# SHA256.net
KiCad netlist of a schematic drawn in Altium Designer
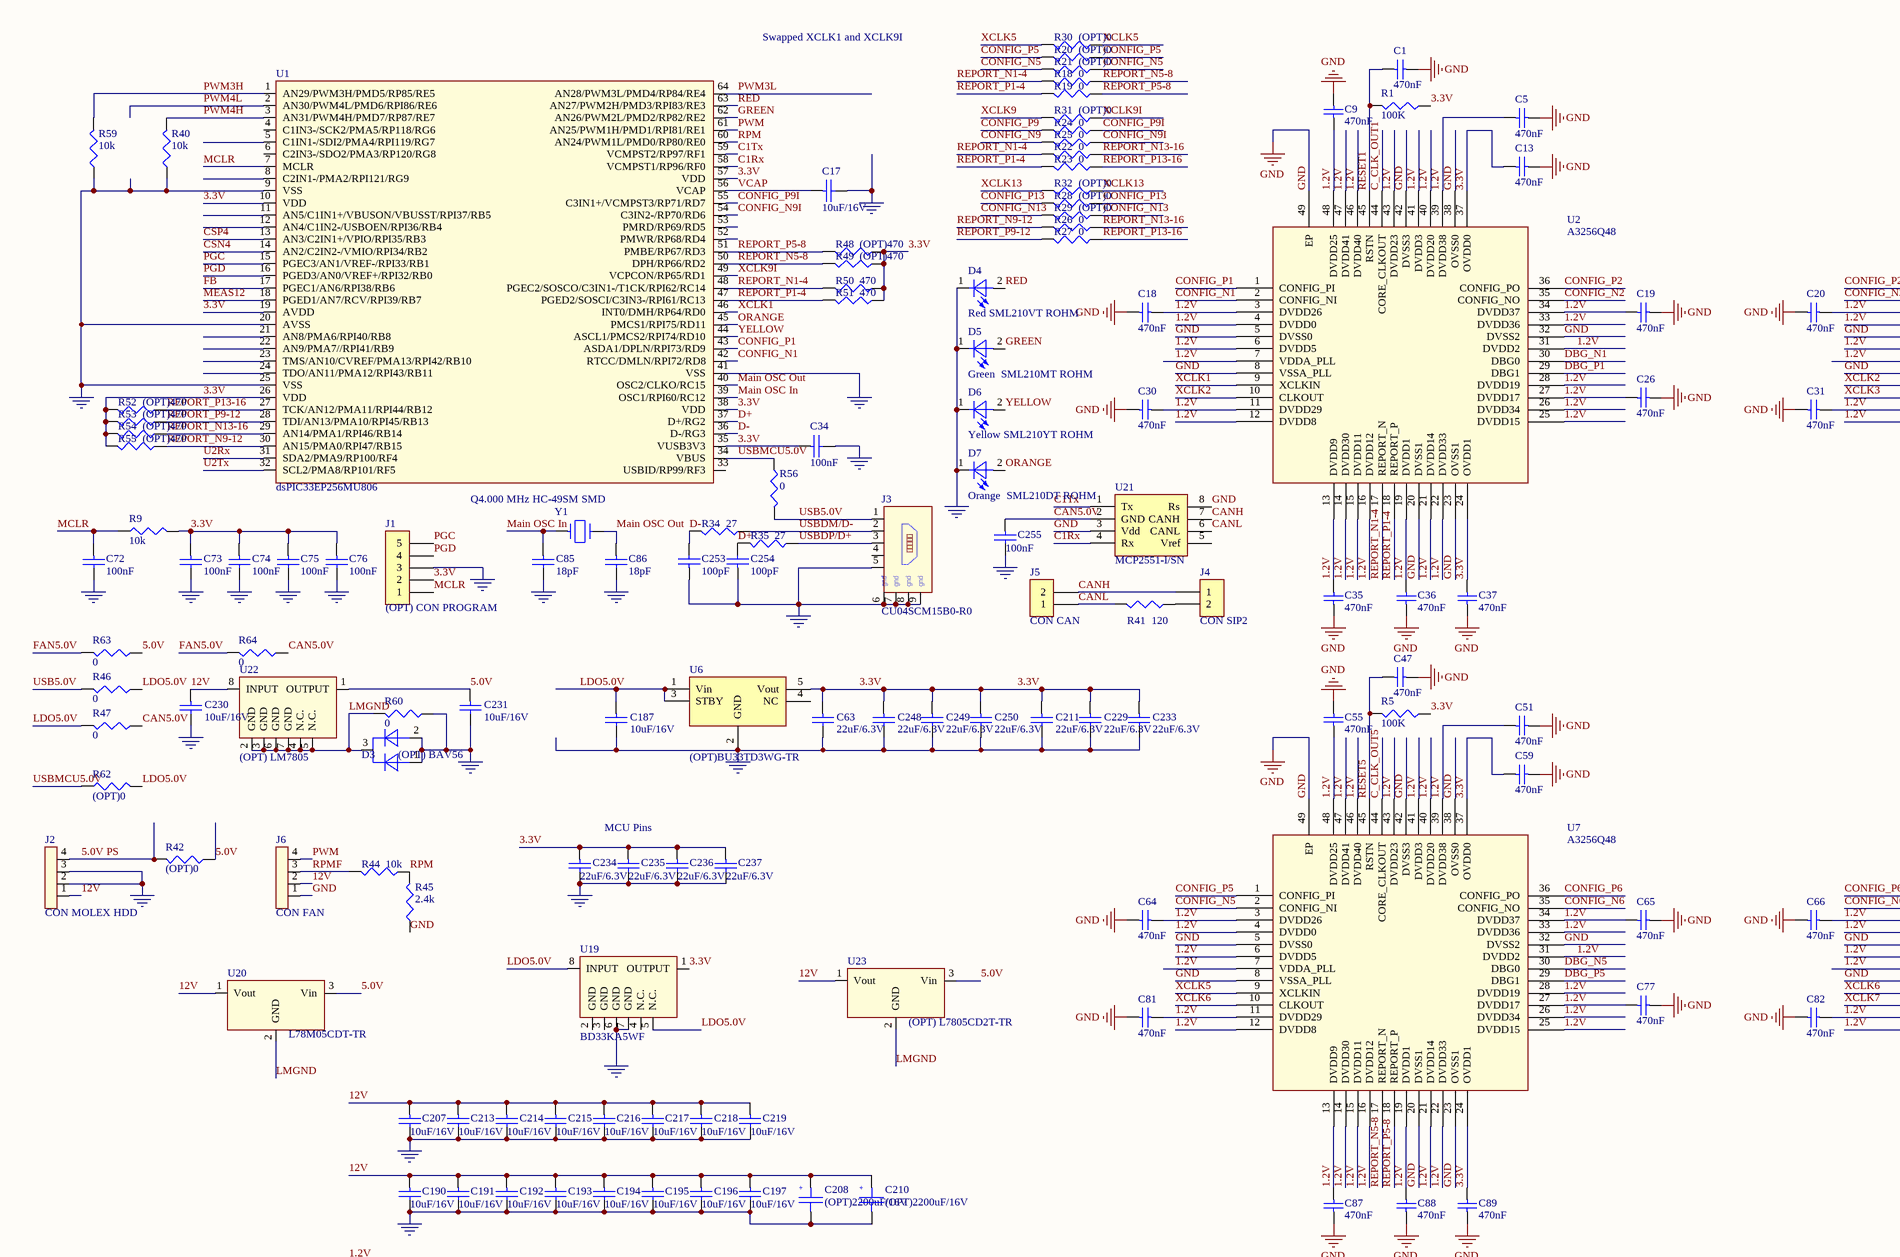
[diagram p0: SHA256.SchDoc, top left]
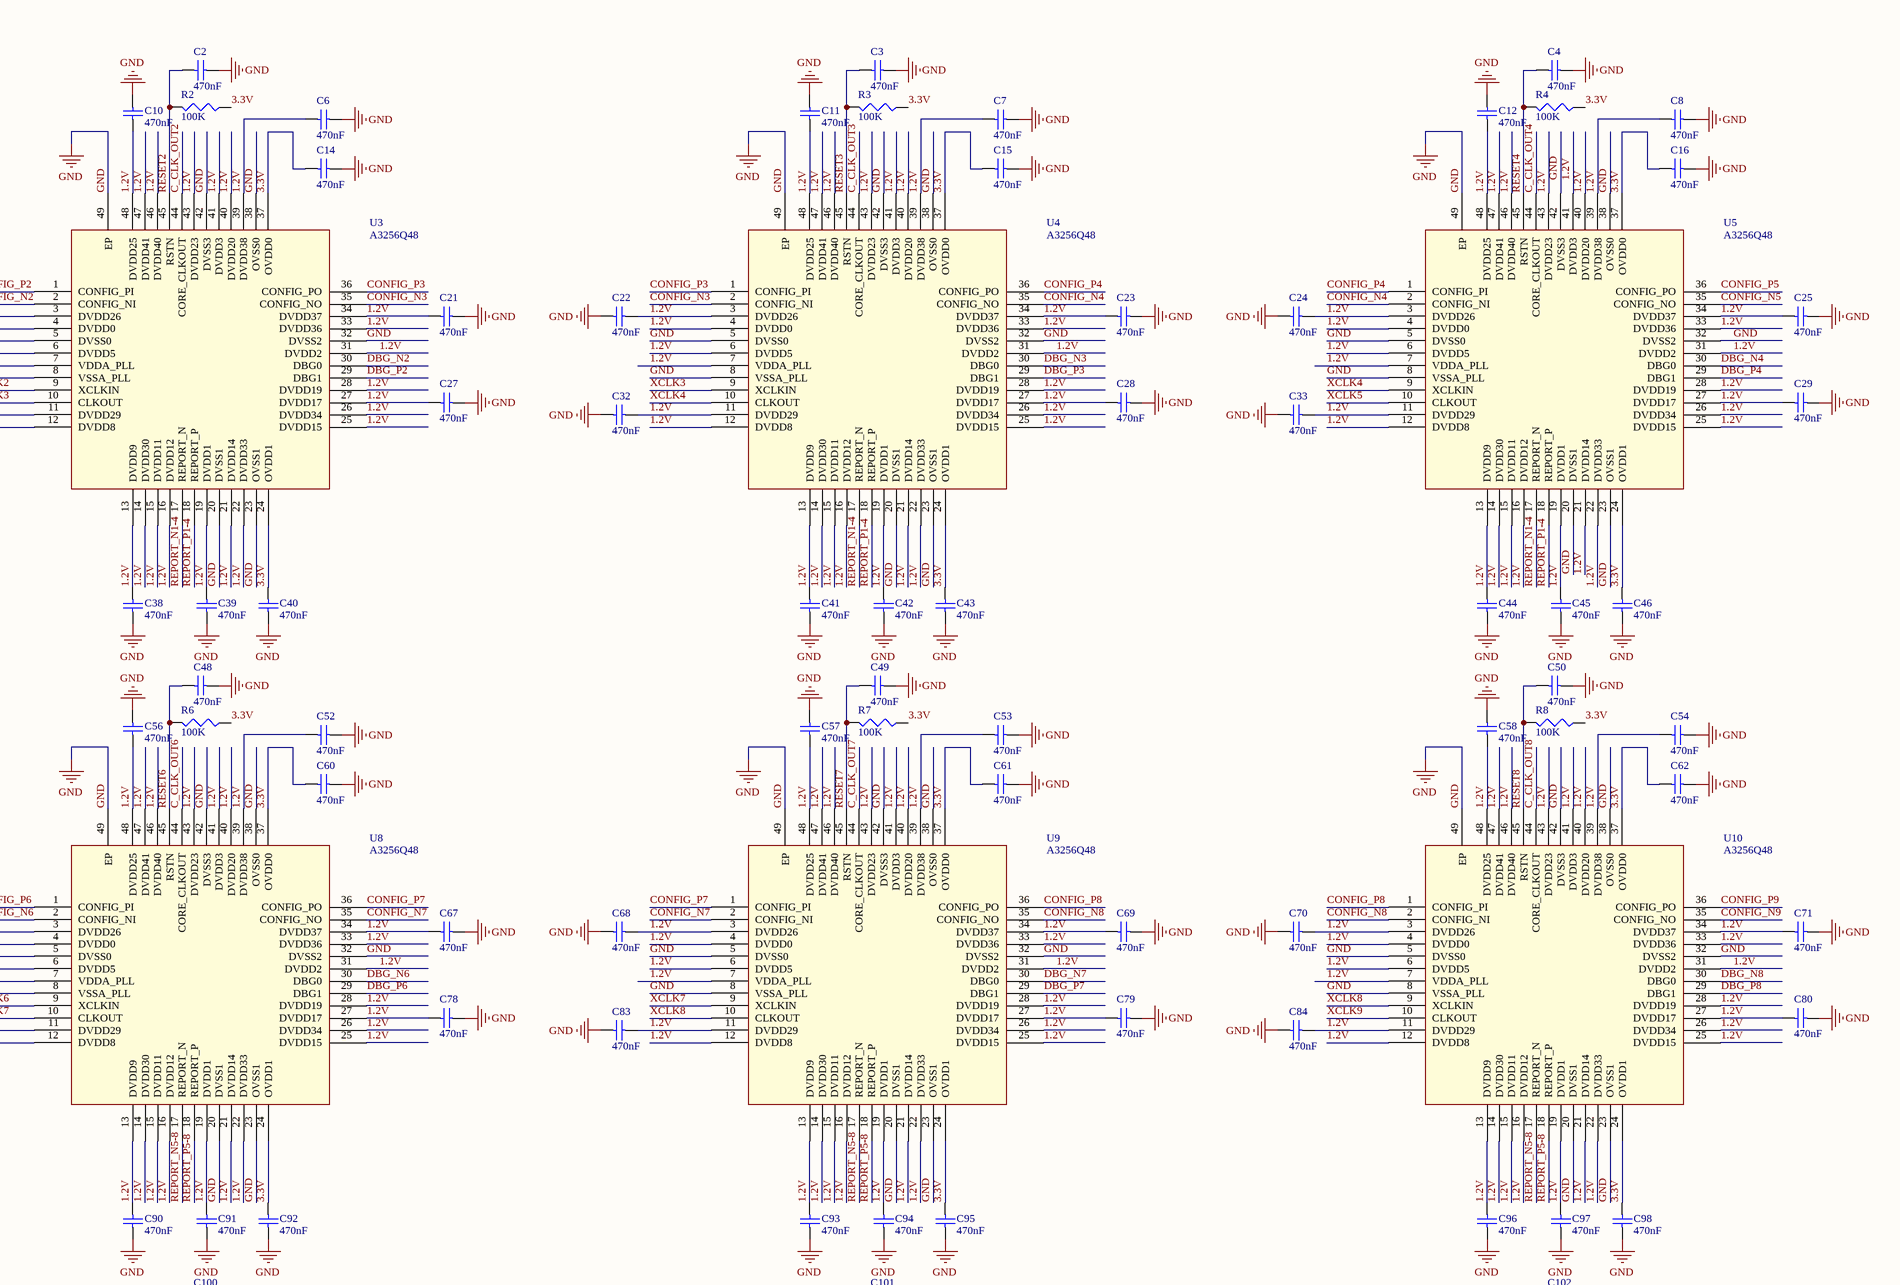
[diagram p1: SHA256.SchDoc, top right]
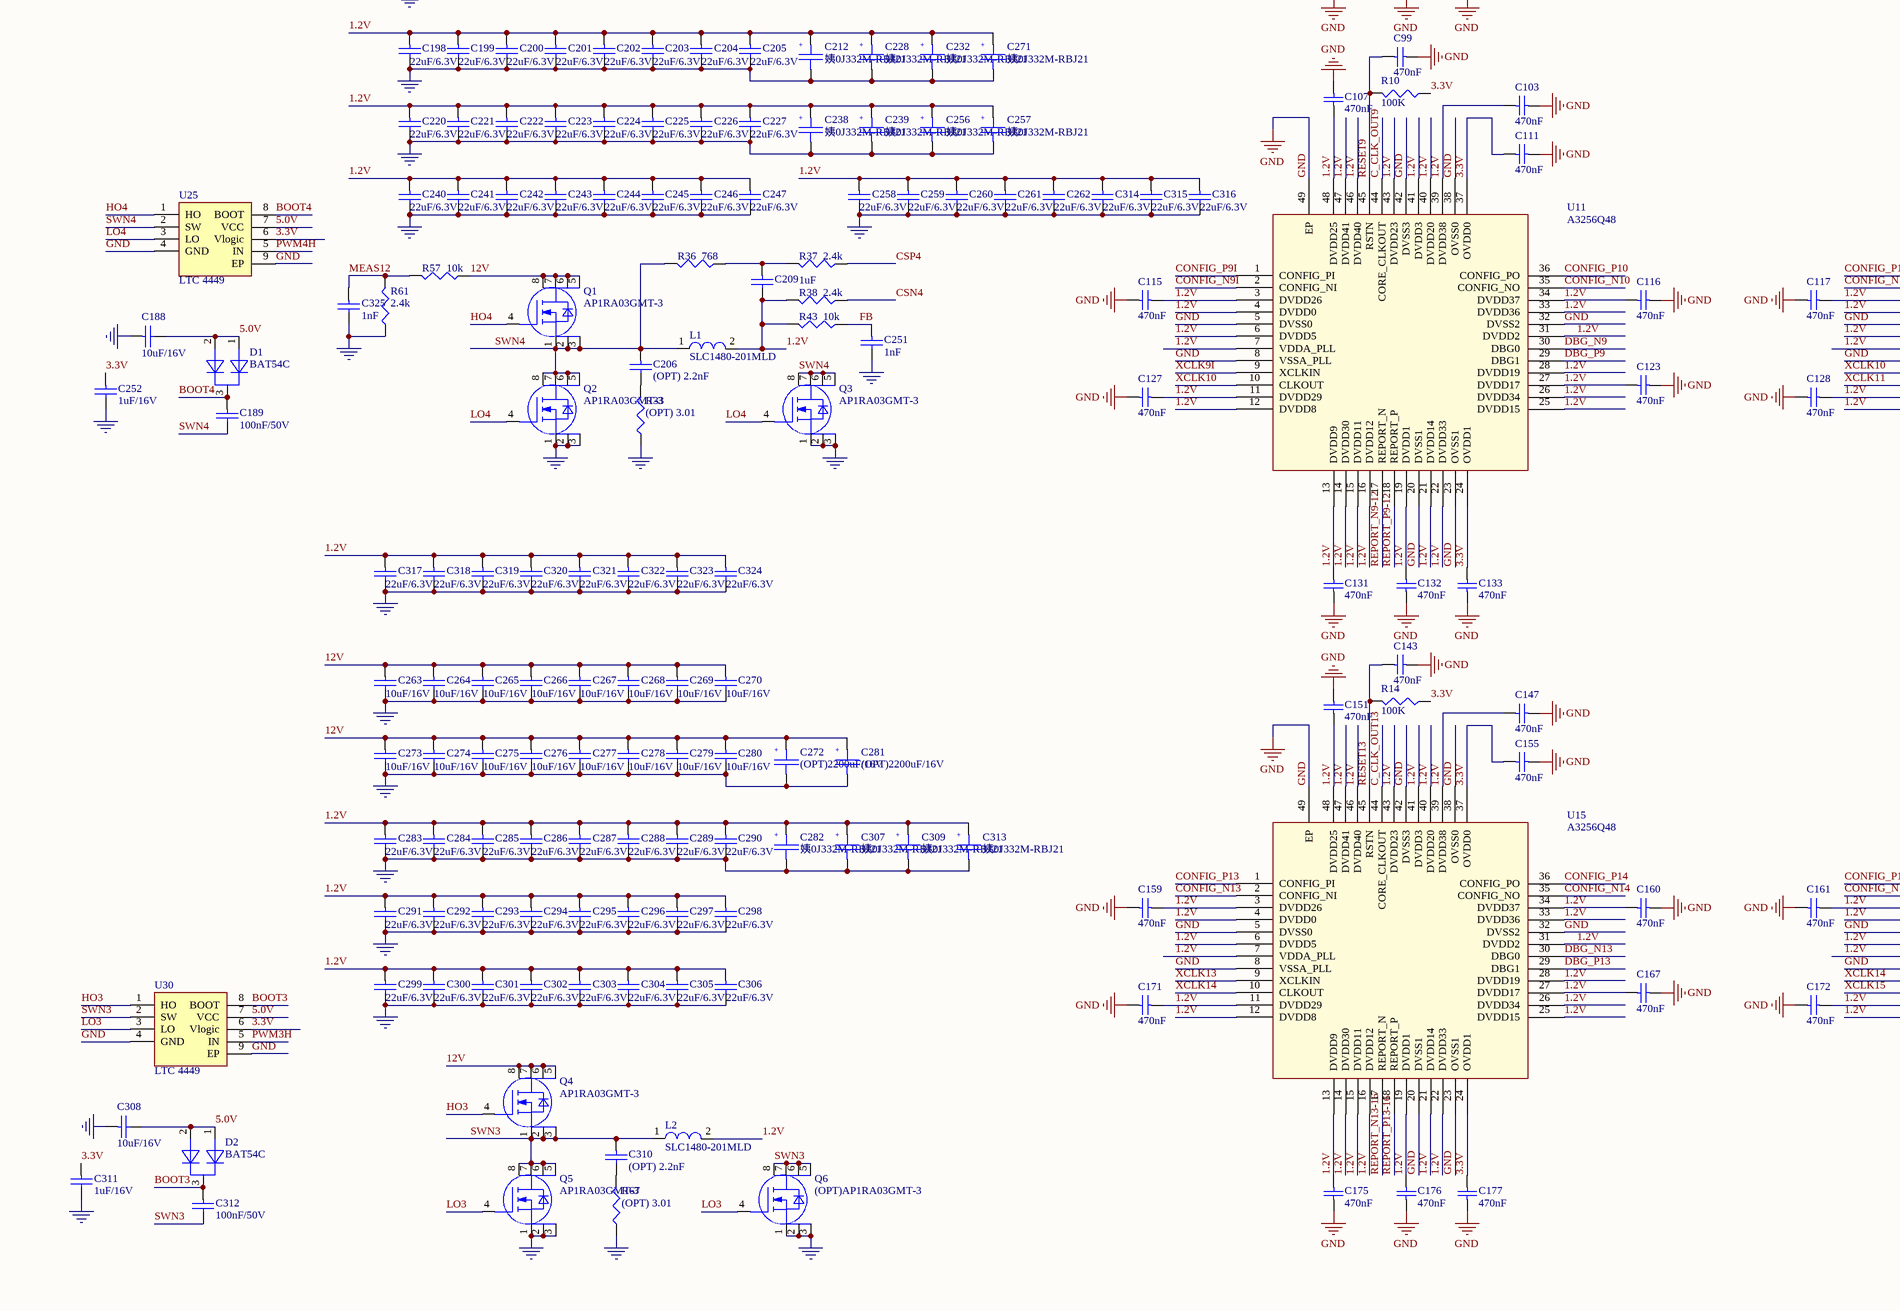
[diagram p2: SHA256.SchDoc, bottom left]
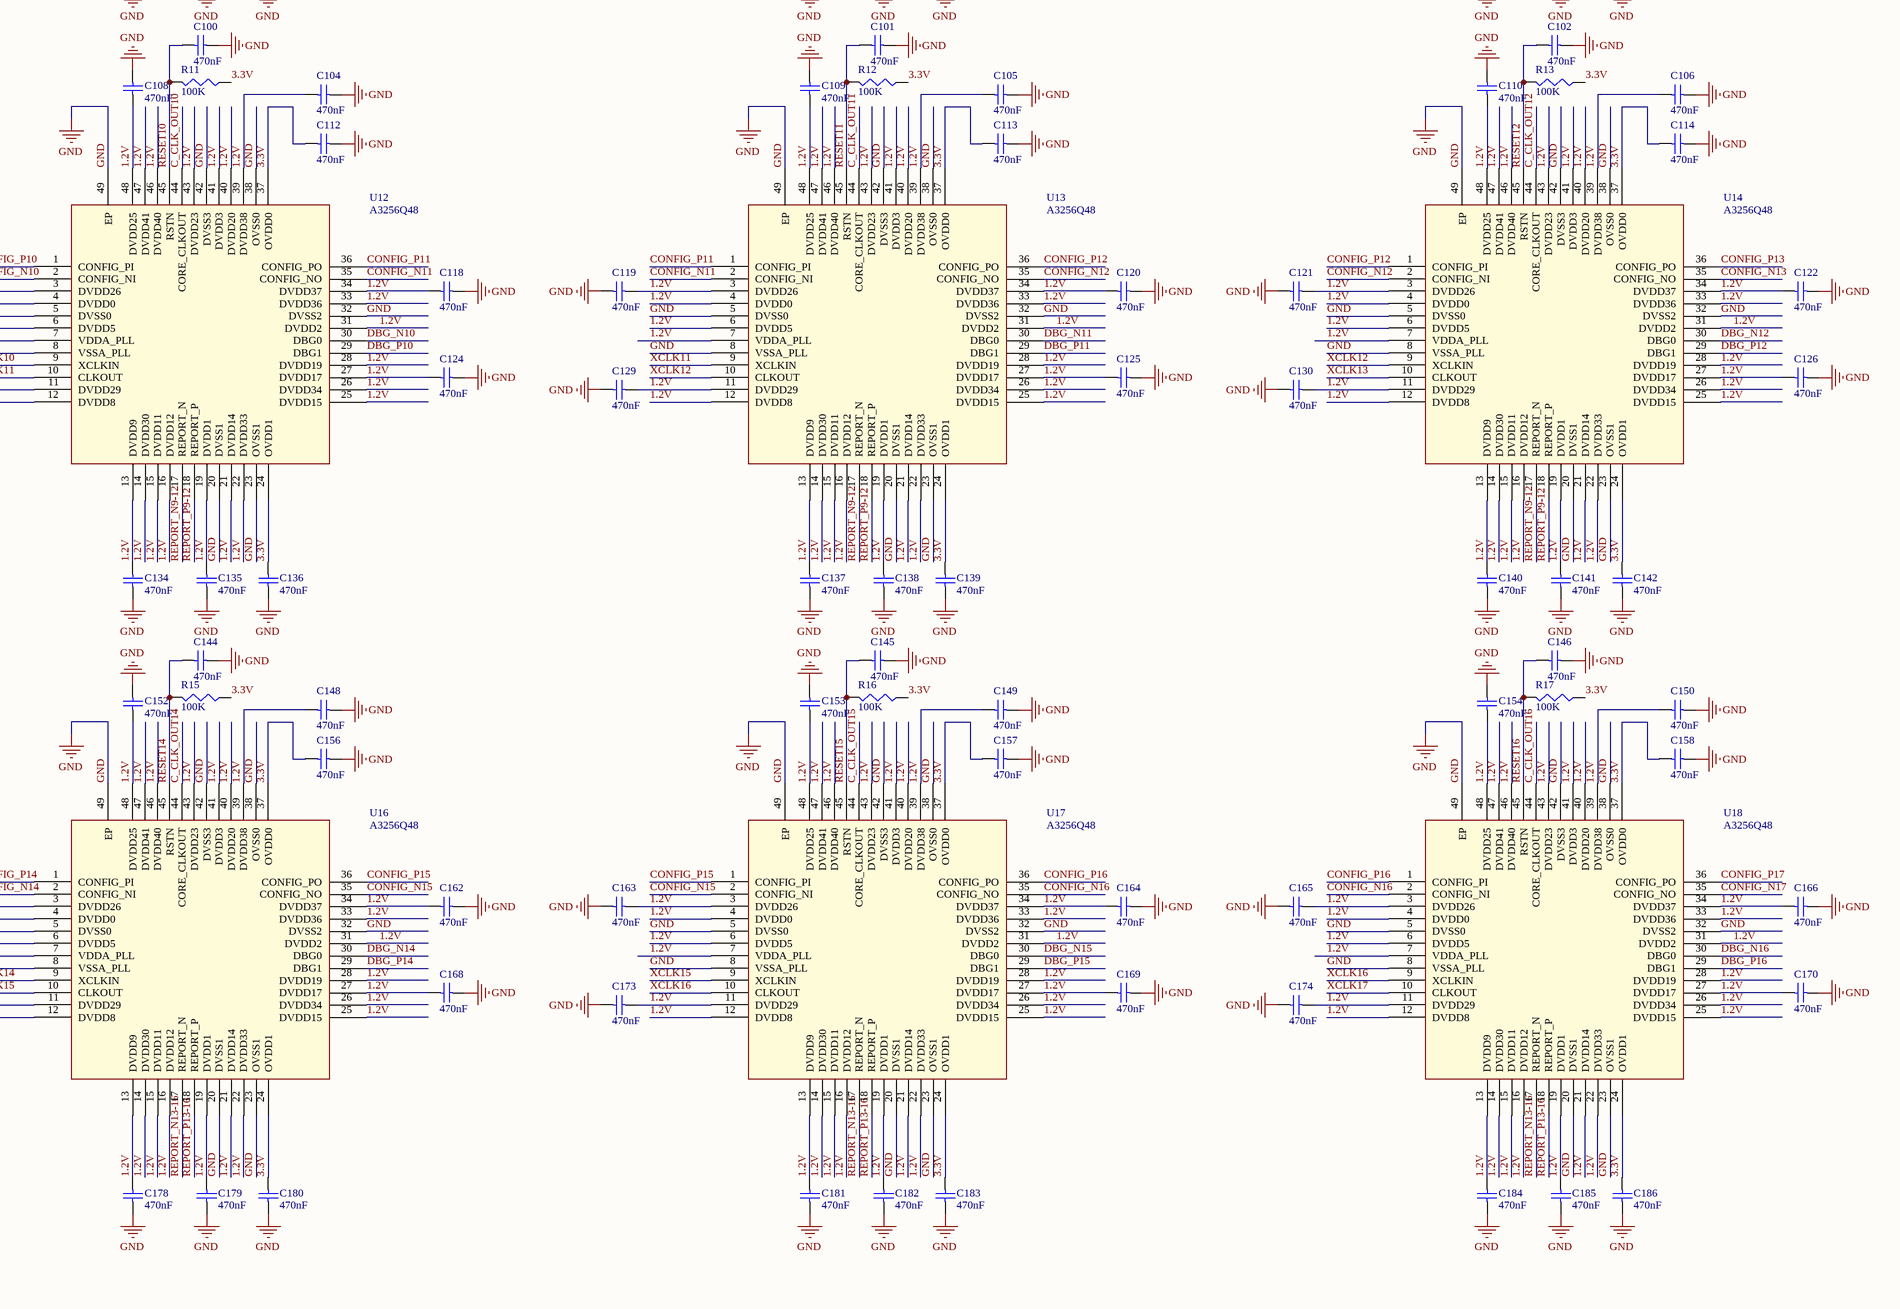
[diagram p3: SHA256.SchDoc, bottom right]

(export (version "E")
  (design (tool "Eeschema 10.0.6"))
  (components
    (comp (ref "C1")
      (value "470nF")
      (footprint "SMD_0603_CAPC1608X80N")
      (description "Capacitor (Semiconductor SIM Model)")
      (fields (field (name "PUBLISHER") "Altium Limited"))
      (libsource (lib "Miscellaneous Devices") (part "Cap Semi"))
    )
    (comp (ref "C2")
      (value "470nF")
      (footprint "SMD_0603_CAPC1608X80N")
      (description "Capacitor (Semiconductor SIM Model)")
      (fields (field (name "PUBLISHER") "Altium Limited"))
      (libsource (lib "Miscellaneous Devices") (part "Cap Semi"))
    )
    (comp (ref "C3")
      (value "470nF")
      (footprint "SMD_0603_CAPC1608X80N")
      (description "Capacitor (Semiconductor SIM Model)")
      (fields (field (name "PUBLISHER") "Altium Limited"))
      (libsource (lib "Miscellaneous Devices") (part "Cap Semi"))
    )
    (comp (ref "C4")
      (value "470nF")
      (footprint "SMD_0603_CAPC1608X80N")
      (description "Capacitor (Semiconductor SIM Model)")
      (fields (field (name "PUBLISHER") "Altium Limited"))
      (libsource (lib "Miscellaneous Devices") (part "Cap Semi"))
    )
    (comp (ref "C5")
      (value "470nF")
      (footprint "SMD_0603_CAPC1608X80N")
      (description "Capacitor (Semiconductor SIM Model)")
      (fields (field (name "PUBLISHER") "Altium Limited"))
      (libsource (lib "Miscellaneous Devices") (part "Cap Semi"))
    )
    (comp (ref "C6")
      (value "470nF")
      (footprint "SMD_0603_CAPC1608X80N")
      (description "Capacitor (Semiconductor SIM Model)")
      (fields (field (name "PUBLISHER") "Altium Limited"))
      (libsource (lib "Miscellaneous Devices") (part "Cap Semi"))
    )
    (comp (ref "C7")
      (value "470nF")
      (footprint "SMD_0603_CAPC1608X80N")
      (description "Capacitor (Semiconductor SIM Model)")
      (fields (field (name "PUBLISHER") "Altium Limited"))
      (libsource (lib "Miscellaneous Devices") (part "Cap Semi"))
    )
    (comp (ref "C8")
      (value "470nF")
      (footprint "SMD_0603_CAPC1608X80N")
      (description "Capacitor (Semiconductor SIM Model)")
      (fields (field (name "PUBLISHER") "Altium Limited"))
      (libsource (lib "Miscellaneous Devices") (part "Cap Semi"))
    )
    (comp (ref "C9")
      (value "470nF")
      (footprint "SMD_0603_CAPC1608X80N")
      (description "Capacitor (Semiconductor SIM Model)")
      (fields (field (name "PUBLISHER") "Altium Limited"))
      (libsource (lib "Miscellaneous Devices") (part "Cap Semi"))
    )
    (comp (ref "C10")
      (value "470nF")
      (footprint "SMD_0603_CAPC1608X80N")
      (description "Capacitor (Semiconductor SIM Model)")
      (fields (field (name "PUBLISHER") "Altium Limited"))
      (libsource (lib "Miscellaneous Devices") (part "Cap Semi"))
    )
    (comp (ref "C11")
      (value "470nF")
      (footprint "SMD_0603_CAPC1608X80N")
      (description "Capacitor (Semiconductor SIM Model)")
      (fields (field (name "PUBLISHER") "Altium Limited"))
      (libsource (lib "Miscellaneous Devices") (part "Cap Semi"))
    )
    (comp (ref "C12")
      (value "470nF")
      (footprint "SMD_0603_CAPC1608X80N")
      (description "Capacitor (Semiconductor SIM Model)")
      (fields (field (name "PUBLISHER") "Altium Limited"))
      (libsource (lib "Miscellaneous Devices") (part "Cap Semi"))
    )
    (comp (ref "C13")
      (value "470nF")
      (footprint "SMD_0603_CAPC1608X80N")
      (description "Capacitor (Semiconductor SIM Model)")
      (fields (field (name "PUBLISHER") "Altium Limited"))
      (libsource (lib "Miscellaneous Devices") (part "Cap Semi"))
    )
    (comp (ref "C14")
      (value "470nF")
      (footprint "SMD_0603_CAPC1608X80N")
      (description "Capacitor (Semiconductor SIM Model)")
      (fields (field (name "PUBLISHER") "Altium Limited"))
      (libsource (lib "Miscellaneous Devices") (part "Cap Semi"))
    )
    (comp (ref "C15")
      (value "470nF")
      (footprint "SMD_0603_CAPC1608X80N")
      (description "Capacitor (Semiconductor SIM Model)")
      (fields (field (name "PUBLISHER") "Altium Limited"))
      (libsource (lib "Miscellaneous Devices") (part "Cap Semi"))
    )
    (comp (ref "C16")
      (value "470nF")
      (footprint "SMD_0603_CAPC1608X80N")
      (description "Capacitor (Semiconductor SIM Model)")
      (fields (field (name "PUBLISHER") "Altium Limited"))
      (libsource (lib "Miscellaneous Devices") (part "Cap Semi"))
    )
    (comp (ref "C17")
      (value "10uF/16V")
      (footprint "SMD_0805_CAPC2012X145N")
      (description "Capacitor")
      (libsource (lib "*") (part "CAP"))
    )
    (comp (ref "C18")
      (value "470nF")
      (footprint "SMD_0603_CAPC1608X80N")
      (description "Capacitor (Semiconductor SIM Model)")
      (fields (field (name "PUBLISHER") "Altium Limited"))
      (libsource (lib "Miscellaneous Devices") (part "Cap Semi"))
    )
    (comp (ref "C19")
      (value "470nF")
      (footprint "SMD_0603_CAPC1608X80N")
      (description "Capacitor (Semiconductor SIM Model)")
      (fields (field (name "PUBLISHER") "Altium Limited"))
      (libsource (lib "Miscellaneous Devices") (part "Cap Semi"))
    )
    (comp (ref "C20")
      (value "470nF")
      (footprint "SMD_0603_CAPC1608X80N")
      (description "Capacitor (Semiconductor SIM Model)")
      (fields (field (name "PUBLISHER") "Altium Limited"))
      (libsource (lib "Miscellaneous Devices") (part "Cap Semi"))
    )
    (comp (ref "C21")
      (value "470nF")
      (footprint "SMD_0603_CAPC1608X80N")
      (description "Capacitor (Semiconductor SIM Model)")
      (fields (field (name "PUBLISHER") "Altium Limited"))
      (libsource (lib "Miscellaneous Devices") (part "Cap Semi"))
    )
    (comp (ref "C22")
      (value "470nF")
      (footprint "SMD_0603_CAPC1608X80N")
      (description "Capacitor (Semiconductor SIM Model)")
      (fields (field (name "PUBLISHER") "Altium Limited"))
      (libsource (lib "Miscellaneous Devices") (part "Cap Semi"))
    )
    (comp (ref "C23")
      (value "470nF")
      (footprint "SMD_0603_CAPC1608X80N")
      (description "Capacitor (Semiconductor SIM Model)")
      (fields (field (name "PUBLISHER") "Altium Limited"))
      (libsource (lib "Miscellaneous Devices") (part "Cap Semi"))
    )
    (comp (ref "C24")
      (value "470nF")
      (footprint "SMD_0603_CAPC1608X80N")
      (description "Capacitor (Semiconductor SIM Model)")
      (fields (field (name "PUBLISHER") "Altium Limited"))
      (libsource (lib "Miscellaneous Devices") (part "Cap Semi"))
    )
    (comp (ref "C25")
      (value "470nF")
      (footprint "SMD_0603_CAPC1608X80N")
      (description "Capacitor (Semiconductor SIM Model)")
      (fields (field (name "PUBLISHER") "Altium Limited"))
      (libsource (lib "Miscellaneous Devices") (part "Cap Semi"))
    )
    (comp (ref "C26")
      (value "470nF")
      (footprint "SMD_0603_CAPC1608X80N")
      (description "Capacitor (Semiconductor SIM Model)")
      (fields (field (name "PUBLISHER") "Altium Limited"))
      (libsource (lib "Miscellaneous Devices") (part "Cap Semi"))
    )
    (comp (ref "C27")
      (value "470nF")
      (footprint "SMD_0603_CAPC1608X80N")
      (description "Capacitor (Semiconductor SIM Model)")
      (fields (field (name "PUBLISHER") "Altium Limited"))
      (libsource (lib "Miscellaneous Devices") (part "Cap Semi"))
    )
    (comp (ref "C28")
      (value "470nF")
      (footprint "SMD_0603_CAPC1608X80N")
      (description "Capacitor (Semiconductor SIM Model)")
      (fields (field (name "PUBLISHER") "Altium Limited"))
      (libsource (lib "Miscellaneous Devices") (part "Cap Semi"))
    )
    (comp (ref "C29")
      (value "470nF")
      (footprint "SMD_0603_CAPC1608X80N")
      (description "Capacitor (Semiconductor SIM Model)")
      (fields (field (name "PUBLISHER") "Altium Limited"))
      (libsource (lib "Miscellaneous Devices") (part "Cap Semi"))
    )
    (comp (ref "C30")
      (value "470nF")
      (footprint "SMD_0603_CAPC1608X80N")
      (description "Capacitor (Semiconductor SIM Model)")
      (fields (field (name "PUBLISHER") "Altium Limited"))
      (libsource (lib "Miscellaneous Devices") (part "Cap Semi"))
    )
    (comp (ref "C31")
      (value "470nF")
      (footprint "SMD_0603_CAPC1608X80N")
      (description "Capacitor (Semiconductor SIM Model)")
      (fields (field (name "PUBLISHER") "Altium Limited"))
      (libsource (lib "Miscellaneous Devices") (part "Cap Semi"))
    )
    (comp (ref "C32")
      (value "470nF")
      (footprint "SMD_0603_CAPC1608X80N")
      (description "Capacitor (Semiconductor SIM Model)")
      (fields (field (name "PUBLISHER") "Altium Limited"))
      (libsource (lib "Miscellaneous Devices") (part "Cap Semi"))
    )
    (comp (ref "C33")
      (value "470nF")
      (footprint "SMD_0603_CAPC1608X80N")
      (description "Capacitor (Semiconductor SIM Model)")
      (fields (field (name "PUBLISHER") "Altium Limited"))
      (libsource (lib "Miscellaneous Devices") (part "Cap Semi"))
    )
    (comp (ref "C34")
      (value "100nF")
      (footprint "SMD_0603_CAPC1608X80N")
      (description "Capacitor")
      (libsource (lib "*") (part "CAP"))
    )
    (comp (ref "C35")
      (value "470nF")
      (footprint "SMD_0603_CAPC1608X80N")
      (description "Capacitor (Semiconductor SIM Model)")
      (fields (field (name "PUBLISHER") "Altium Limited"))
      (libsource (lib "Miscellaneous Devices") (part "Cap Semi"))
    )
    (comp (ref "C36")
      (value "470nF")
      (footprint "SMD_0603_CAPC1608X80N")
      (description "Capacitor (Semiconductor SIM Model)")
      (fields (field (name "PUBLISHER") "Altium Limited"))
      (libsource (lib "Miscellaneous Devices") (part "Cap Semi"))
    )
    (comp (ref "C37")
      (value "470nF")
      (footprint "SMD_0603_CAPC1608X80N")
      (description "Capacitor (Semiconductor SIM Model)")
      (fields (field (name "PUBLISHER") "Altium Limited"))
      (libsource (lib "Miscellaneous Devices") (part "Cap Semi"))
    )
    (comp (ref "C38")
      (value "470nF")
      (footprint "SMD_0603_CAPC1608X80N")
      (description "Capacitor (Semiconductor SIM Model)")
      (fields (field (name "PUBLISHER") "Altium Limited"))
      (libsource (lib "Miscellaneous Devices") (part "Cap Semi"))
    )
    (comp (ref "C39")
      (value "470nF")
      (footprint "SMD_0603_CAPC1608X80N")
      (description "Capacitor (Semiconductor SIM Model)")
      (fields (field (name "PUBLISHER") "Altium Limited"))
      (libsource (lib "Miscellaneous Devices") (part "Cap Semi"))
    )
    (comp (ref "C40")
      (value "470nF")
      (footprint "SMD_0603_CAPC1608X80N")
      (description "Capacitor (Semiconductor SIM Model)")
      (fields (field (name "PUBLISHER") "Altium Limited"))
      (libsource (lib "Miscellaneous Devices") (part "Cap Semi"))
    )
    (comp (ref "C41")
      (value "470nF")
      (footprint "SMD_0603_CAPC1608X80N")
      (description "Capacitor (Semiconductor SIM Model)")
      (fields (field (name "PUBLISHER") "Altium Limited"))
      (libsource (lib "Miscellaneous Devices") (part "Cap Semi"))
    )
    (comp (ref "C42")
      (value "470nF")
      (footprint "SMD_0603_CAPC1608X80N")
      (description "Capacitor (Semiconductor SIM Model)")
      (fields (field (name "PUBLISHER") "Altium Limited"))
      (libsource (lib "Miscellaneous Devices") (part "Cap Semi"))
    )
    (comp (ref "C43")
      (value "470nF")
      (footprint "SMD_0603_CAPC1608X80N")
      (description "Capacitor (Semiconductor SIM Model)")
      (fields (field (name "PUBLISHER") "Altium Limited"))
      (libsource (lib "Miscellaneous Devices") (part "Cap Semi"))
    )
    (comp (ref "C44")
      (value "470nF")
      (footprint "SMD_0603_CAPC1608X80N")
      (description "Capacitor (Semiconductor SIM Model)")
      (fields (field (name "PUBLISHER") "Altium Limited"))
      (libsource (lib "Miscellaneous Devices") (part "Cap Semi"))
    )
    (comp (ref "C45")
      (value "470nF")
      (footprint "SMD_0603_CAPC1608X80N")
      (description "Capacitor (Semiconductor SIM Model)")
      (fields (field (name "PUBLISHER") "Altium Limited"))
      (libsource (lib "Miscellaneous Devices") (part "Cap Semi"))
    )
    (comp (ref "C46")
      (value "470nF")
      (footprint "SMD_0603_CAPC1608X80N")
      (description "Capacitor (Semiconductor SIM Model)")
      (fields (field (name "PUBLISHER") "Altium Limited"))
      (libsource (lib "Miscellaneous Devices") (part "Cap Semi"))
    )
    (comp (ref "C47")
      (value "470nF")
      (footprint "SMD_0603_CAPC1608X80N")
      (description "Capacitor (Semiconductor SIM Model)")
      (fields (field (name "PUBLISHER") "Altium Limited"))
      (libsource (lib "Miscellaneous Devices") (part "Cap Semi"))
    )
    (comp (ref "C48")
      (value "470nF")
      (footprint "SMD_0603_CAPC1608X80N")
      (description "Capacitor (Semiconductor SIM Model)")
      (fields (field (name "PUBLISHER") "Altium Limited"))
      (libsource (lib "Miscellaneous Devices") (part "Cap Semi"))
    )
    (comp (ref "C49")
      (value "470nF")
      (footprint "SMD_0603_CAPC1608X80N")
      (description "Capacitor (Semiconductor SIM Model)")
      (fields (field (name "PUBLISHER") "Altium Limited"))
      (libsource (lib "Miscellaneous Devices") (part "Cap Semi"))
    )
    (comp (ref "C50")
      (value "470nF")
      (footprint "SMD_0603_CAPC1608X80N")
      (description "Capacitor (Semiconductor SIM Model)")
      (fields (field (name "PUBLISHER") "Altium Limited"))
      (libsource (lib "Miscellaneous Devices") (part "Cap Semi"))
    )
    (comp (ref "C51")
      (value "470nF")
      (footprint "SMD_0603_CAPC1608X80N")
      (description "Capacitor (Semiconductor SIM Model)")
      (fields (field (name "PUBLISHER") "Altium Limited"))
      (libsource (lib "Miscellaneous Devices") (part "Cap Semi"))
    )
    (comp (ref "C52")
      (value "470nF")
      (footprint "SMD_0603_CAPC1608X80N")
      (description "Capacitor (Semiconductor SIM Model)")
      (fields (field (name "PUBLISHER") "Altium Limited"))
      (libsource (lib "Miscellaneous Devices") (part "Cap Semi"))
    )
    (comp (ref "C53")
      (value "470nF")
      (footprint "SMD_0603_CAPC1608X80N")
      (description "Capacitor (Semiconductor SIM Model)")
      (fields (field (name "PUBLISHER") "Altium Limited"))
      (libsource (lib "Miscellaneous Devices") (part "Cap Semi"))
    )
    (comp (ref "C54")
      (value "470nF")
      (footprint "SMD_0603_CAPC1608X80N")
      (description "Capacitor (Semiconductor SIM Model)")
      (fields (field (name "PUBLISHER") "Altium Limited"))
      (libsource (lib "Miscellaneous Devices") (part "Cap Semi"))
    )
    (comp (ref "C55")
      (value "470nF")
      (footprint "SMD_0603_CAPC1608X80N")
      (description "Capacitor (Semiconductor SIM Model)")
      (fields (field (name "PUBLISHER") "Altium Limited"))
      (libsource (lib "Miscellaneous Devices") (part "Cap Semi"))
    )
    (comp (ref "C56")
      (value "470nF")
      (footprint "SMD_0603_CAPC1608X80N")
      (description "Capacitor (Semiconductor SIM Model)")
      (fields (field (name "PUBLISHER") "Altium Limited"))
      (libsource (lib "Miscellaneous Devices") (part "Cap Semi"))
    )
    (comp (ref "C57")
      (value "470nF")
      (footprint "SMD_0603_CAPC1608X80N")
      (description "Capacitor (Semiconductor SIM Model)")
      (fields (field (name "PUBLISHER") "Altium Limited"))
      (libsource (lib "Miscellaneous Devices") (part "Cap Semi"))
    )
    (comp (ref "C58")
      (value "470nF")
      (footprint "SMD_0603_CAPC1608X80N")
      (description "Capacitor (Semiconductor SIM Model)")
      (fields (field (name "PUBLISHER") "Altium Limited"))
      (libsource (lib "Miscellaneous Devices") (part "Cap Semi"))
    )
    (comp (ref "C59")
      (value "470nF")
      (footprint "SMD_0603_CAPC1608X80N")
      (description "Capacitor (Semiconductor SIM Model)")
      (fields (field (name "PUBLISHER") "Altium Limited"))
      (libsource (lib "Miscellaneous Devices") (part "Cap Semi"))
    )
    (comp (ref "C60")
      (value "470nF")
      (footprint "SMD_0603_CAPC1608X80N")
      (description "Capacitor (Semiconductor SIM Model)")
      (fields (field (name "PUBLISHER") "Altium Limited"))
      (libsource (lib "Miscellaneous Devices") (part "Cap Semi"))
    )
    (comp (ref "C61")
      (value "470nF")
      (footprint "SMD_0603_CAPC1608X80N")
      (description "Capacitor (Semiconductor SIM Model)")
      (fields (field (name "PUBLISHER") "Altium Limited"))
      (libsource (lib "Miscellaneous Devices") (part "Cap Semi"))
    )
    (comp (ref "C62")
      (value "470nF")
      (footprint "SMD_0603_CAPC1608X80N")
      (description "Capacitor (Semiconductor SIM Model)")
      (fields (field (name "PUBLISHER") "Altium Limited"))
      (libsource (lib "Miscellaneous Devices") (part "Cap Semi"))
    )
    (comp (ref "C63")
      (value "22uF/6.3V")
      (footprint "SMD_0805_CAPC2012X145N")
      (description "Capacitor")
      (libsource (lib "*") (part "CAP"))
    )
    (comp (ref "C64")
      (value "470nF")
      (footprint "SMD_0603_CAPC1608X80N")
      (description "Capacitor (Semiconductor SIM Model)")
      (fields (field (name "PUBLISHER") "Altium Limited"))
      (libsource (lib "Miscellaneous Devices") (part "Cap Semi"))
    )
    (comp (ref "C65")
      (value "470nF")
      (footprint "SMD_0603_CAPC1608X80N")
      (description "Capacitor (Semiconductor SIM Model)")
      (fields (field (name "PUBLISHER") "Altium Limited"))
      (libsource (lib "Miscellaneous Devices") (part "Cap Semi"))
    )
    (comp (ref "C66")
      (value "470nF")
      (footprint "SMD_0603_CAPC1608X80N")
      (description "Capacitor (Semiconductor SIM Model)")
      (fields (field (name "PUBLISHER") "Altium Limited"))
      (libsource (lib "Miscellaneous Devices") (part "Cap Semi"))
    )
    (comp (ref "C67")
      (value "470nF")
      (footprint "SMD_0603_CAPC1608X80N")
      (description "Capacitor (Semiconductor SIM Model)")
      (fields (field (name "PUBLISHER") "Altium Limited"))
      (libsource (lib "Miscellaneous Devices") (part "Cap Semi"))
    )
    (comp (ref "C68")
      (value "470nF")
      (footprint "SMD_0603_CAPC1608X80N")
      (description "Capacitor (Semiconductor SIM Model)")
      (fields (field (name "PUBLISHER") "Altium Limited"))
      (libsource (lib "Miscellaneous Devices") (part "Cap Semi"))
    )
    (comp (ref "C69")
      (value "470nF")
      (footprint "SMD_0603_CAPC1608X80N")
      (description "Capacitor (Semiconductor SIM Model)")
      (fields (field (name "PUBLISHER") "Altium Limited"))
      (libsource (lib "Miscellaneous Devices") (part "Cap Semi"))
    )
    (comp (ref "C70")
      (value "470nF")
      (footprint "SMD_0603_CAPC1608X80N")
      (description "Capacitor (Semiconductor SIM Model)")
      (fields (field (name "PUBLISHER") "Altium Limited"))
      (libsource (lib "Miscellaneous Devices") (part "Cap Semi"))
    )
    (comp (ref "C71")
      (value "470nF")
      (footprint "SMD_0603_CAPC1608X80N")
      (description "Capacitor (Semiconductor SIM Model)")
      (fields (field (name "PUBLISHER") "Altium Limited"))
      (libsource (lib "Miscellaneous Devices") (part "Cap Semi"))
    )
    (comp (ref "C72")
      (value "100nF")
      (footprint "SMD_0603_CAPC1608X80N")
      (description "Capacitor")
      (libsource (lib "*") (part "CAP"))
    )
    (comp (ref "C73")
      (value "100nF")
      (footprint "SMD_0603_CAPC1608X80N")
      (description "Capacitor")
      (libsource (lib "*") (part "CAP"))
    )
    (comp (ref "C74")
      (value "100nF")
      (footprint "SMD_0603_CAPC1608X80N")
      (description "Capacitor")
      (libsource (lib "*") (part "CAP"))
    )
    (comp (ref "C75")
      (value "100nF")
      (footprint "SMD_0603_CAPC1608X80N")
      (description "Capacitor")
      (libsource (lib "*") (part "CAP"))
    )
    (comp (ref "C76")
      (value "100nF")
      (footprint "SMD_0603_CAPC1608X80N")
      (description "Capacitor")
      (libsource (lib "*") (part "CAP"))
    )
    (comp (ref "C77")
      (value "470nF")
      (footprint "SMD_0603_CAPC1608X80N")
      (description "Capacitor (Semiconductor SIM Model)")
      (fields (field (name "PUBLISHER") "Altium Limited"))
      (libsource (lib "Miscellaneous Devices") (part "Cap Semi"))
    )
    (comp (ref "C78")
      (value "470nF")
      (footprint "SMD_0603_CAPC1608X80N")
      (description "Capacitor (Semiconductor SIM Model)")
      (fields (field (name "PUBLISHER") "Altium Limited"))
      (libsource (lib "Miscellaneous Devices") (part "Cap Semi"))
    )
    (comp (ref "C79")
      (value "470nF")
      (footprint "SMD_0603_CAPC1608X80N")
      (description "Capacitor (Semiconductor SIM Model)")
      (fields (field (name "PUBLISHER") "Altium Limited"))
      (libsource (lib "Miscellaneous Devices") (part "Cap Semi"))
    )
    (comp (ref "C80")
      (value "470nF")
      (footprint "SMD_0603_CAPC1608X80N")
      (description "Capacitor (Semiconductor SIM Model)")
      (fields (field (name "PUBLISHER") "Altium Limited"))
      (libsource (lib "Miscellaneous Devices") (part "Cap Semi"))
    )
    (comp (ref "C81")
      (value "470nF")
      (footprint "SMD_0603_CAPC1608X80N")
      (description "Capacitor (Semiconductor SIM Model)")
      (fields (field (name "PUBLISHER") "Altium Limited"))
      (libsource (lib "Miscellaneous Devices") (part "Cap Semi"))
    )
    (comp (ref "C82")
      (value "470nF")
      (footprint "SMD_0603_CAPC1608X80N")
      (description "Capacitor (Semiconductor SIM Model)")
      (fields (field (name "PUBLISHER") "Altium Limited"))
      (libsource (lib "Miscellaneous Devices") (part "Cap Semi"))
    )
    (comp (ref "C83")
      (value "470nF")
      (footprint "SMD_0603_CAPC1608X80N")
      (description "Capacitor (Semiconductor SIM Model)")
      (fields (field (name "PUBLISHER") "Altium Limited"))
      (libsource (lib "Miscellaneous Devices") (part "Cap Semi"))
    )
    (comp (ref "C84")
      (value "470nF")
      (footprint "SMD_0603_CAPC1608X80N")
      (description "Capacitor (Semiconductor SIM Model)")
      (fields (field (name "PUBLISHER") "Altium Limited"))
      (libsource (lib "Miscellaneous Devices") (part "Cap Semi"))
    )
    (comp (ref "C85")
      (value "18pF")
      (footprint "SMD_0603_CAPC1608X80N")
      (description "Capacitor")
      (libsource (lib "*") (part "CAP"))
    )
    (comp (ref "C86")
      (value "18pF")
      (footprint "SMD_0603_CAPC1608X80N")
      (description "Capacitor")
      (libsource (lib "*") (part "CAP"))
    )
    (comp (ref "C87")
      (value "470nF")
      (footprint "SMD_0603_CAPC1608X80N")
      (description "Capacitor (Semiconductor SIM Model)")
      (fields (field (name "PUBLISHER") "Altium Limited"))
      (libsource (lib "Miscellaneous Devices") (part "Cap Semi"))
    )
    (comp (ref "C88")
      (value "470nF")
      (footprint "SMD_0603_CAPC1608X80N")
      (description "Capacitor (Semiconductor SIM Model)")
      (fields (field (name "PUBLISHER") "Altium Limited"))
      (libsource (lib "Miscellaneous Devices") (part "Cap Semi"))
    )
    (comp (ref "C89")
      (value "470nF")
      (footprint "SMD_0603_CAPC1608X80N")
      (description "Capacitor (Semiconductor SIM Model)")
      (fields (field (name "PUBLISHER") "Altium Limited"))
      (libsource (lib "Miscellaneous Devices") (part "Cap Semi"))
    )
    (comp (ref "C90")
      (value "470nF")
      (footprint "SMD_0603_CAPC1608X80N")
      (description "Capacitor (Semiconductor SIM Model)")
      (fields (field (name "PUBLISHER") "Altium Limited"))
      (libsource (lib "Miscellaneous Devices") (part "Cap Semi"))
    )
    (comp (ref "C91")
      (value "470nF")
      (footprint "SMD_0603_CAPC1608X80N")
      (description "Capacitor (Semiconductor SIM Model)")
      (fields (field (name "PUBLISHER") "Altium Limited"))
      (libsource (lib "Miscellaneous Devices") (part "Cap Semi"))
    )
    (comp (ref "C92")
      (value "470nF")
      (footprint "SMD_0603_CAPC1608X80N")
      (description "Capacitor (Semiconductor SIM Model)")
      (fields (field (name "PUBLISHER") "Altium Limited"))
      (libsource (lib "Miscellaneous Devices") (part "Cap Semi"))
    )
    (comp (ref "C93")
      (value "470nF")
      (footprint "SMD_0603_CAPC1608X80N")
      (description "Capacitor (Semiconductor SIM Model)")
      (fields (field (name "PUBLISHER") "Altium Limited"))
      (libsource (lib "Miscellaneous Devices") (part "Cap Semi"))
    )
    (comp (ref "C94")
      (value "470nF")
      (footprint "SMD_0603_CAPC1608X80N")
      (description "Capacitor (Semiconductor SIM Model)")
      (fields (field (name "PUBLISHER") "Altium Limited"))
      (libsource (lib "Miscellaneous Devices") (part "Cap Semi"))
    )
    (comp (ref "C95")
      (value "470nF")
      (footprint "SMD_0603_CAPC1608X80N")
      (description "Capacitor (Semiconductor SIM Model)")
      (fields (field (name "PUBLISHER") "Altium Limited"))
      (libsource (lib "Miscellaneous Devices") (part "Cap Semi"))
    )
    (comp (ref "C96")
      (value "470nF")
      (footprint "SMD_0603_CAPC1608X80N")
      (description "Capacitor (Semiconductor SIM Model)")
      (fields (field (name "PUBLISHER") "Altium Limited"))
      (libsource (lib "Miscellaneous Devices") (part "Cap Semi"))
    )
    (comp (ref "C97")
      (value "470nF")
      (footprint "SMD_0603_CAPC1608X80N")
      (description "Capacitor (Semiconductor SIM Model)")
      (fields (field (name "PUBLISHER") "Altium Limited"))
      (libsource (lib "Miscellaneous Devices") (part "Cap Semi"))
    )
    (comp (ref "C98")
      (value "470nF")
      (footprint "SMD_0603_CAPC1608X80N")
      (description "Capacitor (Semiconductor SIM Model)")
      (fields (field (name "PUBLISHER") "Altium Limited"))
      (libsource (lib "Miscellaneous Devices") (part "Cap Semi"))
    )
    (comp (ref "C99")
      (value "470nF")
      (footprint "SMD_0603_CAPC1608X80N")
      (description "Capacitor (Semiconductor SIM Model)")
      (fields (field (name "PUBLISHER") "Altium Limited"))
      (libsource (lib "Miscellaneous Devices") (part "Cap Semi"))
    )
    (comp (ref "C100")
      (value "470nF")
      (footprint "SMD_0603_CAPC1608X80N")
      (description "Capacitor (Semiconductor SIM Model)")
      (fields (field (name "PUBLISHER") "Altium Limited"))
      (libsource (lib "Miscellaneous Devices") (part "Cap Semi"))
    )
    (comp (ref "C101")
      (value "470nF")
      (footprint "SMD_0603_CAPC1608X80N")
      (description "Capacitor (Semiconductor SIM Model)")
      (fields (field (name "PUBLISHER") "Altium Limited"))
      (libsource (lib "Miscellaneous Devices") (part "Cap Semi"))
    )
    (comp (ref "C102")
      (value "470nF")
      (footprint "SMD_0603_CAPC1608X80N")
      (description "Capacitor (Semiconductor SIM Model)")
      (fields (field (name "PUBLISHER") "Altium Limited"))
      (libsource (lib "Miscellaneous Devices") (part "Cap Semi"))
    )
    (comp (ref "C103")
      (value "470nF")
      (footprint "SMD_0603_CAPC1608X80N")
      (description "Capacitor (Semiconductor SIM Model)")
      (fields (field (name "PUBLISHER") "Altium Limited"))
      (libsource (lib "Miscellaneous Devices") (part "Cap Semi"))
    )
    (comp (ref "C104")
      (value "470nF")
      (footprint "SMD_0603_CAPC1608X80N")
      (description "Capacitor (Semiconductor SIM Model)")
      (fields (field (name "PUBLISHER") "Altium Limited"))
      (libsource (lib "Miscellaneous Devices") (part "Cap Semi"))
    )
    (comp (ref "C105")
      (value "470nF")
      (footprint "SMD_0603_CAPC1608X80N")
      (description "Capacitor (Semiconductor SIM Model)")
      (fields (field (name "PUBLISHER") "Altium Limited"))
      (libsource (lib "Miscellaneous Devices") (part "Cap Semi"))
    )
    (comp (ref "C106")
      (value "470nF")
      (footprint "SMD_0603_CAPC1608X80N")
      (description "Capacitor (Semiconductor SIM Model)")
      (fields (field (name "PUBLISHER") "Altium Limited"))
      (libsource (lib "Miscellaneous Devices") (part "Cap Semi"))
    )
    (comp (ref "C107")
      (value "470nF")
      (footprint "SMD_0603_CAPC1608X80N")
      (description "Capacitor (Semiconductor SIM Model)")
      (fields (field (name "PUBLISHER") "Altium Limited"))
      (libsource (lib "Miscellaneous Devices") (part "Cap Semi"))
    )
    (comp (ref "C108")
      (value "470nF")
      (footprint "SMD_0603_CAPC1608X80N")
      (description "Capacitor (Semiconductor SIM Model)")
      (fields (field (name "PUBLISHER") "Altium Limited"))
      (libsource (lib "Miscellaneous Devices") (part "Cap Semi"))
    )
    (comp (ref "C109")
      (value "470nF")
      (footprint "SMD_0603_CAPC1608X80N")
      (description "Capacitor (Semiconductor SIM Model)")
      (fields (field (name "PUBLISHER") "Altium Limited"))
      (libsource (lib "Miscellaneous Devices") (part "Cap Semi"))
    )
    (comp (ref "C110")
      (value "470nF")
      (footprint "SMD_0603_CAPC1608X80N")
      (description "Capacitor (Semiconductor SIM Model)")
      (fields (field (name "PUBLISHER") "Altium Limited"))
      (libsource (lib "Miscellaneous Devices") (part "Cap Semi"))
    )
    (comp (ref "C111")
      (value "470nF")
      (footprint "SMD_0603_CAPC1608X80N")
      (description "Capacitor (Semiconductor SIM Model)")
      (fields (field (name "PUBLISHER") "Altium Limited"))
      (libsource (lib "Miscellaneous Devices") (part "Cap Semi"))
    )
    (comp (ref "C112")
      (value "470nF")
      (footprint "SMD_0603_CAPC1608X80N")
      (description "Capacitor (Semiconductor SIM Model)")
      (fields (field (name "PUBLISHER") "Altium Limited"))
      (libsource (lib "Miscellaneous Devices") (part "Cap Semi"))
    )
    (comp (ref "C113")
      (value "470nF")
      (footprint "SMD_0603_CAPC1608X80N")
      (description "Capacitor (Semiconductor SIM Model)")
      (fields (field (name "PUBLISHER") "Altium Limited"))
      (libsource (lib "Miscellaneous Devices") (part "Cap Semi"))
    )
    (comp (ref "C114")
      (value "470nF")
      (footprint "SMD_0603_CAPC1608X80N")
      (description "Capacitor (Semiconductor SIM Model)")
      (fields (field (name "PUBLISHER") "Altium Limited"))
      (libsource (lib "Miscellaneous Devices") (part "Cap Semi"))
    )
    (comp (ref "C115")
      (value "470nF")
      (footprint "SMD_0603_CAPC1608X80N")
      (description "Capacitor (Semiconductor SIM Model)")
      (fields (field (name "PUBLISHER") "Altium Limited"))
      (libsource (lib "Miscellaneous Devices") (part "Cap Semi"))
    )
    (comp (ref "C116")
      (value "470nF")
      (footprint "SMD_0603_CAPC1608X80N")
      (description "Capacitor (Semiconductor SIM Model)")
      (fields (field (name "PUBLISHER") "Altium Limited"))
      (libsource (lib "Miscellaneous Devices") (part "Cap Semi"))
    )
    (comp (ref "C117")
      (value "470nF")
      (footprint "SMD_0603_CAPC1608X80N")
      (description "Capacitor (Semiconductor SIM Model)")
      (fields (field (name "PUBLISHER") "Altium Limited"))
      (libsource (lib "Miscellaneous Devices") (part "Cap Semi"))
    )
    (comp (ref "C118")
      (value "470nF")
      (footprint "SMD_0603_CAPC1608X80N")
      (description "Capacitor (Semiconductor SIM Model)")
      (fields (field (name "PUBLISHER") "Altium Limited"))
      (libsource (lib "Miscellaneous Devices") (part "Cap Semi"))
    )
    (comp (ref "C119")
      (value "470nF")
      (footprint "SMD_0603_CAPC1608X80N")
      (description "Capacitor (Semiconductor SIM Model)")
      (fields (field (name "PUBLISHER") "Altium Limited"))
      (libsource (lib "Miscellaneous Devices") (part "Cap Semi"))
    )
    (comp (ref "C120")
      (value "470nF")
      (footprint "SMD_0603_CAPC1608X80N")
      (description "Capacitor (Semiconductor SIM Model)")
      (fields (field (name "PUBLISHER") "Altium Limited"))
      (libsource (lib "Miscellaneous Devices") (part "Cap Semi"))
    )
    (comp (ref "C121")
      (value "470nF")
      (footprint "SMD_0603_CAPC1608X80N")
      (description "Capacitor (Semiconductor SIM Model)")
      (fields (field (name "PUBLISHER") "Altium Limited"))
      (libsource (lib "Miscellaneous Devices") (part "Cap Semi"))
    )
    (comp (ref "C122")
      (value "470nF")
      (footprint "SMD_0603_CAPC1608X80N")
      (description "Capacitor (Semiconductor SIM Model)")
      (fields (field (name "PUBLISHER") "Altium Limited"))
      (libsource (lib "Miscellaneous Devices") (part "Cap Semi"))
    )
    (comp (ref "C123")
      (value "470nF")
      (footprint "SMD_0603_CAPC1608X80N")
      (description "Capacitor (Semiconductor SIM Model)")
      (fields (field (name "PUBLISHER") "Altium Limited"))
      (libsource (lib "Miscellaneous Devices") (part "Cap Semi"))
    )
    (comp (ref "C124")
      (value "470nF")
      (footprint "SMD_0603_CAPC1608X80N")
      (description "Capacitor (Semiconductor SIM Model)")
      (fields (field (name "PUBLISHER") "Altium Limited"))
      (libsource (lib "Miscellaneous Devices") (part "Cap Semi"))
    )
    (comp (ref "C125")
      (value "470nF")
      (footprint "SMD_0603_CAPC1608X80N")
      (description "Capacitor (Semiconductor SIM Model)")
      (fields (field (name "PUBLISHER") "Altium Limited"))
      (libsource (lib "Miscellaneous Devices") (part "Cap Semi"))
    )
    (comp (ref "C126")
      (value "470nF")
      (footprint "SMD_0603_CAPC1608X80N")
      (description "Capacitor (Semiconductor SIM Model)")
      (fields (field (name "PUBLISHER") "Altium Limited"))
      (libsource (lib "Miscellaneous Devices") (part "Cap Semi"))
    )
    (comp (ref "C127")
      (value "470nF")
      (footprint "SMD_0603_CAPC1608X80N")
      (description "Capacitor (Semiconductor SIM Model)")
      (fields (field (name "PUBLISHER") "Altium Limited"))
      (libsource (lib "Miscellaneous Devices") (part "Cap Semi"))
    )
    (comp (ref "C128")
      (value "470nF")
      (footprint "SMD_0603_CAPC1608X80N")
      (description "Capacitor (Semiconductor SIM Model)")
      (fields (field (name "PUBLISHER") "Altium Limited"))
      (libsource (lib "Miscellaneous Devices") (part "Cap Semi"))
    )
    (comp (ref "C129")
      (value "470nF")
      (footprint "SMD_0603_CAPC1608X80N")
      (description "Capacitor (Semiconductor SIM Model)")
      (fields (field (name "PUBLISHER") "Altium Limited"))
      (libsource (lib "Miscellaneous Devices") (part "Cap Semi"))
    )
    (comp (ref "C130")
      (value "470nF")
      (footprint "SMD_0603_CAPC1608X80N")
      (description "Capacitor (Semiconductor SIM Model)")
      (fields (field (name "PUBLISHER") "Altium Limited"))
      (libsource (lib "Miscellaneous Devices") (part "Cap Semi"))
    )
    (comp (ref "C131")
      (value "470nF")
      (footprint "SMD_0603_CAPC1608X80N")
      (description "Capacitor (Semiconductor SIM Model)")
      (fields (field (name "PUBLISHER") "Altium Limited"))
      (libsource (lib "Miscellaneous Devices") (part "Cap Semi"))
    )
    (comp (ref "C132")
      (value "470nF")
      (footprint "SMD_0603_CAPC1608X80N")
      (description "Capacitor (Semiconductor SIM Model)")
      (fields (field (name "PUBLISHER") "Altium Limited"))
      (libsource (lib "Miscellaneous Devices") (part "Cap Semi"))
    )
    (comp (ref "C133")
      (value "470nF")
      (footprint "SMD_0603_CAPC1608X80N")
      (description "Capacitor (Semiconductor SIM Model)")
      (fields (field (name "PUBLISHER") "Altium Limited"))
      (libsource (lib "Miscellaneous Devices") (part "Cap Semi"))
    )
    (comp (ref "C134")
      (value "470nF")
      (footprint "SMD_0603_CAPC1608X80N")
      (description "Capacitor (Semiconductor SIM Model)")
      (fields (field (name "PUBLISHER") "Altium Limited"))
      (libsource (lib "Miscellaneous Devices") (part "Cap Semi"))
    )
    (comp (ref "C135")
      (value "470nF")
      (footprint "SMD_0603_CAPC1608X80N")
      (description "Capacitor (Semiconductor SIM Model)")
      (fields (field (name "PUBLISHER") "Altium Limited"))
      (libsource (lib "Miscellaneous Devices") (part "Cap Semi"))
    )
    (comp (ref "C136")
      (value "470nF")
      (footprint "SMD_0603_CAPC1608X80N")
      (description "Capacitor (Semiconductor SIM Model)")
      (fields (field (name "PUBLISHER") "Altium Limited"))
      (libsource (lib "Miscellaneous Devices") (part "Cap Semi"))
    )
    (comp (ref "C137")
      (value "470nF")
      (footprint "SMD_0603_CAPC1608X80N")
      (description "Capacitor (Semiconductor SIM Model)")
      (fields (field (name "PUBLISHER") "Altium Limited"))
      (libsource (lib "Miscellaneous Devices") (part "Cap Semi"))
    )
    (comp (ref "C138")
      (value "470nF")
      (footprint "SMD_0603_CAPC1608X80N")
      (description "Capacitor (Semiconductor SIM Model)")
      (fields (field (name "PUBLISHER") "Altium Limited"))
      (libsource (lib "Miscellaneous Devices") (part "Cap Semi"))
    )
    (comp (ref "C139")
      (value "470nF")
      (footprint "SMD_0603_CAPC1608X80N")
      (description "Capacitor (Semiconductor SIM Model)")
      (fields (field (name "PUBLISHER") "Altium Limited"))
      (libsource (lib "Miscellaneous Devices") (part "Cap Semi"))
    )
    (comp (ref "C140")
      (value "470nF")
      (footprint "SMD_0603_CAPC1608X80N")
      (description "Capacitor (Semiconductor SIM Model)")
      (fields (field (name "PUBLISHER") "Altium Limited"))
      (libsource (lib "Miscellaneous Devices") (part "Cap Semi"))
    )
    (comp (ref "C141")
      (value "470nF")
      (footprint "SMD_0603_CAPC1608X80N")
      (description "Capacitor (Semiconductor SIM Model)")
      (fields (field (name "PUBLISHER") "Altium Limited"))
      (libsource (lib "Miscellaneous Devices") (part "Cap Semi"))
    )
    (comp (ref "C142")
      (value "470nF")
      (footprint "SMD_0603_CAPC1608X80N")
      (description "Capacitor (Semiconductor SIM Model)")
      (fields (field (name "PUBLISHER") "Altium Limited"))
      (libsource (lib "Miscellaneous Devices") (part "Cap Semi"))
    )
    (comp (ref "C143")
      (value "470nF")
      (footprint "SMD_0603_CAPC1608X80N")
      (description "Capacitor (Semiconductor SIM Model)")
      (fields (field (name "PUBLISHER") "Altium Limited"))
      (libsource (lib "Miscellaneous Devices") (part "Cap Semi"))
    )
    (comp (ref "C144")
      (value "470nF")
      (footprint "SMD_0603_CAPC1608X80N")
      (description "Capacitor (Semiconductor SIM Model)")
      (fields (field (name "PUBLISHER") "Altium Limited"))
      (libsource (lib "Miscellaneous Devices") (part "Cap Semi"))
    )
    (comp (ref "C145")
      (value "470nF")
      (footprint "SMD_0603_CAPC1608X80N")
      (description "Capacitor (Semiconductor SIM Model)")
      (fields (field (name "PUBLISHER") "Altium Limited"))
      (libsource (lib "Miscellaneous Devices") (part "Cap Semi"))
    )
    (comp (ref "C146")
      (value "470nF")
      (footprint "SMD_0603_CAPC1608X80N")
      (description "Capacitor (Semiconductor SIM Model)")
      (fields (field (name "PUBLISHER") "Altium Limited"))
      (libsource (lib "Miscellaneous Devices") (part "Cap Semi"))
    )
    (comp (ref "C147")
      (value "470nF")
      (footprint "SMD_0603_CAPC1608X80N")
      (description "Capacitor (Semiconductor SIM Model)")
      (fields (field (name "PUBLISHER") "Altium Limited"))
      (libsource (lib "Miscellaneous Devices") (part "Cap Semi"))
    )
    (comp (ref "C148")
      (value "470nF")
      (footprint "SMD_0603_CAPC1608X80N")
      (description "Capacitor (Semiconductor SIM Model)")
      (fields (field (name "PUBLISHER") "Altium Limited"))
      (libsource (lib "Miscellaneous Devices") (part "Cap Semi"))
    )
    (comp (ref "C149")
      (value "470nF")
      (footprint "SMD_0603_CAPC1608X80N")
      (description "Capacitor (Semiconductor SIM Model)")
      (fields (field (name "PUBLISHER") "Altium Limited"))
      (libsource (lib "Miscellaneous Devices") (part "Cap Semi"))
    )
    (comp (ref "C150")
      (value "470nF")
      (footprint "SMD_0603_CAPC1608X80N")
      (description "Capacitor (Semiconductor SIM Model)")
      (fields (field (name "PUBLISHER") "Altium Limited"))
      (libsource (lib "Miscellaneous Devices") (part "Cap Semi"))
    )
    (comp (ref "C151")
      (value "470nF")
      (footprint "SMD_0603_CAPC1608X80N")
      (description "Capacitor (Semiconductor SIM Model)")
      (fields (field (name "PUBLISHER") "Altium Limited"))
      (libsource (lib "Miscellaneous Devices") (part "Cap Semi"))
    )
    (comp (ref "C152")
      (value "470nF")
      (footprint "SMD_0603_CAPC1608X80N")
      (description "Capacitor (Semiconductor SIM Model)")
      (fields (field (name "PUBLISHER") "Altium Limited"))
      (libsource (lib "Miscellaneous Devices") (part "Cap Semi"))
    )
    (comp (ref "C153")
      (value "470nF")
      (footprint "SMD_0603_CAPC1608X80N")
      (description "Capacitor (Semiconductor SIM Model)")
      (fields (field (name "PUBLISHER") "Altium Limited"))
      (libsource (lib "Miscellaneous Devices") (part "Cap Semi"))
    )
    (comp (ref "C154")
      (value "470nF")
      (footprint "SMD_0603_CAPC1608X80N")
      (description "Capacitor (Semiconductor SIM Model)")
      (fields (field (name "PUBLISHER") "Altium Limited"))
      (libsource (lib "Miscellaneous Devices") (part "Cap Semi"))
    )
    (comp (ref "C155")
      (value "470nF")
      (footprint "SMD_0603_CAPC1608X80N")
      (description "Capacitor (Semiconductor SIM Model)")
      (fields (field (name "PUBLISHER") "Altium Limited"))
      (libsource (lib "Miscellaneous Devices") (part "Cap Semi"))
    )
    (comp (ref "C156")
      (value "470nF")
      (footprint "SMD_0603_CAPC1608X80N")
      (description "Capacitor (Semiconductor SIM Model)")
      (fields (field (name "PUBLISHER") "Altium Limited"))
      (libsource (lib "Miscellaneous Devices") (part "Cap Semi"))
    )
    (comp (ref "C157")
      (value "470nF")
      (footprint "SMD_0603_CAPC1608X80N")
      (description "Capacitor (Semiconductor SIM Model)")
      (fields (field (name "PUBLISHER") "Altium Limited"))
      (libsource (lib "Miscellaneous Devices") (part "Cap Semi"))
    )
    (comp (ref "C158")
      (value "470nF")
      (footprint "SMD_0603_CAPC1608X80N")
      (description "Capacitor (Semiconductor SIM Model)")
      (fields (field (name "PUBLISHER") "Altium Limited"))
      (libsource (lib "Miscellaneous Devices") (part "Cap Semi"))
    )
    (comp (ref "C159")
      (value "470nF")
      (footprint "SMD_0603_CAPC1608X80N")
      (description "Capacitor (Semiconductor SIM Model)")
      (fields (field (name "PUBLISHER") "Altium Limited"))
      (libsource (lib "Miscellaneous Devices") (part "Cap Semi"))
    )
    (comp (ref "C160")
      (value "470nF")
      (footprint "SMD_0603_CAPC1608X80N")
      (description "Capacitor (Semiconductor SIM Model)")
      (fields (field (name "PUBLISHER") "Altium Limited"))
      (libsource (lib "Miscellaneous Devices") (part "Cap Semi"))
    )
    (comp (ref "C161")
      (value "470nF")
      (footprint "SMD_0603_CAPC1608X80N")
      (description "Capacitor (Semiconductor SIM Model)")
      (fields (field (name "PUBLISHER") "Altium Limited"))
      (libsource (lib "Miscellaneous Devices") (part "Cap Semi"))
    )
    (comp (ref "C162")
      (value "470nF")
      (footprint "SMD_0603_CAPC1608X80N")
      (description "Capacitor (Semiconductor SIM Model)")
      (fields (field (name "PUBLISHER") "Altium Limited"))
      (libsource (lib "Miscellaneous Devices") (part "Cap Semi"))
    )
    (comp (ref "C163")
      (value "470nF")
      (footprint "SMD_0603_CAPC1608X80N")
      (description "Capacitor (Semiconductor SIM Model)")
      (fields (field (name "PUBLISHER") "Altium Limited"))
      (libsource (lib "Miscellaneous Devices") (part "Cap Semi"))
    )
    (comp (ref "C164")
      (value "470nF")
      (footprint "SMD_0603_CAPC1608X80N")
      (description "Capacitor (Semiconductor SIM Model)")
      (fields (field (name "PUBLISHER") "Altium Limited"))
      (libsource (lib "Miscellaneous Devices") (part "Cap Semi"))
    )
    (comp (ref "C165")
      (value "470nF")
      (footprint "SMD_0603_CAPC1608X80N")
      (description "Capacitor (Semiconductor SIM Model)")
      (fields (field (name "PUBLISHER") "Altium Limited"))
      (libsource (lib "Miscellaneous Devices") (part "Cap Semi"))
    )
    (comp (ref "C166")
      (value "470nF")
      (footprint "SMD_0603_CAPC1608X80N")
      (description "Capacitor (Semiconductor SIM Model)")
      (fields (field (name "PUBLISHER") "Altium Limited"))
      (libsource (lib "Miscellaneous Devices") (part "Cap Semi"))
    )
    (comp (ref "C167")
      (value "470nF")
      (footprint "SMD_0603_CAPC1608X80N")
      (description "Capacitor (Semiconductor SIM Model)")
      (fields (field (name "PUBLISHER") "Altium Limited"))
      (libsource (lib "Miscellaneous Devices") (part "Cap Semi"))
    )
    (comp (ref "C168")
      (value "470nF")
      (footprint "SMD_0603_CAPC1608X80N")
      (description "Capacitor (Semiconductor SIM Model)")
      (fields (field (name "PUBLISHER") "Altium Limited"))
      (libsource (lib "Miscellaneous Devices") (part "Cap Semi"))
    )
    (comp (ref "C169")
      (value "470nF")
      (footprint "SMD_0603_CAPC1608X80N")
      (description "Capacitor (Semiconductor SIM Model)")
      (fields (field (name "PUBLISHER") "Altium Limited"))
      (libsource (lib "Miscellaneous Devices") (part "Cap Semi"))
    )
    (comp (ref "C170")
      (value "470nF")
      (footprint "SMD_0603_CAPC1608X80N")
      (description "Capacitor (Semiconductor SIM Model)")
      (fields (field (name "PUBLISHER") "Altium Limited"))
      (libsource (lib "Miscellaneous Devices") (part "Cap Semi"))
    )
    (comp (ref "C171")
      (value "470nF")
      (footprint "SMD_0603_CAPC1608X80N")
      (description "Capacitor (Semiconductor SIM Model)")
      (fields (field (name "PUBLISHER") "Altium Limited"))
      (libsource (lib "Miscellaneous Devices") (part "Cap Semi"))
    )
    (comp (ref "C172")
      (value "470nF")
      (footprint "SMD_0603_CAPC1608X80N")
      (description "Capacitor (Semiconductor SIM Model)")
      (fields (field (name "PUBLISHER") "Altium Limited"))
      (libsource (lib "Miscellaneous Devices") (part "Cap Semi"))
    )
    (comp (ref "C173")
      (value "470nF")
      (footprint "SMD_0603_CAPC1608X80N")
      (description "Capacitor (Semiconductor SIM Model)")
      (fields (field (name "PUBLISHER") "Altium Limited"))
      (libsource (lib "Miscellaneous Devices") (part "Cap Semi"))
    )
    (comp (ref "C174")
      (value "470nF")
      (footprint "SMD_0603_CAPC1608X80N")
      (description "Capacitor (Semiconductor SIM Model)")
      (fields (field (name "PUBLISHER") "Altium Limited"))
      (libsource (lib "Miscellaneous Devices") (part "Cap Semi"))
    )
    (comp (ref "C175")
      (value "470nF")
      (footprint "SMD_0603_CAPC1608X80N")
      (description "Capacitor (Semiconductor SIM Model)")
      (fields (field (name "PUBLISHER") "Altium Limited"))
      (libsource (lib "Miscellaneous Devices") (part "Cap Semi"))
    )
    (comp (ref "C176")
      (value "470nF")
      (footprint "SMD_0603_CAPC1608X80N")
      (description "Capacitor (Semiconductor SIM Model)")
      (fields (field (name "PUBLISHER") "Altium Limited"))
      (libsource (lib "Miscellaneous Devices") (part "Cap Semi"))
    )
    (comp (ref "C177")
      (value "470nF")
      (footprint "SMD_0603_CAPC1608X80N")
      (description "Capacitor (Semiconductor SIM Model)")
      (fields (field (name "PUBLISHER") "Altium Limited"))
      (libsource (lib "Miscellaneous Devices") (part "Cap Semi"))
    )
    (comp (ref "C178")
      (value "470nF")
      (footprint "SMD_0603_CAPC1608X80N")
      (description "Capacitor (Semiconductor SIM Model)")
      (fields (field (name "PUBLISHER") "Altium Limited"))
      (libsource (lib "Miscellaneous Devices") (part "Cap Semi"))
    )
    (comp (ref "C179")
      (value "470nF")
      (footprint "SMD_0603_CAPC1608X80N")
      (description "Capacitor (Semiconductor SIM Model)")
      (fields (field (name "PUBLISHER") "Altium Limited"))
      (libsource (lib "Miscellaneous Devices") (part "Cap Semi"))
    )
    (comp (ref "C180")
      (value "470nF")
      (footprint "SMD_0603_CAPC1608X80N")
      (description "Capacitor (Semiconductor SIM Model)")
      (fields (field (name "PUBLISHER") "Altium Limited"))
      (libsource (lib "Miscellaneous Devices") (part "Cap Semi"))
    )
    (comp (ref "C181")
      (value "470nF")
      (footprint "SMD_0603_CAPC1608X80N")
      (description "Capacitor (Semiconductor SIM Model)")
      (fields (field (name "PUBLISHER") "Altium Limited"))
      (libsource (lib "Miscellaneous Devices") (part "Cap Semi"))
    )
    (comp (ref "C182")
      (value "470nF")
      (footprint "SMD_0603_CAPC1608X80N")
      (description "Capacitor (Semiconductor SIM Model)")
      (fields (field (name "PUBLISHER") "Altium Limited"))
      (libsource (lib "Miscellaneous Devices") (part "Cap Semi"))
    )
    (comp (ref "C183")
      (value "470nF")
      (footprint "SMD_0603_CAPC1608X80N")
      (description "Capacitor (Semiconductor SIM Model)")
      (fields (field (name "PUBLISHER") "Altium Limited"))
      (libsource (lib "Miscellaneous Devices") (part "Cap Semi"))
    )
    (comp (ref "C184")
      (value "470nF")
      (footprint "SMD_0603_CAPC1608X80N")
      (description "Capacitor (Semiconductor SIM Model)")
      (fields (field (name "PUBLISHER") "Altium Limited"))
      (libsource (lib "Miscellaneous Devices") (part "Cap Semi"))
    )
    (comp (ref "C185")
      (value "470nF")
      (footprint "SMD_0603_CAPC1608X80N")
      (description "Capacitor (Semiconductor SIM Model)")
      (fields (field (name "PUBLISHER") "Altium Limited"))
      (libsource (lib "Miscellaneous Devices") (part "Cap Semi"))
    )
    (comp (ref "C186")
      (value "470nF")
      (footprint "SMD_0603_CAPC1608X80N")
      (description "Capacitor (Semiconductor SIM Model)")
      (fields (field (name "PUBLISHER") "Altium Limited"))
      (libsource (lib "Miscellaneous Devices") (part "Cap Semi"))
    )
    (comp (ref "C187")
      (value "10uF/16V")
      (footprint "SMD_0805_CAPC2012X145N")
      (description "Capacitor")
      (libsource (lib "*") (part "CAP"))
    )
    (comp (ref "C188")
      (value "10uF/16V")
      (footprint "SMD_0805_CAPC2012X145N")
      (description "Capacitor")
      (libsource (lib "*") (part "CAP"))
    )
    (comp (ref "C189")
      (value "100nF/50V")
      (footprint "SMD_0805_CAPC2012X145N")
      (description "Capacitor")
      (libsource (lib "*") (part "CAP"))
    )
    (comp (ref "C190")
      (value "10uF/16V")
      (footprint "SMD_0805_CAPC2012X145N")
      (description "Capacitor")
      (libsource (lib "*") (part "CAP"))
    )
    (comp (ref "C191")
      (value "10uF/16V")
      (footprint "SMD_0805_CAPC2012X145N")
      (description "Capacitor")
      (libsource (lib "*") (part "CAP"))
    )
    (comp (ref "C192")
      (value "10uF/16V")
      (footprint "SMD_0805_CAPC2012X145N")
      (description "Capacitor")
      (libsource (lib "*") (part "CAP"))
    )
    (comp (ref "C193")
      (value "10uF/16V")
      (footprint "SMD_0805_CAPC2012X145N")
      (description "Capacitor")
      (libsource (lib "*") (part "CAP"))
    )
    (comp (ref "C194")
      (value "10uF/16V")
      (footprint "SMD_0805_CAPC2012X145N")
      (description "Capacitor")
      (libsource (lib "*") (part "CAP"))
    )
    (comp (ref "C195")
      (value "10uF/16V")
      (footprint "SMD_0805_CAPC2012X145N")
      (description "Capacitor")
      (libsource (lib "*") (part "CAP"))
    )
    (comp (ref "C196")
      (value "10uF/16V")
      (footprint "SMD_0805_CAPC2012X145N")
      (description "Capacitor")
      (libsource (lib "*") (part "CAP"))
    )
    (comp (ref "C197")
      (value "10uF/16V")
      (footprint "SMD_0805_CAPC2012X145N")
      (description "Capacitor")
      (libsource (lib "*") (part "CAP"))
    )
    (comp (ref "C198")
      (value "22uF/6.3V")
      (footprint "SMD_0805_CAPC2012X145N")
      (description "Capacitor")
      (libsource (lib "*") (part "CAP"))
    )
    (comp (ref "C199")
      (value "22uF/6.3V")
      (footprint "SMD_0805_CAPC2012X145N")
      (description "Capacitor")
      (libsource (lib "*") (part "CAP"))
    )
    (comp (ref "C200")
      (value "22uF/6.3V")
      (footprint "SMD_0805_CAPC2012X145N")
      (description "Capacitor")
      (libsource (lib "*") (part "CAP"))
    )
    (comp (ref "C201")
      (value "22uF/6.3V")
      (footprint "SMD_0805_CAPC2012X145N")
      (description "Capacitor")
      (libsource (lib "*") (part "CAP"))
    )
    (comp (ref "C202")
      (value "22uF/6.3V")
      (footprint "SMD_0805_CAPC2012X145N")
      (description "Capacitor")
      (libsource (lib "*") (part "CAP"))
    )
    (comp (ref "C203")
      (value "22uF/6.3V")
      (footprint "SMD_0805_CAPC2012X145N")
      (description "Capacitor")
      (libsource (lib "*") (part "CAP"))
    )
    (comp (ref "C204")
      (value "22uF/6.3V")
      (footprint "SMD_0805_CAPC2012X145N")
      (description "Capacitor")
      (libsource (lib "*") (part "CAP"))
    )
    (comp (ref "C205")
      (value "22uF/6.3V")
      (footprint "SMD_0805_CAPC2012X145N")
      (description "Capacitor")
      (libsource (lib "*") (part "CAP"))
    )
    (comp (ref "C206")
      (value "(OPT) 2.2nF")
      (footprint "SMD_0805_CAPC2012X145N")
      (description "Capacitor")
      (libsource (lib "*") (part "CAP"))
    )
    (comp (ref "C207")
      (value "10uF/16V")
      (footprint "SMD_0805_CAPC2012X145N")
      (description "Capacitor")
      (libsource (lib "*") (part "CAP"))
    )
    (comp (ref "C208")
      (value "(OPT)2200uF/16V")
      (footprint "PTH_CAPPR500-1300X2250")
      (libsource (lib "EPIQ_DND_CIS_Library") (part "C_POL"))
    )
    (comp (ref "C209")
      (value "1uF")
      (footprint "SMD_0805_CAPC2012X145N")
      (description "Capacitor")
      (libsource (lib "*") (part "CAP"))
    )
    (comp (ref "C210")
      (value "(OPT)2200uF/16V")
      (footprint "PTH_CAPPR500-1300X2250")
      (libsource (lib "EPIQ_DND_CIS_Library") (part "C_POL"))
    )
    (comp (ref "C211")
      (value "22uF/6.3V")
      (footprint "SMD_0805_CAPC2012X145N")
      (description "Capacitor")
      (libsource (lib "*") (part "CAP"))
    )
    (comp (ref "C212")
      (value "姨0J332M-RBJ21")
      (footprint "PTH_CAPPR500-1300X2250")
      (libsource (lib "EPIQ_DND_CIS_Library") (part "C_POL"))
    )
    (comp (ref "C213")
      (value "10uF/16V")
      (footprint "SMD_0805_CAPC2012X145N")
      (description "Capacitor")
      (libsource (lib "*") (part "CAP"))
    )
    (comp (ref "C214")
      (value "10uF/16V")
      (footprint "SMD_0805_CAPC2012X145N")
      (description "Capacitor")
      (libsource (lib "*") (part "CAP"))
    )
    (comp (ref "C215")
      (value "10uF/16V")
      (footprint "SMD_0805_CAPC2012X145N")
      (description "Capacitor")
      (libsource (lib "*") (part "CAP"))
    )
    (comp (ref "C216")
      (value "10uF/16V")
      (footprint "SMD_0805_CAPC2012X145N")
      (description "Capacitor")
      (libsource (lib "*") (part "CAP"))
    )
    (comp (ref "C217")
      (value "10uF/16V")
      (footprint "SMD_0805_CAPC2012X145N")
      (description "Capacitor")
      (libsource (lib "*") (part "CAP"))
    )
    (comp (ref "C218")
      (value "10uF/16V")
      (footprint "SMD_0805_CAPC2012X145N")
      (description "Capacitor")
      (libsource (lib "*") (part "CAP"))
    )
    (comp (ref "C219")
      (value "10uF/16V")
      (footprint "SMD_0805_CAPC2012X145N")
      (description "Capacitor")
      (libsource (lib "*") (part "CAP"))
    )
    (comp (ref "C220")
      (value "22uF/6.3V")
      (footprint "SMD_0805_CAPC2012X145N")
      (description "Capacitor")
      (libsource (lib "*") (part "CAP"))
    )
    (comp (ref "C221")
      (value "22uF/6.3V")
      (footprint "SMD_0805_CAPC2012X145N")
      (description "Capacitor")
      (libsource (lib "*") (part "CAP"))
    )
    (comp (ref "C222")
      (value "22uF/6.3V")
      (footprint "SMD_0805_CAPC2012X145N")
      (description "Capacitor")
      (libsource (lib "*") (part "CAP"))
    )
    (comp (ref "C223")
      (value "22uF/6.3V")
      (footprint "SMD_0805_CAPC2012X145N")
      (description "Capacitor")
      (libsource (lib "*") (part "CAP"))
    )
    (comp (ref "C224")
      (value "22uF/6.3V")
      (footprint "SMD_0805_CAPC2012X145N")
      (description "Capacitor")
      (libsource (lib "*") (part "CAP"))
    )
    (comp (ref "C225")
      (value "22uF/6.3V")
      (footprint "SMD_0805_CAPC2012X145N")
      (description "Capacitor")
      (libsource (lib "*") (part "CAP"))
    )
    (comp (ref "C226")
      (value "22uF/6.3V")
      (footprint "SMD_0805_CAPC2012X145N")
      (description "Capacitor")
      (libsource (lib "*") (part "CAP"))
    )
    (comp (ref "C227")
      (value "22uF/6.3V")
      (footprint "SMD_0805_CAPC2012X145N")
      (description "Capacitor")
      (libsource (lib "*") (part "CAP"))
    )
    (comp (ref "C228")
      (value "姨0J332M-RBJ21")
      (footprint "PTH_CAPPR500-1300X2250")
      (libsource (lib "EPIQ_DND_CIS_Library") (part "C_POL"))
    )
    (comp (ref "C229")
      (value "22uF/6.3V")
      (footprint "SMD_0805_CAPC2012X145N")
      (description "Capacitor")
      (libsource (lib "*") (part "CAP"))
    )
    (comp (ref "C230")
      (value "10uF/16V")
      (footprint "SMD_0805_CAPC2012X145N")
      (description "Capacitor")
      (libsource (lib "*") (part "CAP"))
    )
    (comp (ref "C231")
      (value "10uF/16V")
      (footprint "SMD_0805_CAPC2012X145N")
      (description "Capacitor")
      (libsource (lib "*") (part "CAP"))
    )
    (comp (ref "C232")
      (value "姨0J332M-RBJ21")
      (footprint "PTH_CAPPR500-1300X2250")
      (libsource (lib "EPIQ_DND_CIS_Library") (part "C_POL"))
    )
    (comp (ref "C233")
      (value "22uF/6.3V")
      (footprint "SMD_0805_CAPC2012X145N")
      (description "Capacitor")
      (libsource (lib "*") (part "CAP"))
    )
    (comp (ref "C234")
      (value "22uF/6.3V")
      (footprint "SMD_0805_CAPC2012X145N")
      (description "Capacitor")
      (libsource (lib "*") (part "CAP"))
    )
    (comp (ref "C235")
      (value "22uF/6.3V")
      (footprint "SMD_0805_CAPC2012X145N")
      (description "Capacitor")
      (libsource (lib "*") (part "CAP"))
    )
    (comp (ref "C236")
      (value "22uF/6.3V")
      (footprint "SMD_0805_CAPC2012X145N")
      (description "Capacitor")
      (libsource (lib "*") (part "CAP"))
    )
    (comp (ref "C237")
      (value "22uF/6.3V")
      (footprint "SMD_0805_CAPC2012X145N")
      (description "Capacitor")
      (libsource (lib "*") (part "CAP"))
    )
    (comp (ref "C238")
      (value "姨0J332M-RBJ21")
      (footprint "PTH_CAPPR500-1300X2250")
      (libsource (lib "EPIQ_DND_CIS_Library") (part "C_POL"))
    )
    (comp (ref "C239")
      (value "姨0J332M-RBJ21")
      (footprint "PTH_CAPPR500-1300X2250")
      (libsource (lib "EPIQ_DND_CIS_Library") (part "C_POL"))
    )
    (comp (ref "C240")
      (value "22uF/6.3V")
      (footprint "SMD_0805_CAPC2012X145N")
      (description "Capacitor")
      (libsource (lib "*") (part "CAP"))
    )
    (comp (ref "C241")
      (value "22uF/6.3V")
      (footprint "SMD_0805_CAPC2012X145N")
      (description "Capacitor")
      (libsource (lib "*") (part "CAP"))
    )
    (comp (ref "C242")
      (value "22uF/6.3V")
      (footprint "SMD_0805_CAPC2012X145N")
      (description "Capacitor")
      (libsource (lib "*") (part "CAP"))
    )
    (comp (ref "C243")
      (value "22uF/6.3V")
      (footprint "SMD_0805_CAPC2012X145N")
      (description "Capacitor")
      (libsource (lib "*") (part "CAP"))
    )
    (comp (ref "C244")
      (value "22uF/6.3V")
      (footprint "SMD_0805_CAPC2012X145N")
      (description "Capacitor")
      (libsource (lib "*") (part "CAP"))
    )
    (comp (ref "C245")
      (value "22uF/6.3V")
      (footprint "SMD_0805_CAPC2012X145N")
      (description "Capacitor")
      (libsource (lib "*") (part "CAP"))
    )
    (comp (ref "C246")
      (value "22uF/6.3V")
      (footprint "SMD_0805_CAPC2012X145N")
      (description "Capacitor")
      (libsource (lib "*") (part "CAP"))
    )
    (comp (ref "C247")
      (value "22uF/6.3V")
      (footprint "SMD_0805_CAPC2012X145N")
      (description "Capacitor")
      (libsource (lib "*") (part "CAP"))
    )
    (comp (ref "C248")
      (value "22uF/6.3V")
      (footprint "SMD_0805_CAPC2012X145N")
      (description "Capacitor")
      (libsource (lib "*") (part "CAP"))
    )
    (comp (ref "C249")
      (value "22uF/6.3V")
      (footprint "SMD_0805_CAPC2012X145N")
      (description "Capacitor")
      (libsource (lib "*") (part "CAP"))
    )
    (comp (ref "C250")
      (value "22uF/6.3V")
      (footprint "SMD_0805_CAPC2012X145N")
      (description "Capacitor")
      (libsource (lib "*") (part "CAP"))
    )
    (comp (ref "C251")
      (value "1nF")
      (footprint "SMD_0603_CAPC1608X80N")
      (description "Capacitor")
      (libsource (lib "*") (part "CAP"))
    )
    (comp (ref "C252")
      (value "1uF/16V")
      (footprint "SMD_0805_CAPC2012X145N")
      (description "Capacitor")
      (libsource (lib "*") (part "CAP"))
    )
    (comp (ref "C253")
      (value "100pF")
      (footprint "SMD_0603_CAPC1608X80N")
      (description "Capacitor")
      (libsource (lib "*") (part "CAP"))
    )
    (comp (ref "C254")
      (value "100pF")
      (footprint "SMD_0603_CAPC1608X80N")
      (description "Capacitor")
      (libsource (lib "*") (part "CAP"))
    )
    (comp (ref "C255")
      (value "100nF")
      (footprint "SMD_0603_CAPC1608X80N")
      (description "Capacitor")
      (libsource (lib "*") (part "CAP"))
    )
    (comp (ref "C256")
      (value "姨0J332M-RBJ21")
      (footprint "PTH_CAPPR500-1300X2250")
      (libsource (lib "EPIQ_DND_CIS_Library") (part "C_POL"))
    )
    (comp (ref "C257")
      (value "姨0J332M-RBJ21")
      (footprint "PTH_CAPPR500-1300X2250")
      (libsource (lib "EPIQ_DND_CIS_Library") (part "C_POL"))
    )
    (comp (ref "C258")
      (value "22uF/6.3V")
      (footprint "SMD_0805_CAPC2012X145N")
      (description "Capacitor")
      (libsource (lib "*") (part "CAP"))
    )
    (comp (ref "C259")
      (value "22uF/6.3V")
      (footprint "SMD_0805_CAPC2012X145N")
      (description "Capacitor")
      (libsource (lib "*") (part "CAP"))
    )
    (comp (ref "C260")
      (value "22uF/6.3V")
      (footprint "SMD_0805_CAPC2012X145N")
      (description "Capacitor")
      (libsource (lib "*") (part "CAP"))
    )
    (comp (ref "C261")
      (value "22uF/6.3V")
      (footprint "SMD_0805_CAPC2012X145N")
      (description "Capacitor")
      (libsource (lib "*") (part "CAP"))
    )
    (comp (ref "C262")
      (value "22uF/6.3V")
      (footprint "SMD_0805_CAPC2012X145N")
      (description "Capacitor")
      (libsource (lib "*") (part "CAP"))
    )
    (comp (ref "C263")
      (value "10uF/16V")
      (footprint "SMD_0805_CAPC2012X145N")
      (description "Capacitor")
      (libsource (lib "*") (part "CAP"))
    )
    (comp (ref "C264")
      (value "10uF/16V")
      (footprint "SMD_0805_CAPC2012X145N")
      (description "Capacitor")
      (libsource (lib "*") (part "CAP"))
    )
    (comp (ref "C265")
      (value "10uF/16V")
      (footprint "SMD_0805_CAPC2012X145N")
      (description "Capacitor")
      (libsource (lib "*") (part "CAP"))
    )
    (comp (ref "C266")
      (value "10uF/16V")
      (footprint "SMD_0805_CAPC2012X145N")
      (description "Capacitor")
      (libsource (lib "*") (part "CAP"))
    )
    (comp (ref "C267")
      (value "10uF/16V")
      (footprint "SMD_0805_CAPC2012X145N")
      (description "Capacitor")
      (libsource (lib "*") (part "CAP"))
    )
    (comp (ref "C268")
      (value "10uF/16V")
      (footprint "SMD_0805_CAPC2012X145N")
      (description "Capacitor")
      (libsource (lib "*") (part "CAP"))
    )
    (comp (ref "C269")
      (value "10uF/16V")
      (footprint "SMD_0805_CAPC2012X145N")
      (description "Capacitor")
      (libsource (lib "*") (part "CAP"))
    )
    (comp (ref "C270")
      (value "10uF/16V")
      (footprint "SMD_0805_CAPC2012X145N")
      (description "Capacitor")
      (libsource (lib "*") (part "CAP"))
    )
    (comp (ref "C271")
      (value "姨0J332M-RBJ21")
      (footprint "PTH_CAPPR500-1300X2250")
      (libsource (lib "EPIQ_DND_CIS_Library") (part "C_POL"))
    )
    (comp (ref "C272")
      (value "(OPT)2200uF/16V")
      (footprint "PTH_CAPPR500-1300X2250")
      (libsource (lib "EPIQ_DND_CIS_Library") (part "C_POL"))
    )
    (comp (ref "C273")
      (value "10uF/16V")
      (footprint "SMD_0805_CAPC2012X145N")
      (description "Capacitor")
      (libsource (lib "*") (part "CAP"))
    )
    (comp (ref "C274")
      (value "10uF/16V")
      (footprint "SMD_0805_CAPC2012X145N")
      (description "Capacitor")
      (libsource (lib "*") (part "CAP"))
    )
    (comp (ref "C275")
      (value "10uF/16V")
      (footprint "SMD_0805_CAPC2012X145N")
      (description "Capacitor")
      (libsource (lib "*") (part "CAP"))
    )
    (comp (ref "C276")
      (value "10uF/16V")
      (footprint "SMD_0805_CAPC2012X145N")
      (description "Capacitor")
      (libsource (lib "*") (part "CAP"))
    )
    (comp (ref "C277")
      (value "10uF/16V")
      (footprint "SMD_0805_CAPC2012X145N")
      (description "Capacitor")
      (libsource (lib "*") (part "CAP"))
    )
    (comp (ref "C278")
      (value "10uF/16V")
      (footprint "SMD_0805_CAPC2012X145N")
      (description "Capacitor")
      (libsource (lib "*") (part "CAP"))
    )
    (comp (ref "C279")
      (value "10uF/16V")
      (footprint "SMD_0805_CAPC2012X145N")
      (description "Capacitor")
      (libsource (lib "*") (part "CAP"))
    )
    (comp (ref "C280")
      (value "10uF/16V")
      (footprint "SMD_0805_CAPC2012X145N")
      (description "Capacitor")
      (libsource (lib "*") (part "CAP"))
    )
    (comp (ref "C281")
      (value "(OPT)2200uF/16V")
      (footprint "PTH_CAPPR500-1300X2250")
      (libsource (lib "EPIQ_DND_CIS_Library") (part "C_POL"))
    )
    (comp (ref "C282")
      (value "姨0J332M-RBJ21")
      (footprint "PTH_CAPPR500-1300X2250")
      (libsource (lib "EPIQ_DND_CIS_Library") (part "C_POL"))
    )
    (comp (ref "C283")
      (value "22uF/6.3V")
      (footprint "SMD_0805_CAPC2012X145N")
      (description "Capacitor")
      (libsource (lib "*") (part "CAP"))
    )
    (comp (ref "C284")
      (value "22uF/6.3V")
      (footprint "SMD_0805_CAPC2012X145N")
      (description "Capacitor")
      (libsource (lib "*") (part "CAP"))
    )
    (comp (ref "C285")
      (value "22uF/6.3V")
      (footprint "SMD_0805_CAPC2012X145N")
      (description "Capacitor")
      (libsource (lib "*") (part "CAP"))
    )
    (comp (ref "C286")
      (value "22uF/6.3V")
      (footprint "SMD_0805_CAPC2012X145N")
      (description "Capacitor")
      (libsource (lib "*") (part "CAP"))
    )
    (comp (ref "C287")
      (value "22uF/6.3V")
      (footprint "SMD_0805_CAPC2012X145N")
      (description "Capacitor")
      (libsource (lib "*") (part "CAP"))
    )
    (comp (ref "C288")
      (value "22uF/6.3V")
      (footprint "SMD_0805_CAPC2012X145N")
      (description "Capacitor")
      (libsource (lib "*") (part "CAP"))
    )
    (comp (ref "C289")
      (value "22uF/6.3V")
      (footprint "SMD_0805_CAPC2012X145N")
      (description "Capacitor")
      (libsource (lib "*") (part "CAP"))
    )
    (comp (ref "C290")
      (value "22uF/6.3V")
      (footprint "SMD_0805_CAPC2012X145N")
      (description "Capacitor")
      (libsource (lib "*") (part "CAP"))
    )
    (comp (ref "C291")
      (value "22uF/6.3V")
      (footprint "SMD_0805_CAPC2012X145N")
      (description "Capacitor")
      (libsource (lib "*") (part "CAP"))
    )
    (comp (ref "C292")
      (value "22uF/6.3V")
      (footprint "SMD_0805_CAPC2012X145N")
      (description "Capacitor")
      (libsource (lib "*") (part "CAP"))
    )
    (comp (ref "C293")
      (value "22uF/6.3V")
      (footprint "SMD_0805_CAPC2012X145N")
      (description "Capacitor")
      (libsource (lib "*") (part "CAP"))
    )
    (comp (ref "C294")
      (value "22uF/6.3V")
      (footprint "SMD_0805_CAPC2012X145N")
      (description "Capacitor")
      (libsource (lib "*") (part "CAP"))
    )
    (comp (ref "C295")
      (value "22uF/6.3V")
      (footprint "SMD_0805_CAPC2012X145N")
      (description "Capacitor")
      (libsource (lib "*") (part "CAP"))
    )
    (comp (ref "C296")
      (value "22uF/6.3V")
      (footprint "SMD_0805_CAPC2012X145N")
      (description "Capacitor")
      (libsource (lib "*") (part "CAP"))
    )
    (comp (ref "C297")
      (value "22uF/6.3V")
      (footprint "SMD_0805_CAPC2012X145N")
      (description "Capacitor")
      (libsource (lib "*") (part "CAP"))
    )
    (comp (ref "C298")
      (value "22uF/6.3V")
      (footprint "SMD_0805_CAPC2012X145N")
      (description "Capacitor")
      (libsource (lib "*") (part "CAP"))
    )
    (comp (ref "C299")
      (value "22uF/6.3V")
      (footprint "SMD_0805_CAPC2012X145N")
      (description "Capacitor")
      (libsource (lib "*") (part "CAP"))
    )
    (comp (ref "C300")
      (value "22uF/6.3V")
      (footprint "SMD_0805_CAPC2012X145N")
      (description "Capacitor")
      (libsource (lib "*") (part "CAP"))
    )
    (comp (ref "C301")
      (value "22uF/6.3V")
      (footprint "SMD_0805_CAPC2012X145N")
      (description "Capacitor")
      (libsource (lib "*") (part "CAP"))
    )
    (comp (ref "C302")
      (value "22uF/6.3V")
      (footprint "SMD_0805_CAPC2012X145N")
      (description "Capacitor")
      (libsource (lib "*") (part "CAP"))
    )
    (comp (ref "C303")
      (value "22uF/6.3V")
      (footprint "SMD_0805_CAPC2012X145N")
      (description "Capacitor")
      (libsource (lib "*") (part "CAP"))
    )
    (comp (ref "C304")
      (value "22uF/6.3V")
      (footprint "SMD_0805_CAPC2012X145N")
      (description "Capacitor")
      (libsource (lib "*") (part "CAP"))
    )
    (comp (ref "C305")
      (value "22uF/6.3V")
      (footprint "SMD_0805_CAPC2012X145N")
      (description "Capacitor")
      (libsource (lib "*") (part "CAP"))
    )
    (comp (ref "C306")
      (value "22uF/6.3V")
      (footprint "SMD_0805_CAPC2012X145N")
      (description "Capacitor")
      (libsource (lib "*") (part "CAP"))
    )
    (comp (ref "C307")
      (value "姨0J332M-RBJ21")
      (footprint "PTH_CAPPR500-1300X2250")
      (libsource (lib "EPIQ_DND_CIS_Library") (part "C_POL"))
    )
    (comp (ref "C308")
      (value "10uF/16V")
      (footprint "SMD_0805_CAPC2012X145N")
      (description "Capacitor")
      (libsource (lib "*") (part "CAP"))
    )
    (comp (ref "C309")
      (value "姨0J332M-RBJ21")
      (footprint "PTH_CAPPR500-1300X2250")
      (libsource (lib "EPIQ_DND_CIS_Library") (part "C_POL"))
    )
    (comp (ref "C310")
      (value "(OPT) 2.2nF")
      (footprint "SMD_0805_CAPC2012X145N")
      (description "Capacitor")
      (libsource (lib "*") (part "CAP"))
    )
    (comp (ref "C311")
      (value "1uF/16V")
      (footprint "SMD_0805_CAPC2012X145N")
      (description "Capacitor")
      (libsource (lib "*") (part "CAP"))
    )
    (comp (ref "C312")
      (value "100nF/50V")
      (footprint "SMD_0805_CAPC2012X145N")
      (description "Capacitor")
      (libsource (lib "*") (part "CAP"))
    )
    (comp (ref "C313")
      (value "姨0J332M-RBJ21")
      (footprint "PTH_CAPPR500-1300X2250")
      (libsource (lib "EPIQ_DND_CIS_Library") (part "C_POL"))
    )
    (comp (ref "C314")
      (value "22uF/6.3V")
      (footprint "SMD_0805_CAPC2012X145N")
      (description "Capacitor")
      (libsource (lib "*") (part "CAP"))
    )
    (comp (ref "C315")
      (value "22uF/6.3V")
      (footprint "SMD_0805_CAPC2012X145N")
      (description "Capacitor")
      (libsource (lib "*") (part "CAP"))
    )
    (comp (ref "C316")
      (value "22uF/6.3V")
      (footprint "SMD_0805_CAPC2012X145N")
      (description "Capacitor")
      (libsource (lib "*") (part "CAP"))
    )
    (comp (ref "C317")
      (value "22uF/6.3V")
      (footprint "SMD_0805_CAPC2012X145N")
      (description "Capacitor")
      (libsource (lib "*") (part "CAP"))
    )
    (comp (ref "C318")
      (value "22uF/6.3V")
      (footprint "SMD_0805_CAPC2012X145N")
      (description "Capacitor")
      (libsource (lib "*") (part "CAP"))
    )
    (comp (ref "C319")
      (value "22uF/6.3V")
      (footprint "SMD_0805_CAPC2012X145N")
      (description "Capacitor")
      (libsource (lib "*") (part "CAP"))
    )
    (comp (ref "C320")
      (value "22uF/6.3V")
      (footprint "SMD_0805_CAPC2012X145N")
      (description "Capacitor")
      (libsource (lib "*") (part "CAP"))
    )
    (comp (ref "C321")
      (value "22uF/6.3V")
      (footprint "SMD_0805_CAPC2012X145N")
      (description "Capacitor")
      (libsource (lib "*") (part "CAP"))
    )
    (comp (ref "C322")
      (value "22uF/6.3V")
      (footprint "SMD_0805_CAPC2012X145N")
      (description "Capacitor")
      (libsource (lib "*") (part "CAP"))
    )
    (comp (ref "C323")
      (value "22uF/6.3V")
      (footprint "SMD_0805_CAPC2012X145N")
      (description "Capacitor")
      (libsource (lib "*") (part "CAP"))
    )
    (comp (ref "C324")
      (value "22uF/6.3V")
      (footprint "SMD_0805_CAPC2012X145N")
      (description "Capacitor")
      (libsource (lib "*") (part "CAP"))
    )
    (comp (ref "C325")
      (value "1nF")
      (footprint "SMD_0603_CAPC1608X80N")
      (description "Capacitor")
      (libsource (lib "*") (part "CAP"))
    )
    (comp (ref "D1")
      (value "BAT54C")
      (footprint "SMD_SOT23_SOT95P240X120-3N")
      (libsource (lib "EPIQ_DND_CIS_Library") (part "D_DUAL_A1A2CC3"))
    )
    (comp (ref "D2")
      (value "BAT54C")
      (footprint "SMD_SOT23_SOT95P240X120-3N")
      (libsource (lib "EPIQ_DND_CIS_Library") (part "D_DUAL_A1A2CC3"))
    )
    (comp (ref "D3")
      (value "(OPT) BAV56")
      (footprint "SMD_SOT23_SOT95P240X120-3N")
      (libsource (lib "EPIQ_DND_CIS_Library") (part "D_DUAL_A1A2CC3"))
    )
    (comp (ref "D4")
      (value "Red SML210VT ROHM")
      (footprint "SMD_0805_LED2012X100N")
      (libsource (lib "EPIQ_DND_CIS_Library") (part "LED_2"))
    )
    (comp (ref "D5")
      (value "Green 	SML210MT ROHM")
      (footprint "SMD_0805_LED2012X100N")
      (libsource (lib "EPIQ_DND_CIS_Library") (part "LED_2"))
    )
    (comp (ref "D6")
      (value "Yellow SML210YT ROHM")
      (footprint "SMD_0805_LED2012X100N")
      (libsource (lib "EPIQ_DND_CIS_Library") (part "LED_2"))
    )
    (comp (ref "D7")
      (value "Orange 	SML210DT ROHM")
      (footprint "SMD_0805_LED2012X100N")
      (libsource (lib "EPIQ_DND_CIS_Library") (part "LED_2"))
    )
    (comp (ref "J1")
      (value "(OPT) CON PROGRAM")
      (footprint "SIP5 PGM TOP")
      (description "Connector")
      (libsource (lib "Miscellaneous Devices") (part "CON5"))
    )
    (comp (ref "J2")
      (value "CON MOLEX HDD")
      (footprint "MOLEX_PWR_4P - AVALON")
      (libsource (lib "EPIQ_DND_CIS_Library") (part "CON_4PINS"))
    )
    (comp (ref "J3")
      (value "CU04SCM15B0-R0")
      (footprint "SMD_CON-CVILUX-CU04-SCM15B0")
      (libsource (lib "EPIQ_DND_CIS_Library") (part "CON_USB_MINI_1"))
    )
    (comp (ref "J4")
      (value "CON SIP2")
      (footprint "PTH_HDRV02W64P254_1X02")
      (description "Connector")
      (libsource (lib "Miscellaneous Devices") (part "CON2"))
    )
    (comp (ref "J5")
      (value "CON CAN")
      (footprint "PTH_CON_JST-B2PS-VH")
      (description "Connector")
      (libsource (lib "*") (part "CON2"))
    )
    (comp (ref "J6")
      (value "CON FAN")
      (footprint "PTH_CON_PANCON-MPSS100-04D")
      (libsource (lib "EPIQ_DND_CIS_Library") (part "CON_4PINS"))
    )
    (comp (ref "L1")
      (value "SLC1480-201MLD")
      (footprint "SMD_INDM12501250X800A - Coilcraft SLC1480")
      (libsource (lib "EPIQ_DND_CIS_Library") (part "L"))
    )
    (comp (ref "L2")
      (value "SLC1480-201MLD")
      (footprint "SMD_INDM12501250X800A - Coilcraft SLC1480")
      (libsource (lib "EPIQ_DND_CIS_Library") (part "L"))
    )
    (comp (ref "Q1")
      (value "AP1RA03GMT-3")
      (footprint "SMD_SON127P615X520X100-8N")
      (libsource (lib "EPIQ_DND_CIS_Library") (part "MOS_N_D1_S1S2S3G4D5D6D7D8"))
    )
    (comp (ref "Q2")
      (value "AP1RA03GMT-3")
      (footprint "SMD_SON127P615X520X100-8N")
      (libsource (lib "EPIQ_DND_CIS_Library") (part "MOS_N_D1_S1S2S3G4D5D6D7D8"))
    )
    (comp (ref "Q3")
      (value "AP1RA03GMT-3")
      (footprint "SMD_SON127P615X520X100-8N")
      (libsource (lib "EPIQ_DND_CIS_Library") (part "MOS_N_D1_S1S2S3G4D5D6D7D8"))
    )
    (comp (ref "Q4")
      (value "AP1RA03GMT-3")
      (footprint "SMD_SON127P615X520X100-8N")
      (libsource (lib "EPIQ_DND_CIS_Library") (part "MOS_N_D1_S1S2S3G4D5D6D7D8"))
    )
    (comp (ref "Q5")
      (value "AP1RA03GMT-3")
      (footprint "SMD_SON127P615X520X100-8N")
      (libsource (lib "EPIQ_DND_CIS_Library") (part "MOS_N_D1_S1S2S3G4D5D6D7D8"))
    )
    (comp (ref "Q6")
      (value "(OPT)AP1RA03GMT-3")
      (footprint "SMD_SON127P615X520X100-8N")
      (libsource (lib "EPIQ_DND_CIS_Library") (part "MOS_N_D1_S1S2S3G4D5D6D7D8"))
    )
    (comp (ref "R1")
      (value "100K")
      (footprint "SMD_0603_RESC1608X55N")
      (description "Resistor")
      (fields (field (name "PUBLISHER") "Altium Limited"))
      (libsource (lib "Miscellaneous Devices") (part "Res3"))
    )
    (comp (ref "R2")
      (value "100K")
      (footprint "SMD_0603_RESC1608X55N")
      (description "Resistor")
      (fields (field (name "PUBLISHER") "Altium Limited"))
      (libsource (lib "Miscellaneous Devices") (part "Res3"))
    )
    (comp (ref "R3")
      (value "100K")
      (footprint "SMD_0603_RESC1608X55N")
      (description "Resistor")
      (fields (field (name "PUBLISHER") "Altium Limited"))
      (libsource (lib "Miscellaneous Devices") (part "Res3"))
    )
    (comp (ref "R4")
      (value "100K")
      (footprint "SMD_0603_RESC1608X55N")
      (description "Resistor")
      (fields (field (name "PUBLISHER") "Altium Limited"))
      (libsource (lib "Miscellaneous Devices") (part "Res3"))
    )
    (comp (ref "R5")
      (value "100K")
      (footprint "SMD_0603_RESC1608X55N")
      (description "Resistor")
      (fields (field (name "PUBLISHER") "Altium Limited"))
      (libsource (lib "Miscellaneous Devices") (part "Res3"))
    )
    (comp (ref "R6")
      (value "100K")
      (footprint "SMD_0603_RESC1608X55N")
      (description "Resistor")
      (fields (field (name "PUBLISHER") "Altium Limited"))
      (libsource (lib "Miscellaneous Devices") (part "Res3"))
    )
    (comp (ref "R7")
      (value "100K")
      (footprint "SMD_0603_RESC1608X55N")
      (description "Resistor")
      (fields (field (name "PUBLISHER") "Altium Limited"))
      (libsource (lib "Miscellaneous Devices") (part "Res3"))
    )
    (comp (ref "R8")
      (value "100K")
      (footprint "SMD_0603_RESC1608X55N")
      (description "Resistor")
      (fields (field (name "PUBLISHER") "Altium Limited"))
      (libsource (lib "Miscellaneous Devices") (part "Res3"))
    )
    (comp (ref "R9")
      (value "10k")
      (footprint "SMD_0603_RESC1608X55N")
      (description "Resistor")
      (fields (field (name "PUBLISHER") "Altium Limited"))
      (libsource (lib "Miscellaneous Devices") (part "Res3"))
    )
    (comp (ref "R10")
      (value "100K")
      (footprint "SMD_0603_RESC1608X55N")
      (description "Resistor")
      (fields (field (name "PUBLISHER") "Altium Limited"))
      (libsource (lib "Miscellaneous Devices") (part "Res3"))
    )
    (comp (ref "R11")
      (value "100K")
      (footprint "SMD_0603_RESC1608X55N")
      (description "Resistor")
      (fields (field (name "PUBLISHER") "Altium Limited"))
      (libsource (lib "Miscellaneous Devices") (part "Res3"))
    )
    (comp (ref "R12")
      (value "100K")
      (footprint "SMD_0603_RESC1608X55N")
      (description "Resistor")
      (fields (field (name "PUBLISHER") "Altium Limited"))
      (libsource (lib "Miscellaneous Devices") (part "Res3"))
    )
    (comp (ref "R13")
      (value "100K")
      (footprint "SMD_0603_RESC1608X55N")
      (description "Resistor")
      (fields (field (name "PUBLISHER") "Altium Limited"))
      (libsource (lib "Miscellaneous Devices") (part "Res3"))
    )
    (comp (ref "R14")
      (value "100K")
      (footprint "SMD_0603_RESC1608X55N")
      (description "Resistor")
      (fields (field (name "PUBLISHER") "Altium Limited"))
      (libsource (lib "Miscellaneous Devices") (part "Res3"))
    )
    (comp (ref "R15")
      (value "100K")
      (footprint "SMD_0603_RESC1608X55N")
      (description "Resistor")
      (fields (field (name "PUBLISHER") "Altium Limited"))
      (libsource (lib "Miscellaneous Devices") (part "Res3"))
    )
    (comp (ref "R16")
      (value "100K")
      (footprint "SMD_0603_RESC1608X55N")
      (description "Resistor")
      (fields (field (name "PUBLISHER") "Altium Limited"))
      (libsource (lib "Miscellaneous Devices") (part "Res3"))
    )
    (comp (ref "R17")
      (value "100K")
      (footprint "SMD_0603_RESC1608X55N")
      (description "Resistor")
      (fields (field (name "PUBLISHER") "Altium Limited"))
      (libsource (lib "Miscellaneous Devices") (part "Res3"))
    )
    (comp (ref "R18")
      (value "0")
      (footprint "SMD_0603_RESC1608X55N")
      (description "Resistor")
      (fields (field (name "PUBLISHER") "Altium Limited"))
      (libsource (lib "Miscellaneous Devices") (part "Res3"))
    )
    (comp (ref "R19")
      (value "0")
      (footprint "SMD_0603_RESC1608X55N")
      (description "Resistor")
      (fields (field (name "PUBLISHER") "Altium Limited"))
      (libsource (lib "Miscellaneous Devices") (part "Res3"))
    )
    (comp (ref "R20")
      (value "(OPT)0")
      (footprint "SMD_0603_RESC1608X55N")
      (description "Resistor")
      (fields (field (name "PUBLISHER") "Altium Limited"))
      (libsource (lib "Miscellaneous Devices") (part "Res3"))
    )
    (comp (ref "R21")
      (value "(OPT)0")
      (footprint "SMD_0603_RESC1608X55N")
      (description "Resistor")
      (fields (field (name "PUBLISHER") "Altium Limited"))
      (libsource (lib "Miscellaneous Devices") (part "Res3"))
    )
    (comp (ref "R22")
      (value "0")
      (footprint "SMD_0603_RESC1608X55N")
      (description "Resistor")
      (fields (field (name "PUBLISHER") "Altium Limited"))
      (libsource (lib "Miscellaneous Devices") (part "Res3"))
    )
    (comp (ref "R23")
      (value "0")
      (footprint "SMD_0603_RESC1608X55N")
      (description "Resistor")
      (fields (field (name "PUBLISHER") "Altium Limited"))
      (libsource (lib "Miscellaneous Devices") (part "Res3"))
    )
    (comp (ref "R24")
      (value "0")
      (footprint "SMD_0603_RESC1608X55N")
      (description "Resistor")
      (fields (field (name "PUBLISHER") "Altium Limited"))
      (libsource (lib "Miscellaneous Devices") (part "Res3"))
    )
    (comp (ref "R25")
      (value "0")
      (footprint "SMD_0603_RESC1608X55N")
      (description "Resistor")
      (fields (field (name "PUBLISHER") "Altium Limited"))
      (libsource (lib "Miscellaneous Devices") (part "Res3"))
    )
    (comp (ref "R26")
      (value "0")
      (footprint "SMD_0603_RESC1608X55N")
      (description "Resistor")
      (fields (field (name "PUBLISHER") "Altium Limited"))
      (libsource (lib "Miscellaneous Devices") (part "Res3"))
    )
    (comp (ref "R27")
      (value "0")
      (footprint "SMD_0603_RESC1608X55N")
      (description "Resistor")
      (fields (field (name "PUBLISHER") "Altium Limited"))
      (libsource (lib "Miscellaneous Devices") (part "Res3"))
    )
    (comp (ref "R28")
      (value "(OPT)0")
      (footprint "SMD_0603_RESC1608X55N")
      (description "Resistor")
      (fields (field (name "PUBLISHER") "Altium Limited"))
      (libsource (lib "Miscellaneous Devices") (part "Res3"))
    )
    (comp (ref "R29")
      (value "(OPT)0")
      (footprint "SMD_0603_RESC1608X55N")
      (description "Resistor")
      (fields (field (name "PUBLISHER") "Altium Limited"))
      (libsource (lib "Miscellaneous Devices") (part "Res3"))
    )
    (comp (ref "R30")
      (value "(OPT)0")
      (footprint "SMD_0603_RESC1608X55N")
      (description "Resistor")
      (fields (field (name "PUBLISHER") "Altium Limited"))
      (libsource (lib "Miscellaneous Devices") (part "Res3"))
    )
    (comp (ref "R31")
      (value "(OPT)0")
      (footprint "SMD_0603_RESC1608X55N")
      (description "Resistor")
      (fields (field (name "PUBLISHER") "Altium Limited"))
      (libsource (lib "Miscellaneous Devices") (part "Res3"))
    )
    (comp (ref "R32")
      (value "(OPT)0")
      (footprint "SMD_0603_RESC1608X55N")
      (description "Resistor")
      (fields (field (name "PUBLISHER") "Altium Limited"))
      (libsource (lib "Miscellaneous Devices") (part "Res3"))
    )
    (comp (ref "R33")
      (value "(OPT) 3.01")
      (footprint "SMD_1206_RESC3216X180N")
      (description "Resistor")
      (fields (field (name "PUBLISHER") "Altium Limited"))
      (libsource (lib "Miscellaneous Devices") (part "Res3"))
    )
    (comp (ref "R34")
      (value "27")
      (footprint "SMD_0603_RESC1608X55N")
      (description "Resistor")
      (fields (field (name "PUBLISHER") "Altium Limited"))
      (libsource (lib "Miscellaneous Devices") (part "Res3"))
    )
    (comp (ref "R35")
      (value "27")
      (footprint "SMD_0603_RESC1608X55N")
      (description "Resistor")
      (fields (field (name "PUBLISHER") "Altium Limited"))
      (libsource (lib "Miscellaneous Devices") (part "Res3"))
    )
    (comp (ref "R36")
      (value "768")
      (footprint "SMD_0603_RESC1608X55N")
      (description "Resistor")
      (fields (field (name "PUBLISHER") "Altium Limited"))
      (libsource (lib "Miscellaneous Devices") (part "Res3"))
    )
    (comp (ref "R37")
      (value "2.4k")
      (footprint "SMD_0603_RESC1608X55N")
      (description "Resistor")
      (fields (field (name "PUBLISHER") "Altium Limited"))
      (libsource (lib "Miscellaneous Devices") (part "Res3"))
    )
    (comp (ref "R38")
      (value "2.4k")
      (footprint "SMD_0603_RESC1608X55N")
      (description "Resistor")
      (fields (field (name "PUBLISHER") "Altium Limited"))
      (libsource (lib "Miscellaneous Devices") (part "Res3"))
    )
    (comp (ref "R40")
      (value "10k")
      (footprint "SMD_0603_RESC1608X55N")
      (description "Resistor")
      (fields (field (name "PUBLISHER") "Altium Limited"))
      (libsource (lib "Miscellaneous Devices") (part "Res3"))
    )
    (comp (ref "R41")
      (value "120")
      (footprint "SMD_0603_RESC1608X55N")
      (description "Resistor")
      (fields (field (name "PUBLISHER") "Altium Limited"))
      (libsource (lib "Miscellaneous Devices") (part "Res3"))
    )
    (comp (ref "R42")
      (value "(OPT)0")
      (footprint "SMD_0603_RESC1608X55N")
      (description "Resistor")
      (fields (field (name "PUBLISHER") "Altium Limited"))
      (libsource (lib "Miscellaneous Devices") (part "Res3"))
    )
    (comp (ref "R43")
      (value "10k")
      (footprint "SMD_0603_RESC1608X55N")
      (description "Resistor")
      (fields (field (name "PUBLISHER") "Altium Limited"))
      (libsource (lib "Miscellaneous Devices") (part "Res3"))
    )
    (comp (ref "R44")
      (value "10k")
      (footprint "SMD_0603_RESC1608X55N")
      (description "Resistor")
      (fields (field (name "PUBLISHER") "Altium Limited"))
      (libsource (lib "Miscellaneous Devices") (part "Res3"))
    )
    (comp (ref "R45")
      (value "2.4k")
      (footprint "SMD_0603_RESC1608X55N")
      (description "Resistor")
      (fields (field (name "PUBLISHER") "Altium Limited"))
      (libsource (lib "Miscellaneous Devices") (part "Res3"))
    )
    (comp (ref "R46")
      (value "0")
      (footprint "SMD_1206_RESC3216X180N")
      (description "Resistor")
      (fields (field (name "PUBLISHER") "Altium Limited"))
      (libsource (lib "Miscellaneous Devices") (part "Res3"))
    )
    (comp (ref "R47")
      (value "0")
      (footprint "SMD_1206_RESC3216X180N")
      (description "Resistor")
      (fields (field (name "PUBLISHER") "Altium Limited"))
      (libsource (lib "Miscellaneous Devices") (part "Res3"))
    )
    (comp (ref "R48")
      (value "(OPT)470")
      (footprint "SMD_0603_RESC1608X55N")
      (description "Resistor")
      (fields (field (name "PUBLISHER") "Altium Limited"))
      (libsource (lib "Miscellaneous Devices") (part "Res3"))
    )
    (comp (ref "R49")
      (value "(OPT)470")
      (footprint "SMD_0603_RESC1608X55N")
      (description "Resistor")
      (fields (field (name "PUBLISHER") "Altium Limited"))
      (libsource (lib "Miscellaneous Devices") (part "Res3"))
    )
    (comp (ref "R50")
      (value "470")
      (footprint "SMD_0603_RESC1608X55N")
      (description "Resistor")
      (fields (field (name "PUBLISHER") "Altium Limited"))
      (libsource (lib "Miscellaneous Devices") (part "Res3"))
    )
    (comp (ref "R51")
      (value "470")
      (footprint "SMD_0603_RESC1608X55N")
      (description "Resistor")
      (fields (field (name "PUBLISHER") "Altium Limited"))
      (libsource (lib "Miscellaneous Devices") (part "Res3"))
    )
    (comp (ref "R52")
      (value "(OPT)470")
      (footprint "SMD_0603_RESC1608X55N")
      (description "Resistor")
      (fields (field (name "PUBLISHER") "Altium Limited"))
      (libsource (lib "Miscellaneous Devices") (part "Res3"))
    )
    (comp (ref "R53")
      (value "(OPT)470")
      (footprint "SMD_0603_RESC1608X55N")
      (description "Resistor")
      (fields (field (name "PUBLISHER") "Altium Limited"))
      (libsource (lib "Miscellaneous Devices") (part "Res3"))
    )
    (comp (ref "R54")
      (value "(OPT)470")
      (footprint "SMD_0603_RESC1608X55N")
      (description "Resistor")
      (fields (field (name "PUBLISHER") "Altium Limited"))
      (libsource (lib "Miscellaneous Devices") (part "Res3"))
    )
    (comp (ref "R55")
      (value "(OPT)470")
      (footprint "SMD_0603_RESC1608X55N")
      (description "Resistor")
      (fields (field (name "PUBLISHER") "Altium Limited"))
      (libsource (lib "Miscellaneous Devices") (part "Res3"))
    )
    (comp (ref "R56")
      (value "0")
      (footprint "SMD_0603_RESC1608X55N")
      (description "Resistor")
      (fields (field (name "PUBLISHER") "Altium Limited"))
      (libsource (lib "Miscellaneous Devices") (part "Res3"))
    )
    (comp (ref "R57")
      (value "10k")
      (footprint "SMD_0603_RESC1608X55N")
      (description "Resistor")
      (fields (field (name "PUBLISHER") "Altium Limited"))
      (libsource (lib "Miscellaneous Devices") (part "Res3"))
    )
    (comp (ref "R59")
      (value "10k")
      (footprint "SMD_0603_RESC1608X55N")
      (description "Resistor")
      (fields (field (name "PUBLISHER") "Altium Limited"))
      (libsource (lib "Miscellaneous Devices") (part "Res3"))
    )
    (comp (ref "R60")
      (value "0")
      (footprint "SMD_1206_RESC3216X180N")
      (description "Resistor")
      (fields (field (name "PUBLISHER") "Altium Limited"))
      (libsource (lib "Miscellaneous Devices") (part "Res3"))
    )
    (comp (ref "R61")
      (value "2.4k")
      (footprint "SMD_0603_RESC1608X55N")
      (description "Resistor")
      (fields (field (name "PUBLISHER") "Altium Limited"))
      (libsource (lib "Miscellaneous Devices") (part "Res3"))
    )
    (comp (ref "R62")
      (value "(OPT)0")
      (footprint "SMD_0603_RESC1608X55N")
      (description "Resistor")
      (fields (field (name "PUBLISHER") "Altium Limited"))
      (libsource (lib "Miscellaneous Devices") (part "Res3"))
    )
    (comp (ref "R63")
      (value "0")
      (footprint "SMD_0603_RESC1608X55N")
      (description "Resistor")
      (fields (field (name "PUBLISHER") "Altium Limited"))
      (libsource (lib "Miscellaneous Devices") (part "Res3"))
    )
    (comp (ref "R64")
      (value "0")
      (footprint "SMD_0603_RESC1608X55N")
      (description "Resistor")
      (fields (field (name "PUBLISHER") "Altium Limited"))
      (libsource (lib "Miscellaneous Devices") (part "Res3"))
    )
    (comp (ref "R67")
      (value "(OPT) 3.01")
      (footprint "SMD_1206_RESC3216X180N")
      (description "Resistor")
      (fields (field (name "PUBLISHER") "Altium Limited"))
      (libsource (lib "Miscellaneous Devices") (part "Res3"))
    )
    (comp (ref "U1")
      (value "dsPIC33EP256MU806")
      (footprint "SMD_QFP50P1200X1200X120-64N")
      (libsource (lib "MCU") (part "dsPIC33EP256MU806"))
    )
    (comp (ref "U2")
      (value "A3256Q48")
      (footprint "SMD_QFN50P700X700X90-49N")
      (description "Avalon SHA256")
      (libsource (lib "DevicesA10") (part "A3256Q48"))
    )
    (comp (ref "U3")
      (value "A3256Q48")
      (footprint "SMD_QFN50P700X700X90-49N")
      (description "Avalon SHA256")
      (libsource (lib "DevicesA10") (part "A3256Q48"))
    )
    (comp (ref "U4")
      (value "A3256Q48")
      (footprint "SMD_QFN50P700X700X90-49N")
      (description "Avalon SHA256")
      (libsource (lib "DevicesA10") (part "A3256Q48"))
    )
    (comp (ref "U5")
      (value "A3256Q48")
      (footprint "SMD_QFN50P700X700X90-49N")
      (description "Avalon SHA256")
      (libsource (lib "DevicesA10") (part "A3256Q48"))
    )
    (comp (ref "U6")
      (value "(OPT)BU33TD3WG-TR")
      (footprint "SMD_SOT26_SOT95P285X140-5N - DLV")
      (libsource (lib "Miscellaneous Devices") (part "VOLTREG LDO"))
    )
    (comp (ref "U7")
      (value "A3256Q48")
      (footprint "SMD_QFN50P700X700X90-49N")
      (description "Avalon SHA256")
      (libsource (lib "DevicesA10") (part "A3256Q48"))
    )
    (comp (ref "U8")
      (value "A3256Q48")
      (footprint "SMD_QFN50P700X700X90-49N")
      (description "Avalon SHA256")
      (libsource (lib "DevicesA10") (part "A3256Q48"))
    )
    (comp (ref "U9")
      (value "A3256Q48")
      (footprint "SMD_QFN50P700X700X90-49N")
      (description "Avalon SHA256")
      (libsource (lib "DevicesA10") (part "A3256Q48"))
    )
    (comp (ref "U10")
      (value "A3256Q48")
      (footprint "SMD_QFN50P700X700X90-49N")
      (description "Avalon SHA256")
      (libsource (lib "DevicesA10") (part "A3256Q48"))
    )
    (comp (ref "U11")
      (value "A3256Q48")
      (footprint "SMD_QFN50P700X700X90-49N")
      (description "Avalon SHA256")
      (libsource (lib "DevicesA10") (part "A3256Q48"))
    )
    (comp (ref "U12")
      (value "A3256Q48")
      (footprint "SMD_QFN50P700X700X90-49N")
      (description "Avalon SHA256")
      (libsource (lib "DevicesA10") (part "A3256Q48"))
    )
    (comp (ref "U13")
      (value "A3256Q48")
      (footprint "SMD_QFN50P700X700X90-49N")
      (description "Avalon SHA256")
      (libsource (lib "DevicesA10") (part "A3256Q48"))
    )
    (comp (ref "U14")
      (value "A3256Q48")
      (footprint "SMD_QFN50P700X700X90-49N")
      (description "Avalon SHA256")
      (libsource (lib "DevicesA10") (part "A3256Q48"))
    )
    (comp (ref "U15")
      (value "A3256Q48")
      (footprint "SMD_QFN50P700X700X90-49N")
      (description "Avalon SHA256")
      (libsource (lib "DevicesA10") (part "A3256Q48"))
    )
    (comp (ref "U16")
      (value "A3256Q48")
      (footprint "SMD_QFN50P700X700X90-49N")
      (description "Avalon SHA256")
      (libsource (lib "DevicesA10") (part "A3256Q48"))
    )
    (comp (ref "U17")
      (value "A3256Q48")
      (footprint "SMD_QFN50P700X700X90-49N")
      (description "Avalon SHA256")
      (libsource (lib "DevicesA10") (part "A3256Q48"))
    )
    (comp (ref "U18")
      (value "A3256Q48")
      (footprint "SMD_QFN50P700X700X90-49N")
      (description "Avalon SHA256")
      (libsource (lib "DevicesA10") (part "A3256Q48"))
    )
    (comp (ref "U19")
      (value "BD33KA5WF")
      (footprint "SMD_SOIC127P602X173-8N")
      (libsource (lib "EPIQ_DND_CIS_Library") (part "IC_LM2931AD-5.0R2G_SO-8"))
    )
    (comp (ref "U20")
      (value "L78M05CDT-TR")
      (footprint "SMD_TO229P991X239-4AN_DPAK")
      (libsource (lib "EPIQ_DND_CIS_Library") (part "IC_Vout1GND2Vin3"))
    )
    (comp (ref "U21")
      (value "MCP2551-I/SN")
      (footprint "SMD_SOIC127P602X173-8N")
      (description "CAN Driver")
      (libsource (lib "Devices") (part "MCP2551"))
    )
    (comp (ref "U22")
      (value "(OPT) LM7805")
      (footprint "SMD_SOIC127P602X173-8N")
      (libsource (lib "EPIQ_DND_CIS_Library") (part "IC_LM2931AD-5.0R2G_SO-8"))
    )
    (comp (ref "U23")
      (value "(OPT) L7805CD2T-TR")
      (footprint "SMD_TO254P1524X483-3_4N_D2PAK + DPAK")
      (libsource (lib "EPIQ_DND_CIS_Library") (part "IC_Vout1GND2Vin3"))
    )
    (comp (ref "U25")
      (value "LTC 4449")
      (footprint "SMD_SOP65P490X110-9N - DUAL")
      (description "Mosfet 12V Dual Bootstrapped PWM Sync Buck Optimised")
      (libsource (lib "Devices") (part "DRVFET_LTC4442"))
    )
    (comp (ref "U30")
      (value "LTC 4449")
      (footprint "SMD_SOP65P490X110-9N - DUAL")
      (description "Mosfet 12V Dual Bootstrapped PWM Sync Buck Optimised")
      (libsource (lib "Devices") (part "DRVFET_LTC4442"))
    )
    (comp (ref "Y1")
      (value "Q4.000 MHz HC-49SM SMD")
      (footprint "SMD_HC49_XTAL1140X480X420N")
      (description "Crystal")
      (libsource (lib "*") (part "CRYSTAL"))
    )
  )
  (nets
    (net (code "1") (name "/1.2V") (class "Default")
      (node (ref "C10") (pin "1") (pinfunction "1_1") (pintype "passive"))
      (node (ref "C103") (pin "1") (pinfunction "1_1") (pintype "passive"))
      (node (ref "C104") (pin "1") (pinfunction "1_1") (pintype "passive"))
      (node (ref "C105") (pin "1") (pinfunction "1_1") (pintype "passive"))
      (node (ref "C106") (pin "1") (pinfunction "1_1") (pintype "passive"))
      (node (ref "C107") (pin "1") (pinfunction "1_1") (pintype "passive"))
      (node (ref "C108") (pin "1") (pinfunction "1_1") (pintype "passive"))
      (node (ref "C109") (pin "1") (pinfunction "1_1") (pintype "passive"))
      (node (ref "C11") (pin "1") (pinfunction "1_1") (pintype "passive"))
      (node (ref "C110") (pin "1") (pinfunction "1_1") (pintype "passive"))
      (node (ref "C115") (pin "1") (pinfunction "1_1") (pintype "passive"))
      (node (ref "C116") (pin "1") (pinfunction "1_1") (pintype "passive"))
      (node (ref "C117") (pin "1") (pinfunction "1_1") (pintype "passive"))
      (node (ref "C118") (pin "1") (pinfunction "1_1") (pintype "passive"))
      (node (ref "C119") (pin "1") (pinfunction "1_1") (pintype "passive"))
      (node (ref "C12") (pin "1") (pinfunction "1_1") (pintype "passive"))
      (node (ref "C120") (pin "1") (pinfunction "1_1") (pintype "passive"))
      (node (ref "C121") (pin "1") (pinfunction "1_1") (pintype "passive"))
      (node (ref "C122") (pin "1") (pinfunction "1_1") (pintype "passive"))
      (node (ref "C123") (pin "1") (pinfunction "1_1") (pintype "passive"))
      (node (ref "C124") (pin "1") (pinfunction "1_1") (pintype "passive"))
      (node (ref "C125") (pin "1") (pinfunction "1_1") (pintype "passive"))
      (node (ref "C126") (pin "1") (pinfunction "1_1") (pintype "passive"))
      (node (ref "C127") (pin "1") (pinfunction "1_1") (pintype "passive"))
      (node (ref "C128") (pin "1") (pinfunction "1_1") (pintype "passive"))
      (node (ref "C129") (pin "1") (pinfunction "1_1") (pintype "passive"))
      (node (ref "C130") (pin "1") (pinfunction "1_1") (pintype "passive"))
      (node (ref "C131") (pin "1") (pinfunction "1_1") (pintype "passive"))
      (node (ref "C132") (pin "1") (pinfunction "1_1") (pintype "passive"))
      (node (ref "C134") (pin "1") (pinfunction "1_1") (pintype "passive"))
      (node (ref "C135") (pin "1") (pinfunction "1_1") (pintype "passive"))
      (node (ref "C137") (pin "1") (pinfunction "1_1") (pintype "passive"))
      (node (ref "C138") (pin "1") (pinfunction "1_1") (pintype "passive"))
      (node (ref "C140") (pin "1") (pinfunction "1_1") (pintype "passive"))
      (node (ref "C141") (pin "1") (pinfunction "1_1") (pintype "passive"))
      (node (ref "C147") (pin "1") (pinfunction "1_1") (pintype "passive"))
      (node (ref "C148") (pin "1") (pinfunction "1_1") (pintype "passive"))
      (node (ref "C149") (pin "1") (pinfunction "1_1") (pintype "passive"))
      (node (ref "C150") (pin "1") (pinfunction "1_1") (pintype "passive"))
      (node (ref "C151") (pin "1") (pinfunction "1_1") (pintype "passive"))
      (node (ref "C152") (pin "1") (pinfunction "1_1") (pintype "passive"))
      (node (ref "C153") (pin "1") (pinfunction "1_1") (pintype "passive"))
      (node (ref "C154") (pin "1") (pinfunction "1_1") (pintype "passive"))
      (node (ref "C159") (pin "1") (pinfunction "1_1") (pintype "passive"))
      (node (ref "C160") (pin "1") (pinfunction "1_1") (pintype "passive"))
      (node (ref "C161") (pin "1") (pinfunction "1_1") (pintype "passive"))
      (node (ref "C162") (pin "1") (pinfunction "1_1") (pintype "passive"))
      (node (ref "C163") (pin "1") (pinfunction "1_1") (pintype "passive"))
      (node (ref "C164") (pin "1") (pinfunction "1_1") (pintype "passive"))
      (node (ref "C165") (pin "1") (pinfunction "1_1") (pintype "passive"))
      (node (ref "C166") (pin "1") (pinfunction "1_1") (pintype "passive"))
      (node (ref "C167") (pin "1") (pinfunction "1_1") (pintype "passive"))
      (node (ref "C168") (pin "1") (pinfunction "1_1") (pintype "passive"))
      (node (ref "C169") (pin "1") (pinfunction "1_1") (pintype "passive"))
      (node (ref "C170") (pin "1") (pinfunction "1_1") (pintype "passive"))
      (node (ref "C171") (pin "1") (pinfunction "1_1") (pintype "passive"))
      (node (ref "C172") (pin "1") (pinfunction "1_1") (pintype "passive"))
      (node (ref "C173") (pin "1") (pinfunction "1_1") (pintype "passive"))
      (node (ref "C174") (pin "1") (pinfunction "1_1") (pintype "passive"))
      (node (ref "C175") (pin "1") (pinfunction "1_1") (pintype "passive"))
      (node (ref "C176") (pin "1") (pinfunction "1_1") (pintype "passive"))
      (node (ref "C178") (pin "1") (pinfunction "1_1") (pintype "passive"))
      (node (ref "C179") (pin "1") (pinfunction "1_1") (pintype "passive"))
      (node (ref "C18") (pin "1") (pinfunction "1_1") (pintype "passive"))
      (node (ref "C181") (pin "1") (pinfunction "1_1") (pintype "passive"))
      (node (ref "C182") (pin "1") (pinfunction "1_1") (pintype "passive"))
      (node (ref "C184") (pin "1") (pinfunction "1_1") (pintype "passive"))
      (node (ref "C185") (pin "1") (pinfunction "1_1") (pintype "passive"))
      (node (ref "C19") (pin "1") (pinfunction "1_1") (pintype "passive"))
      (node (ref "C198") (pin "1") (pinfunction "1_1") (pintype "passive"))
      (node (ref "C199") (pin "1") (pinfunction "1_1") (pintype "passive"))
      (node (ref "C20") (pin "1") (pinfunction "1_1") (pintype "passive"))
      (node (ref "C200") (pin "1") (pinfunction "1_1") (pintype "passive"))
      (node (ref "C201") (pin "1") (pinfunction "1_1") (pintype "passive"))
      (node (ref "C202") (pin "1") (pinfunction "1_1") (pintype "passive"))
      (node (ref "C203") (pin "1") (pinfunction "1_1") (pintype "passive"))
      (node (ref "C204") (pin "1") (pinfunction "1_1") (pintype "passive"))
      (node (ref "C205") (pin "1") (pinfunction "1_1") (pintype "passive"))
      (node (ref "C209") (pin "2") (pinfunction "2_2") (pintype "passive"))
      (node (ref "C21") (pin "1") (pinfunction "1_1") (pintype "passive"))
      (node (ref "C212") (pin "1") (pinfunction "1_1") (pintype "passive"))
      (node (ref "C22") (pin "1") (pinfunction "1_1") (pintype "passive"))
      (node (ref "C220") (pin "1") (pinfunction "1_1") (pintype "passive"))
      (node (ref "C221") (pin "1") (pinfunction "1_1") (pintype "passive"))
      (node (ref "C222") (pin "1") (pinfunction "1_1") (pintype "passive"))
      (node (ref "C223") (pin "1") (pinfunction "1_1") (pintype "passive"))
      (node (ref "C224") (pin "1") (pinfunction "1_1") (pintype "passive"))
      (node (ref "C225") (pin "1") (pinfunction "1_1") (pintype "passive"))
      (node (ref "C226") (pin "1") (pinfunction "1_1") (pintype "passive"))
      (node (ref "C227") (pin "1") (pinfunction "1_1") (pintype "passive"))
      (node (ref "C228") (pin "1") (pinfunction "1_1") (pintype "passive"))
      (node (ref "C23") (pin "1") (pinfunction "1_1") (pintype "passive"))
      (node (ref "C232") (pin "1") (pinfunction "1_1") (pintype "passive"))
      (node (ref "C238") (pin "1") (pinfunction "1_1") (pintype "passive"))
      (node (ref "C239") (pin "1") (pinfunction "1_1") (pintype "passive"))
      (node (ref "C24") (pin "1") (pinfunction "1_1") (pintype "passive"))
      (node (ref "C240") (pin "1") (pinfunction "1_1") (pintype "passive"))
      (node (ref "C241") (pin "1") (pinfunction "1_1") (pintype "passive"))
      (node (ref "C242") (pin "1") (pinfunction "1_1") (pintype "passive"))
      (node (ref "C243") (pin "1") (pinfunction "1_1") (pintype "passive"))
      (node (ref "C244") (pin "1") (pinfunction "1_1") (pintype "passive"))
      (node (ref "C245") (pin "1") (pinfunction "1_1") (pintype "passive"))
      (node (ref "C246") (pin "1") (pinfunction "1_1") (pintype "passive"))
      (node (ref "C247") (pin "1") (pinfunction "1_1") (pintype "passive"))
      (node (ref "C25") (pin "1") (pinfunction "1_1") (pintype "passive"))
      (node (ref "C256") (pin "1") (pinfunction "1_1") (pintype "passive"))
      (node (ref "C257") (pin "1") (pinfunction "1_1") (pintype "passive"))
      (node (ref "C258") (pin "1") (pinfunction "1_1") (pintype "passive"))
      (node (ref "C259") (pin "1") (pinfunction "1_1") (pintype "passive"))
      (node (ref "C26") (pin "1") (pinfunction "1_1") (pintype "passive"))
      (node (ref "C260") (pin "1") (pinfunction "1_1") (pintype "passive"))
      (node (ref "C261") (pin "1") (pinfunction "1_1") (pintype "passive"))
      (node (ref "C262") (pin "1") (pinfunction "1_1") (pintype "passive"))
      (node (ref "C27") (pin "1") (pinfunction "1_1") (pintype "passive"))
      (node (ref "C271") (pin "1") (pinfunction "1_1") (pintype "passive"))
      (node (ref "C28") (pin "1") (pinfunction "1_1") (pintype "passive"))
      (node (ref "C282") (pin "1") (pinfunction "1_1") (pintype "passive"))
      (node (ref "C283") (pin "1") (pinfunction "1_1") (pintype "passive"))
      (node (ref "C284") (pin "1") (pinfunction "1_1") (pintype "passive"))
      (node (ref "C285") (pin "1") (pinfunction "1_1") (pintype "passive"))
      (node (ref "C286") (pin "1") (pinfunction "1_1") (pintype "passive"))
      (node (ref "C287") (pin "1") (pinfunction "1_1") (pintype "passive"))
      (node (ref "C288") (pin "1") (pinfunction "1_1") (pintype "passive"))
      (node (ref "C289") (pin "1") (pinfunction "1_1") (pintype "passive"))
      (node (ref "C29") (pin "1") (pinfunction "1_1") (pintype "passive"))
      (node (ref "C290") (pin "1") (pinfunction "1_1") (pintype "passive"))
      (node (ref "C291") (pin "1") (pinfunction "1_1") (pintype "passive"))
      (node (ref "C292") (pin "1") (pinfunction "1_1") (pintype "passive"))
      (node (ref "C293") (pin "1") (pinfunction "1_1") (pintype "passive"))
      (node (ref "C294") (pin "1") (pinfunction "1_1") (pintype "passive"))
      (node (ref "C295") (pin "1") (pinfunction "1_1") (pintype "passive"))
      (node (ref "C296") (pin "1") (pinfunction "1_1") (pintype "passive"))
      (node (ref "C297") (pin "1") (pinfunction "1_1") (pintype "passive"))
      (node (ref "C298") (pin "1") (pinfunction "1_1") (pintype "passive"))
      (node (ref "C299") (pin "1") (pinfunction "1_1") (pintype "passive"))
      (node (ref "C30") (pin "1") (pinfunction "1_1") (pintype "passive"))
      (node (ref "C300") (pin "1") (pinfunction "1_1") (pintype "passive"))
      (node (ref "C301") (pin "1") (pinfunction "1_1") (pintype "passive"))
      (node (ref "C302") (pin "1") (pinfunction "1_1") (pintype "passive"))
      (node (ref "C303") (pin "1") (pinfunction "1_1") (pintype "passive"))
      (node (ref "C304") (pin "1") (pinfunction "1_1") (pintype "passive"))
      (node (ref "C305") (pin "1") (pinfunction "1_1") (pintype "passive"))
      (node (ref "C306") (pin "1") (pinfunction "1_1") (pintype "passive"))
      (node (ref "C307") (pin "1") (pinfunction "1_1") (pintype "passive"))
      (node (ref "C309") (pin "1") (pinfunction "1_1") (pintype "passive"))
      (node (ref "C31") (pin "1") (pinfunction "1_1") (pintype "passive"))
      (node (ref "C313") (pin "1") (pinfunction "1_1") (pintype "passive"))
      (node (ref "C314") (pin "1") (pinfunction "1_1") (pintype "passive"))
      (node (ref "C315") (pin "1") (pinfunction "1_1") (pintype "passive"))
      (node (ref "C316") (pin "1") (pinfunction "1_1") (pintype "passive"))
      (node (ref "C317") (pin "1") (pinfunction "1_1") (pintype "passive"))
      (node (ref "C318") (pin "1") (pinfunction "1_1") (pintype "passive"))
      (node (ref "C319") (pin "1") (pinfunction "1_1") (pintype "passive"))
      (node (ref "C32") (pin "1") (pinfunction "1_1") (pintype "passive"))
      (node (ref "C320") (pin "1") (pinfunction "1_1") (pintype "passive"))
      (node (ref "C321") (pin "1") (pinfunction "1_1") (pintype "passive"))
      (node (ref "C322") (pin "1") (pinfunction "1_1") (pintype "passive"))
      (node (ref "C323") (pin "1") (pinfunction "1_1") (pintype "passive"))
      (node (ref "C324") (pin "1") (pinfunction "1_1") (pintype "passive"))
      (node (ref "C33") (pin "1") (pinfunction "1_1") (pintype "passive"))
      (node (ref "C35") (pin "1") (pinfunction "1_1") (pintype "passive"))
      (node (ref "C36") (pin "1") (pinfunction "1_1") (pintype "passive"))
      (node (ref "C38") (pin "1") (pinfunction "1_1") (pintype "passive"))
      (node (ref "C39") (pin "1") (pinfunction "1_1") (pintype "passive"))
      (node (ref "C41") (pin "1") (pinfunction "1_1") (pintype "passive"))
      (node (ref "C42") (pin "1") (pinfunction "1_1") (pintype "passive"))
      (node (ref "C44") (pin "1") (pinfunction "1_1") (pintype "passive"))
      (node (ref "C45") (pin "1") (pinfunction "1_1") (pintype "passive"))
      (node (ref "C5") (pin "1") (pinfunction "1_1") (pintype "passive"))
      (node (ref "C51") (pin "1") (pinfunction "1_1") (pintype "passive"))
      (node (ref "C52") (pin "1") (pinfunction "1_1") (pintype "passive"))
      (node (ref "C53") (pin "1") (pinfunction "1_1") (pintype "passive"))
      (node (ref "C54") (pin "1") (pinfunction "1_1") (pintype "passive"))
      (node (ref "C55") (pin "1") (pinfunction "1_1") (pintype "passive"))
      (node (ref "C56") (pin "1") (pinfunction "1_1") (pintype "passive"))
      (node (ref "C57") (pin "1") (pinfunction "1_1") (pintype "passive"))
      (node (ref "C58") (pin "1") (pinfunction "1_1") (pintype "passive"))
      (node (ref "C6") (pin "1") (pinfunction "1_1") (pintype "passive"))
      (node (ref "C64") (pin "1") (pinfunction "1_1") (pintype "passive"))
      (node (ref "C65") (pin "1") (pinfunction "1_1") (pintype "passive"))
      (node (ref "C66") (pin "1") (pinfunction "1_1") (pintype "passive"))
      (node (ref "C67") (pin "1") (pinfunction "1_1") (pintype "passive"))
      (node (ref "C68") (pin "1") (pinfunction "1_1") (pintype "passive"))
      (node (ref "C69") (pin "1") (pinfunction "1_1") (pintype "passive"))
      (node (ref "C7") (pin "1") (pinfunction "1_1") (pintype "passive"))
      (node (ref "C70") (pin "1") (pinfunction "1_1") (pintype "passive"))
      (node (ref "C71") (pin "1") (pinfunction "1_1") (pintype "passive"))
      (node (ref "C77") (pin "1") (pinfunction "1_1") (pintype "passive"))
      (node (ref "C78") (pin "1") (pinfunction "1_1") (pintype "passive"))
      (node (ref "C79") (pin "1") (pinfunction "1_1") (pintype "passive"))
      (node (ref "C8") (pin "1") (pinfunction "1_1") (pintype "passive"))
      (node (ref "C80") (pin "1") (pinfunction "1_1") (pintype "passive"))
      (node (ref "C81") (pin "1") (pinfunction "1_1") (pintype "passive"))
      (node (ref "C82") (pin "1") (pinfunction "1_1") (pintype "passive"))
      (node (ref "C83") (pin "1") (pinfunction "1_1") (pintype "passive"))
      (node (ref "C84") (pin "1") (pinfunction "1_1") (pintype "passive"))
      (node (ref "C87") (pin "1") (pinfunction "1_1") (pintype "passive"))
      (node (ref "C88") (pin "1") (pinfunction "1_1") (pintype "passive"))
      (node (ref "C9") (pin "1") (pinfunction "1_1") (pintype "passive"))
      (node (ref "C90") (pin "1") (pinfunction "1_1") (pintype "passive"))
      (node (ref "C91") (pin "1") (pinfunction "1_1") (pintype "passive"))
      (node (ref "C93") (pin "1") (pinfunction "1_1") (pintype "passive"))
      (node (ref "C94") (pin "1") (pinfunction "1_1") (pintype "passive"))
      (node (ref "C96") (pin "1") (pinfunction "1_1") (pintype "passive"))
      (node (ref "C97") (pin "1") (pinfunction "1_1") (pintype "passive"))
      (node (ref "L1") (pin "2") (pinfunction "2_2") (pintype "passive"))
      (node (ref "L2") (pin "2") (pinfunction "2_2") (pintype "passive"))
      (node (ref "R38") (pin "2") (pinfunction "2_2") (pintype "passive"))
      (node (ref "R43") (pin "2") (pinfunction "2_2") (pintype "passive"))
      (node (ref "U10") (pin "11") (pinfunction "DVDD29_11") (pintype "passive"))
      (node (ref "U10") (pin "12") (pinfunction "DVDD8_12") (pintype "passive"))
      (node (ref "U10") (pin "13") (pinfunction "DVDD9_13") (pintype "passive"))
      (node (ref "U10") (pin "14") (pinfunction "DVDD30_14") (pintype "passive"))
      (node (ref "U10") (pin "15") (pinfunction "DVDD11_15") (pintype "passive"))
      (node (ref "U10") (pin "16") (pinfunction "DVDD12_16") (pintype "passive"))
      (node (ref "U10") (pin "19") (pinfunction "DVDD1_19") (pintype "passive"))
      (node (ref "U10") (pin "21") (pinfunction "DVDD14_21") (pintype "passive"))
      (node (ref "U10") (pin "22") (pinfunction "DVDD33_22") (pintype "passive"))
      (node (ref "U10") (pin "25") (pinfunction "DVDD15_25") (pintype "passive"))
      (node (ref "U10") (pin "26") (pinfunction "DVDD34_26") (pintype "passive"))
      (node (ref "U10") (pin "27") (pinfunction "DVDD17_27") (pintype "passive"))
      (node (ref "U10") (pin "28") (pinfunction "DVDD19_28") (pintype "passive"))
      (node (ref "U10") (pin "3") (pinfunction "DVDD26_3") (pintype "passive"))
      (node (ref "U10") (pin "31") (pinfunction "DVDD2_31") (pintype "passive"))
      (node (ref "U10") (pin "33") (pinfunction "DVDD36_33") (pintype "passive"))
      (node (ref "U10") (pin "34") (pinfunction "DVDD37_34") (pintype "passive"))
      (node (ref "U10") (pin "39") (pinfunction "DVDD38_39") (pintype "passive"))
      (node (ref "U10") (pin "4") (pinfunction "DVDD0_4") (pintype "passive"))
      (node (ref "U10") (pin "40") (pinfunction "DVDD20_40") (pintype "passive"))
      (node (ref "U10") (pin "41") (pinfunction "DVDD3_41") (pintype "passive"))
      (node (ref "U10") (pin "43") (pinfunction "DVDD23_43") (pintype "passive"))
      (node (ref "U10") (pin "46") (pinfunction "DVDD40_46") (pintype "passive"))
      (node (ref "U10") (pin "47") (pinfunction "DVDD41_47") (pintype "passive"))
      (node (ref "U10") (pin "48") (pinfunction "DVDD25_48") (pintype "passive"))
      (node (ref "U10") (pin "6") (pinfunction "DVDD5_6") (pintype "passive"))
      (node (ref "U10") (pin "7") (pinfunction "VDDA_PLL_7") (pintype "passive"))
      (node (ref "U11") (pin "11") (pinfunction "DVDD29_11") (pintype "passive"))
      (node (ref "U11") (pin "12") (pinfunction "DVDD8_12") (pintype "passive"))
      (node (ref "U11") (pin "13") (pinfunction "DVDD9_13") (pintype "passive"))
      (node (ref "U11") (pin "14") (pinfunction "DVDD30_14") (pintype "passive"))
      (node (ref "U11") (pin "15") (pinfunction "DVDD11_15") (pintype "passive"))
      (node (ref "U11") (pin "16") (pinfunction "DVDD12_16") (pintype "passive"))
      (node (ref "U11") (pin "19") (pinfunction "DVDD1_19") (pintype "passive"))
      (node (ref "U11") (pin "21") (pinfunction "DVDD14_21") (pintype "passive"))
      (node (ref "U11") (pin "22") (pinfunction "DVDD33_22") (pintype "passive"))
      (node (ref "U11") (pin "25") (pinfunction "DVDD15_25") (pintype "passive"))
      (node (ref "U11") (pin "26") (pinfunction "DVDD34_26") (pintype "passive"))
      (node (ref "U11") (pin "27") (pinfunction "DVDD17_27") (pintype "passive"))
      (node (ref "U11") (pin "28") (pinfunction "DVDD19_28") (pintype "passive"))
      (node (ref "U11") (pin "3") (pinfunction "DVDD26_3") (pintype "passive"))
      (node (ref "U11") (pin "31") (pinfunction "DVDD2_31") (pintype "passive"))
      (node (ref "U11") (pin "33") (pinfunction "DVDD36_33") (pintype "passive"))
      (node (ref "U11") (pin "34") (pinfunction "DVDD37_34") (pintype "passive"))
      (node (ref "U11") (pin "39") (pinfunction "DVDD38_39") (pintype "passive"))
      (node (ref "U11") (pin "4") (pinfunction "DVDD0_4") (pintype "passive"))
      (node (ref "U11") (pin "40") (pinfunction "DVDD20_40") (pintype "passive"))
      (node (ref "U11") (pin "41") (pinfunction "DVDD3_41") (pintype "passive"))
      (node (ref "U11") (pin "43") (pinfunction "DVDD23_43") (pintype "passive"))
      (node (ref "U11") (pin "46") (pinfunction "DVDD40_46") (pintype "passive"))
      (node (ref "U11") (pin "47") (pinfunction "DVDD41_47") (pintype "passive"))
      (node (ref "U11") (pin "48") (pinfunction "DVDD25_48") (pintype "passive"))
      (node (ref "U11") (pin "6") (pinfunction "DVDD5_6") (pintype "passive"))
      (node (ref "U11") (pin "7") (pinfunction "VDDA_PLL_7") (pintype "passive"))
      (node (ref "U12") (pin "11") (pinfunction "DVDD29_11") (pintype "passive"))
      (node (ref "U12") (pin "12") (pinfunction "DVDD8_12") (pintype "passive"))
      (node (ref "U12") (pin "13") (pinfunction "DVDD9_13") (pintype "passive"))
      (node (ref "U12") (pin "14") (pinfunction "DVDD30_14") (pintype "passive"))
      (node (ref "U12") (pin "15") (pinfunction "DVDD11_15") (pintype "passive"))
      (node (ref "U12") (pin "16") (pinfunction "DVDD12_16") (pintype "passive"))
      (node (ref "U12") (pin "19") (pinfunction "DVDD1_19") (pintype "passive"))
      (node (ref "U12") (pin "21") (pinfunction "DVDD14_21") (pintype "passive"))
      (node (ref "U12") (pin "22") (pinfunction "DVDD33_22") (pintype "passive"))
      (node (ref "U12") (pin "25") (pinfunction "DVDD15_25") (pintype "passive"))
      (node (ref "U12") (pin "26") (pinfunction "DVDD34_26") (pintype "passive"))
      (node (ref "U12") (pin "27") (pinfunction "DVDD17_27") (pintype "passive"))
      (node (ref "U12") (pin "28") (pinfunction "DVDD19_28") (pintype "passive"))
      (node (ref "U12") (pin "3") (pinfunction "DVDD26_3") (pintype "passive"))
      (node (ref "U12") (pin "31") (pinfunction "DVDD2_31") (pintype "passive"))
      (node (ref "U12") (pin "33") (pinfunction "DVDD36_33") (pintype "passive"))
      (node (ref "U12") (pin "34") (pinfunction "DVDD37_34") (pintype "passive"))
      (node (ref "U12") (pin "39") (pinfunction "DVDD38_39") (pintype "passive"))
      (node (ref "U12") (pin "4") (pinfunction "DVDD0_4") (pintype "passive"))
      (node (ref "U12") (pin "40") (pinfunction "DVDD20_40") (pintype "passive"))
      (node (ref "U12") (pin "41") (pinfunction "DVDD3_41") (pintype "passive"))
      (node (ref "U12") (pin "43") (pinfunction "DVDD23_43") (pintype "passive"))
      (node (ref "U12") (pin "46") (pinfunction "DVDD40_46") (pintype "passive"))
      (node (ref "U12") (pin "47") (pinfunction "DVDD41_47") (pintype "passive"))
      (node (ref "U12") (pin "48") (pinfunction "DVDD25_48") (pintype "passive"))
      (node (ref "U12") (pin "6") (pinfunction "DVDD5_6") (pintype "passive"))
      (node (ref "U12") (pin "7") (pinfunction "VDDA_PLL_7") (pintype "passive"))
      (node (ref "U13") (pin "11") (pinfunction "DVDD29_11") (pintype "passive"))
      (node (ref "U13") (pin "12") (pinfunction "DVDD8_12") (pintype "passive"))
      (node (ref "U13") (pin "13") (pinfunction "DVDD9_13") (pintype "passive"))
      (node (ref "U13") (pin "14") (pinfunction "DVDD30_14") (pintype "passive"))
      (node (ref "U13") (pin "15") (pinfunction "DVDD11_15") (pintype "passive"))
      (node (ref "U13") (pin "16") (pinfunction "DVDD12_16") (pintype "passive"))
      (node (ref "U13") (pin "19") (pinfunction "DVDD1_19") (pintype "passive"))
      (node (ref "U13") (pin "21") (pinfunction "DVDD14_21") (pintype "passive"))
      (node (ref "U13") (pin "22") (pinfunction "DVDD33_22") (pintype "passive"))
      (node (ref "U13") (pin "25") (pinfunction "DVDD15_25") (pintype "passive"))
      (node (ref "U13") (pin "26") (pinfunction "DVDD34_26") (pintype "passive"))
      (node (ref "U13") (pin "27") (pinfunction "DVDD17_27") (pintype "passive"))
      (node (ref "U13") (pin "28") (pinfunction "DVDD19_28") (pintype "passive"))
      (node (ref "U13") (pin "3") (pinfunction "DVDD26_3") (pintype "passive"))
      (node (ref "U13") (pin "31") (pinfunction "DVDD2_31") (pintype "passive"))
      (node (ref "U13") (pin "33") (pinfunction "DVDD36_33") (pintype "passive"))
      (node (ref "U13") (pin "34") (pinfunction "DVDD37_34") (pintype "passive"))
      (node (ref "U13") (pin "39") (pinfunction "DVDD38_39") (pintype "passive"))
      (node (ref "U13") (pin "4") (pinfunction "DVDD0_4") (pintype "passive"))
      (node (ref "U13") (pin "40") (pinfunction "DVDD20_40") (pintype "passive"))
      (node (ref "U13") (pin "41") (pinfunction "DVDD3_41") (pintype "passive"))
      (node (ref "U13") (pin "43") (pinfunction "DVDD23_43") (pintype "passive"))
      (node (ref "U13") (pin "46") (pinfunction "DVDD40_46") (pintype "passive"))
      (node (ref "U13") (pin "47") (pinfunction "DVDD41_47") (pintype "passive"))
      (node (ref "U13") (pin "48") (pinfunction "DVDD25_48") (pintype "passive"))
      (node (ref "U13") (pin "6") (pinfunction "DVDD5_6") (pintype "passive"))
      (node (ref "U13") (pin "7") (pinfunction "VDDA_PLL_7") (pintype "passive"))
      (node (ref "U14") (pin "11") (pinfunction "DVDD29_11") (pintype "passive"))
      (node (ref "U14") (pin "12") (pinfunction "DVDD8_12") (pintype "passive"))
      (node (ref "U14") (pin "13") (pinfunction "DVDD9_13") (pintype "passive"))
      (node (ref "U14") (pin "14") (pinfunction "DVDD30_14") (pintype "passive"))
      (node (ref "U14") (pin "15") (pinfunction "DVDD11_15") (pintype "passive"))
      (node (ref "U14") (pin "16") (pinfunction "DVDD12_16") (pintype "passive"))
      (node (ref "U14") (pin "19") (pinfunction "DVDD1_19") (pintype "passive"))
      (node (ref "U14") (pin "21") (pinfunction "DVDD14_21") (pintype "passive"))
      (node (ref "U14") (pin "22") (pinfunction "DVDD33_22") (pintype "passive"))
      (node (ref "U14") (pin "25") (pinfunction "DVDD15_25") (pintype "passive"))
      (node (ref "U14") (pin "26") (pinfunction "DVDD34_26") (pintype "passive"))
      (node (ref "U14") (pin "27") (pinfunction "DVDD17_27") (pintype "passive"))
      (node (ref "U14") (pin "28") (pinfunction "DVDD19_28") (pintype "passive"))
      (node (ref "U14") (pin "3") (pinfunction "DVDD26_3") (pintype "passive"))
      (node (ref "U14") (pin "31") (pinfunction "DVDD2_31") (pintype "passive"))
      (node (ref "U14") (pin "33") (pinfunction "DVDD36_33") (pintype "passive"))
      (node (ref "U14") (pin "34") (pinfunction "DVDD37_34") (pintype "passive"))
      (node (ref "U14") (pin "39") (pinfunction "DVDD38_39") (pintype "passive"))
      (node (ref "U14") (pin "4") (pinfunction "DVDD0_4") (pintype "passive"))
      (node (ref "U14") (pin "40") (pinfunction "DVDD20_40") (pintype "passive"))
      (node (ref "U14") (pin "41") (pinfunction "DVDD3_41") (pintype "passive"))
      (node (ref "U14") (pin "43") (pinfunction "DVDD23_43") (pintype "passive"))
      (node (ref "U14") (pin "46") (pinfunction "DVDD40_46") (pintype "passive"))
      (node (ref "U14") (pin "47") (pinfunction "DVDD41_47") (pintype "passive"))
      (node (ref "U14") (pin "48") (pinfunction "DVDD25_48") (pintype "passive"))
      (node (ref "U14") (pin "6") (pinfunction "DVDD5_6") (pintype "passive"))
      (node (ref "U14") (pin "7") (pinfunction "VDDA_PLL_7") (pintype "passive"))
      (node (ref "U15") (pin "11") (pinfunction "DVDD29_11") (pintype "passive"))
      (node (ref "U15") (pin "12") (pinfunction "DVDD8_12") (pintype "passive"))
      (node (ref "U15") (pin "13") (pinfunction "DVDD9_13") (pintype "passive"))
      (node (ref "U15") (pin "14") (pinfunction "DVDD30_14") (pintype "passive"))
      (node (ref "U15") (pin "15") (pinfunction "DVDD11_15") (pintype "passive"))
      (node (ref "U15") (pin "16") (pinfunction "DVDD12_16") (pintype "passive"))
      (node (ref "U15") (pin "19") (pinfunction "DVDD1_19") (pintype "passive"))
      (node (ref "U15") (pin "21") (pinfunction "DVDD14_21") (pintype "passive"))
      (node (ref "U15") (pin "22") (pinfunction "DVDD33_22") (pintype "passive"))
      (node (ref "U15") (pin "25") (pinfunction "DVDD15_25") (pintype "passive"))
      (node (ref "U15") (pin "26") (pinfunction "DVDD34_26") (pintype "passive"))
      (node (ref "U15") (pin "27") (pinfunction "DVDD17_27") (pintype "passive"))
      (node (ref "U15") (pin "28") (pinfunction "DVDD19_28") (pintype "passive"))
      (node (ref "U15") (pin "3") (pinfunction "DVDD26_3") (pintype "passive"))
      (node (ref "U15") (pin "31") (pinfunction "DVDD2_31") (pintype "passive"))
      (node (ref "U15") (pin "33") (pinfunction "DVDD36_33") (pintype "passive"))
      (node (ref "U15") (pin "34") (pinfunction "DVDD37_34") (pintype "passive"))
      (node (ref "U15") (pin "39") (pinfunction "DVDD38_39") (pintype "passive"))
      (node (ref "U15") (pin "4") (pinfunction "DVDD0_4") (pintype "passive"))
      (node (ref "U15") (pin "40") (pinfunction "DVDD20_40") (pintype "passive"))
      (node (ref "U15") (pin "41") (pinfunction "DVDD3_41") (pintype "passive"))
      (node (ref "U15") (pin "43") (pinfunction "DVDD23_43") (pintype "passive"))
      (node (ref "U15") (pin "46") (pinfunction "DVDD40_46") (pintype "passive"))
      (node (ref "U15") (pin "47") (pinfunction "DVDD41_47") (pintype "passive"))
      (node (ref "U15") (pin "48") (pinfunction "DVDD25_48") (pintype "passive"))
      (node (ref "U15") (pin "6") (pinfunction "DVDD5_6") (pintype "passive"))
      (node (ref "U15") (pin "7") (pinfunction "VDDA_PLL_7") (pintype "passive"))
      (node (ref "U16") (pin "11") (pinfunction "DVDD29_11") (pintype "passive"))
      (node (ref "U16") (pin "12") (pinfunction "DVDD8_12") (pintype "passive"))
      (node (ref "U16") (pin "13") (pinfunction "DVDD9_13") (pintype "passive"))
      (node (ref "U16") (pin "14") (pinfunction "DVDD30_14") (pintype "passive"))
      (node (ref "U16") (pin "15") (pinfunction "DVDD11_15") (pintype "passive"))
      (node (ref "U16") (pin "16") (pinfunction "DVDD12_16") (pintype "passive"))
      (node (ref "U16") (pin "19") (pinfunction "DVDD1_19") (pintype "passive"))
      (node (ref "U16") (pin "21") (pinfunction "DVDD14_21") (pintype "passive"))
      (node (ref "U16") (pin "22") (pinfunction "DVDD33_22") (pintype "passive"))
      (node (ref "U16") (pin "25") (pinfunction "DVDD15_25") (pintype "passive"))
      (node (ref "U16") (pin "26") (pinfunction "DVDD34_26") (pintype "passive"))
      (node (ref "U16") (pin "27") (pinfunction "DVDD17_27") (pintype "passive"))
      (node (ref "U16") (pin "28") (pinfunction "DVDD19_28") (pintype "passive"))
      (node (ref "U16") (pin "3") (pinfunction "DVDD26_3") (pintype "passive"))
      (node (ref "U16") (pin "31") (pinfunction "DVDD2_31") (pintype "passive"))
      (node (ref "U16") (pin "33") (pinfunction "DVDD36_33") (pintype "passive"))
      (node (ref "U16") (pin "34") (pinfunction "DVDD37_34") (pintype "passive"))
      (node (ref "U16") (pin "39") (pinfunction "DVDD38_39") (pintype "passive"))
      (node (ref "U16") (pin "4") (pinfunction "DVDD0_4") (pintype "passive"))
      (node (ref "U16") (pin "40") (pinfunction "DVDD20_40") (pintype "passive"))
      (node (ref "U16") (pin "41") (pinfunction "DVDD3_41") (pintype "passive"))
      (node (ref "U16") (pin "43") (pinfunction "DVDD23_43") (pintype "passive"))
      (node (ref "U16") (pin "46") (pinfunction "DVDD40_46") (pintype "passive"))
      (node (ref "U16") (pin "47") (pinfunction "DVDD41_47") (pintype "passive"))
      (node (ref "U16") (pin "48") (pinfunction "DVDD25_48") (pintype "passive"))
      (node (ref "U16") (pin "6") (pinfunction "DVDD5_6") (pintype "passive"))
      (node (ref "U16") (pin "7") (pinfunction "VDDA_PLL_7") (pintype "passive"))
      (node (ref "U17") (pin "11") (pinfunction "DVDD29_11") (pintype "passive"))
      (node (ref "U17") (pin "12") (pinfunction "DVDD8_12") (pintype "passive"))
      (node (ref "U17") (pin "13") (pinfunction "DVDD9_13") (pintype "passive"))
      (node (ref "U17") (pin "14") (pinfunction "DVDD30_14") (pintype "passive"))
      (node (ref "U17") (pin "15") (pinfunction "DVDD11_15") (pintype "passive"))
      (node (ref "U17") (pin "16") (pinfunction "DVDD12_16") (pintype "passive"))
      (node (ref "U17") (pin "19") (pinfunction "DVDD1_19") (pintype "passive"))
      (node (ref "U17") (pin "21") (pinfunction "DVDD14_21") (pintype "passive"))
      (node (ref "U17") (pin "22") (pinfunction "DVDD33_22") (pintype "passive"))
      (node (ref "U17") (pin "25") (pinfunction "DVDD15_25") (pintype "passive"))
      (node (ref "U17") (pin "26") (pinfunction "DVDD34_26") (pintype "passive"))
      (node (ref "U17") (pin "27") (pinfunction "DVDD17_27") (pintype "passive"))
      (node (ref "U17") (pin "28") (pinfunction "DVDD19_28") (pintype "passive"))
      (node (ref "U17") (pin "3") (pinfunction "DVDD26_3") (pintype "passive"))
      (node (ref "U17") (pin "31") (pinfunction "DVDD2_31") (pintype "passive"))
      (node (ref "U17") (pin "33") (pinfunction "DVDD36_33") (pintype "passive"))
      (node (ref "U17") (pin "34") (pinfunction "DVDD37_34") (pintype "passive"))
      (node (ref "U17") (pin "39") (pinfunction "DVDD38_39") (pintype "passive"))
      (node (ref "U17") (pin "4") (pinfunction "DVDD0_4") (pintype "passive"))
      (node (ref "U17") (pin "40") (pinfunction "DVDD20_40") (pintype "passive"))
      (node (ref "U17") (pin "41") (pinfunction "DVDD3_41") (pintype "passive"))
      (node (ref "U17") (pin "43") (pinfunction "DVDD23_43") (pintype "passive"))
      (node (ref "U17") (pin "46") (pinfunction "DVDD40_46") (pintype "passive"))
      (node (ref "U17") (pin "47") (pinfunction "DVDD41_47") (pintype "passive"))
      (node (ref "U17") (pin "48") (pinfunction "DVDD25_48") (pintype "passive"))
      (node (ref "U17") (pin "6") (pinfunction "DVDD5_6") (pintype "passive"))
      (node (ref "U17") (pin "7") (pinfunction "VDDA_PLL_7") (pintype "passive"))
      (node (ref "U18") (pin "11") (pinfunction "DVDD29_11") (pintype "passive"))
      (node (ref "U18") (pin "12") (pinfunction "DVDD8_12") (pintype "passive"))
      (node (ref "U18") (pin "13") (pinfunction "DVDD9_13") (pintype "passive"))
      (node (ref "U18") (pin "14") (pinfunction "DVDD30_14") (pintype "passive"))
      (node (ref "U18") (pin "15") (pinfunction "DVDD11_15") (pintype "passive"))
      (node (ref "U18") (pin "16") (pinfunction "DVDD12_16") (pintype "passive"))
      (node (ref "U18") (pin "19") (pinfunction "DVDD1_19") (pintype "passive"))
      (node (ref "U18") (pin "21") (pinfunction "DVDD14_21") (pintype "passive"))
      (node (ref "U18") (pin "22") (pinfunction "DVDD33_22") (pintype "passive"))
      (node (ref "U18") (pin "25") (pinfunction "DVDD15_25") (pintype "passive"))
      (node (ref "U18") (pin "26") (pinfunction "DVDD34_26") (pintype "passive"))
      (node (ref "U18") (pin "27") (pinfunction "DVDD17_27") (pintype "passive"))
      (node (ref "U18") (pin "28") (pinfunction "DVDD19_28") (pintype "passive"))
      (node (ref "U18") (pin "3") (pinfunction "DVDD26_3") (pintype "passive"))
      (node (ref "U18") (pin "31") (pinfunction "DVDD2_31") (pintype "passive"))
      (node (ref "U18") (pin "33") (pinfunction "DVDD36_33") (pintype "passive"))
      (node (ref "U18") (pin "34") (pinfunction "DVDD37_34") (pintype "passive"))
      (node (ref "U18") (pin "39") (pinfunction "DVDD38_39") (pintype "passive"))
      (node (ref "U18") (pin "4") (pinfunction "DVDD0_4") (pintype "passive"))
      (node (ref "U18") (pin "40") (pinfunction "DVDD20_40") (pintype "passive"))
      (node (ref "U18") (pin "41") (pinfunction "DVDD3_41") (pintype "passive"))
      (node (ref "U18") (pin "43") (pinfunction "DVDD23_43") (pintype "passive"))
      (node (ref "U18") (pin "46") (pinfunction "DVDD40_46") (pintype "passive"))
      (node (ref "U18") (pin "47") (pinfunction "DVDD41_47") (pintype "passive"))
      (node (ref "U18") (pin "48") (pinfunction "DVDD25_48") (pintype "passive"))
      (node (ref "U18") (pin "6") (pinfunction "DVDD5_6") (pintype "passive"))
      (node (ref "U18") (pin "7") (pinfunction "VDDA_PLL_7") (pintype "passive"))
      (node (ref "U2") (pin "11") (pinfunction "DVDD29_11") (pintype "passive"))
      (node (ref "U2") (pin "12") (pinfunction "DVDD8_12") (pintype "passive"))
      (node (ref "U2") (pin "13") (pinfunction "DVDD9_13") (pintype "passive"))
      (node (ref "U2") (pin "14") (pinfunction "DVDD30_14") (pintype "passive"))
      (node (ref "U2") (pin "15") (pinfunction "DVDD11_15") (pintype "passive"))
      (node (ref "U2") (pin "16") (pinfunction "DVDD12_16") (pintype "passive"))
      (node (ref "U2") (pin "19") (pinfunction "DVDD1_19") (pintype "passive"))
      (node (ref "U2") (pin "21") (pinfunction "DVDD14_21") (pintype "passive"))
      (node (ref "U2") (pin "22") (pinfunction "DVDD33_22") (pintype "passive"))
      (node (ref "U2") (pin "25") (pinfunction "DVDD15_25") (pintype "passive"))
      (node (ref "U2") (pin "26") (pinfunction "DVDD34_26") (pintype "passive"))
      (node (ref "U2") (pin "27") (pinfunction "DVDD17_27") (pintype "passive"))
      (node (ref "U2") (pin "28") (pinfunction "DVDD19_28") (pintype "passive"))
      (node (ref "U2") (pin "3") (pinfunction "DVDD26_3") (pintype "passive"))
      (node (ref "U2") (pin "31") (pinfunction "DVDD2_31") (pintype "passive"))
      (node (ref "U2") (pin "33") (pinfunction "DVDD36_33") (pintype "passive"))
      (node (ref "U2") (pin "34") (pinfunction "DVDD37_34") (pintype "passive"))
      (node (ref "U2") (pin "39") (pinfunction "DVDD38_39") (pintype "passive"))
      (node (ref "U2") (pin "4") (pinfunction "DVDD0_4") (pintype "passive"))
      (node (ref "U2") (pin "40") (pinfunction "DVDD20_40") (pintype "passive"))
      (node (ref "U2") (pin "41") (pinfunction "DVDD3_41") (pintype "passive"))
      (node (ref "U2") (pin "43") (pinfunction "DVDD23_43") (pintype "passive"))
      (node (ref "U2") (pin "46") (pinfunction "DVDD40_46") (pintype "passive"))
      (node (ref "U2") (pin "47") (pinfunction "DVDD41_47") (pintype "passive"))
      (node (ref "U2") (pin "48") (pinfunction "DVDD25_48") (pintype "passive"))
      (node (ref "U2") (pin "6") (pinfunction "DVDD5_6") (pintype "passive"))
      (node (ref "U2") (pin "7") (pinfunction "VDDA_PLL_7") (pintype "passive"))
      (node (ref "U3") (pin "11") (pinfunction "DVDD29_11") (pintype "passive"))
      (node (ref "U3") (pin "12") (pinfunction "DVDD8_12") (pintype "passive"))
      (node (ref "U3") (pin "13") (pinfunction "DVDD9_13") (pintype "passive"))
      (node (ref "U3") (pin "14") (pinfunction "DVDD30_14") (pintype "passive"))
      (node (ref "U3") (pin "15") (pinfunction "DVDD11_15") (pintype "passive"))
      (node (ref "U3") (pin "16") (pinfunction "DVDD12_16") (pintype "passive"))
      (node (ref "U3") (pin "19") (pinfunction "DVDD1_19") (pintype "passive"))
      (node (ref "U3") (pin "21") (pinfunction "DVDD14_21") (pintype "passive"))
      (node (ref "U3") (pin "22") (pinfunction "DVDD33_22") (pintype "passive"))
      (node (ref "U3") (pin "25") (pinfunction "DVDD15_25") (pintype "passive"))
      (node (ref "U3") (pin "26") (pinfunction "DVDD34_26") (pintype "passive"))
      (node (ref "U3") (pin "27") (pinfunction "DVDD17_27") (pintype "passive"))
      (node (ref "U3") (pin "28") (pinfunction "DVDD19_28") (pintype "passive"))
      (node (ref "U3") (pin "3") (pinfunction "DVDD26_3") (pintype "passive"))
      (node (ref "U3") (pin "31") (pinfunction "DVDD2_31") (pintype "passive"))
      (node (ref "U3") (pin "33") (pinfunction "DVDD36_33") (pintype "passive"))
      (node (ref "U3") (pin "34") (pinfunction "DVDD37_34") (pintype "passive"))
      (node (ref "U3") (pin "39") (pinfunction "DVDD38_39") (pintype "passive"))
      (node (ref "U3") (pin "4") (pinfunction "DVDD0_4") (pintype "passive"))
      (node (ref "U3") (pin "40") (pinfunction "DVDD20_40") (pintype "passive"))
      (node (ref "U3") (pin "41") (pinfunction "DVDD3_41") (pintype "passive"))
      (node (ref "U3") (pin "43") (pinfunction "DVDD23_43") (pintype "passive"))
      (node (ref "U3") (pin "46") (pinfunction "DVDD40_46") (pintype "passive"))
      (node (ref "U3") (pin "47") (pinfunction "DVDD41_47") (pintype "passive"))
      (node (ref "U3") (pin "48") (pinfunction "DVDD25_48") (pintype "passive"))
      (node (ref "U3") (pin "6") (pinfunction "DVDD5_6") (pintype "passive"))
      (node (ref "U3") (pin "7") (pinfunction "VDDA_PLL_7") (pintype "passive"))
      (node (ref "U4") (pin "11") (pinfunction "DVDD29_11") (pintype "passive"))
      (node (ref "U4") (pin "12") (pinfunction "DVDD8_12") (pintype "passive"))
      (node (ref "U4") (pin "13") (pinfunction "DVDD9_13") (pintype "passive"))
      (node (ref "U4") (pin "14") (pinfunction "DVDD30_14") (pintype "passive"))
      (node (ref "U4") (pin "15") (pinfunction "DVDD11_15") (pintype "passive"))
      (node (ref "U4") (pin "16") (pinfunction "DVDD12_16") (pintype "passive"))
      (node (ref "U4") (pin "19") (pinfunction "DVDD1_19") (pintype "passive"))
      (node (ref "U4") (pin "21") (pinfunction "DVDD14_21") (pintype "passive"))
      (node (ref "U4") (pin "22") (pinfunction "DVDD33_22") (pintype "passive"))
      (node (ref "U4") (pin "25") (pinfunction "DVDD15_25") (pintype "passive"))
      (node (ref "U4") (pin "26") (pinfunction "DVDD34_26") (pintype "passive"))
      (node (ref "U4") (pin "27") (pinfunction "DVDD17_27") (pintype "passive"))
      (node (ref "U4") (pin "28") (pinfunction "DVDD19_28") (pintype "passive"))
      (node (ref "U4") (pin "3") (pinfunction "DVDD26_3") (pintype "passive"))
      (node (ref "U4") (pin "31") (pinfunction "DVDD2_31") (pintype "passive"))
      (node (ref "U4") (pin "33") (pinfunction "DVDD36_33") (pintype "passive"))
      (node (ref "U4") (pin "34") (pinfunction "DVDD37_34") (pintype "passive"))
      (node (ref "U4") (pin "39") (pinfunction "DVDD38_39") (pintype "passive"))
      (node (ref "U4") (pin "4") (pinfunction "DVDD0_4") (pintype "passive"))
      (node (ref "U4") (pin "40") (pinfunction "DVDD20_40") (pintype "passive"))
      (node (ref "U4") (pin "41") (pinfunction "DVDD3_41") (pintype "passive"))
      (node (ref "U4") (pin "43") (pinfunction "DVDD23_43") (pintype "passive"))
      (node (ref "U4") (pin "46") (pinfunction "DVDD40_46") (pintype "passive"))
      (node (ref "U4") (pin "47") (pinfunction "DVDD41_47") (pintype "passive"))
      (node (ref "U4") (pin "48") (pinfunction "DVDD25_48") (pintype "passive"))
      (node (ref "U4") (pin "6") (pinfunction "DVDD5_6") (pintype "passive"))
      (node (ref "U4") (pin "7") (pinfunction "VDDA_PLL_7") (pintype "passive"))
      (node (ref "U5") (pin "11") (pinfunction "DVDD29_11") (pintype "passive"))
      (node (ref "U5") (pin "12") (pinfunction "DVDD8_12") (pintype "passive"))
      (node (ref "U5") (pin "13") (pinfunction "DVDD9_13") (pintype "passive"))
      (node (ref "U5") (pin "14") (pinfunction "DVDD30_14") (pintype "passive"))
      (node (ref "U5") (pin "15") (pinfunction "DVDD11_15") (pintype "passive"))
      (node (ref "U5") (pin "16") (pinfunction "DVDD12_16") (pintype "passive"))
      (node (ref "U5") (pin "19") (pinfunction "DVDD1_19") (pintype "passive"))
      (node (ref "U5") (pin "21") (pinfunction "DVDD14_21") (pintype "passive"))
      (node (ref "U5") (pin "22") (pinfunction "DVDD33_22") (pintype "passive"))
      (node (ref "U5") (pin "25") (pinfunction "DVDD15_25") (pintype "passive"))
      (node (ref "U5") (pin "26") (pinfunction "DVDD34_26") (pintype "passive"))
      (node (ref "U5") (pin "27") (pinfunction "DVDD17_27") (pintype "passive"))
      (node (ref "U5") (pin "28") (pinfunction "DVDD19_28") (pintype "passive"))
      (node (ref "U5") (pin "3") (pinfunction "DVDD26_3") (pintype "passive"))
      (node (ref "U5") (pin "31") (pinfunction "DVDD2_31") (pintype "passive"))
      (node (ref "U5") (pin "33") (pinfunction "DVDD36_33") (pintype "passive"))
      (node (ref "U5") (pin "34") (pinfunction "DVDD37_34") (pintype "passive"))
      (node (ref "U5") (pin "39") (pinfunction "DVDD38_39") (pintype "passive"))
      (node (ref "U5") (pin "4") (pinfunction "DVDD0_4") (pintype "passive"))
      (node (ref "U5") (pin "40") (pinfunction "DVDD20_40") (pintype "passive"))
      (node (ref "U5") (pin "41") (pinfunction "DVDD3_41") (pintype "passive"))
      (node (ref "U5") (pin "43") (pinfunction "DVDD23_43") (pintype "passive"))
      (node (ref "U5") (pin "46") (pinfunction "DVDD40_46") (pintype "passive"))
      (node (ref "U5") (pin "47") (pinfunction "DVDD41_47") (pintype "passive"))
      (node (ref "U5") (pin "48") (pinfunction "DVDD25_48") (pintype "passive"))
      (node (ref "U5") (pin "6") (pinfunction "DVDD5_6") (pintype "passive"))
      (node (ref "U5") (pin "7") (pinfunction "VDDA_PLL_7") (pintype "passive"))
      (node (ref "U7") (pin "11") (pinfunction "DVDD29_11") (pintype "passive"))
      (node (ref "U7") (pin "12") (pinfunction "DVDD8_12") (pintype "passive"))
      (node (ref "U7") (pin "13") (pinfunction "DVDD9_13") (pintype "passive"))
      (node (ref "U7") (pin "14") (pinfunction "DVDD30_14") (pintype "passive"))
      (node (ref "U7") (pin "15") (pinfunction "DVDD11_15") (pintype "passive"))
      (node (ref "U7") (pin "16") (pinfunction "DVDD12_16") (pintype "passive"))
      (node (ref "U7") (pin "19") (pinfunction "DVDD1_19") (pintype "passive"))
      (node (ref "U7") (pin "21") (pinfunction "DVDD14_21") (pintype "passive"))
      (node (ref "U7") (pin "22") (pinfunction "DVDD33_22") (pintype "passive"))
      (node (ref "U7") (pin "25") (pinfunction "DVDD15_25") (pintype "passive"))
      (node (ref "U7") (pin "26") (pinfunction "DVDD34_26") (pintype "passive"))
      (node (ref "U7") (pin "27") (pinfunction "DVDD17_27") (pintype "passive"))
      (node (ref "U7") (pin "28") (pinfunction "DVDD19_28") (pintype "passive"))
      (node (ref "U7") (pin "3") (pinfunction "DVDD26_3") (pintype "passive"))
      (node (ref "U7") (pin "31") (pinfunction "DVDD2_31") (pintype "passive"))
      (node (ref "U7") (pin "33") (pinfunction "DVDD36_33") (pintype "passive"))
      (node (ref "U7") (pin "34") (pinfunction "DVDD37_34") (pintype "passive"))
      (node (ref "U7") (pin "39") (pinfunction "DVDD38_39") (pintype "passive"))
      (node (ref "U7") (pin "4") (pinfunction "DVDD0_4") (pintype "passive"))
      (node (ref "U7") (pin "40") (pinfunction "DVDD20_40") (pintype "passive"))
      (node (ref "U7") (pin "41") (pinfunction "DVDD3_41") (pintype "passive"))
      (node (ref "U7") (pin "43") (pinfunction "DVDD23_43") (pintype "passive"))
      (node (ref "U7") (pin "46") (pinfunction "DVDD40_46") (pintype "passive"))
      (node (ref "U7") (pin "47") (pinfunction "DVDD41_47") (pintype "passive"))
      (node (ref "U7") (pin "48") (pinfunction "DVDD25_48") (pintype "passive"))
      (node (ref "U7") (pin "6") (pinfunction "DVDD5_6") (pintype "passive"))
      (node (ref "U7") (pin "7") (pinfunction "VDDA_PLL_7") (pintype "passive"))
      (node (ref "U8") (pin "11") (pinfunction "DVDD29_11") (pintype "passive"))
      (node (ref "U8") (pin "12") (pinfunction "DVDD8_12") (pintype "passive"))
      (node (ref "U8") (pin "13") (pinfunction "DVDD9_13") (pintype "passive"))
      (node (ref "U8") (pin "14") (pinfunction "DVDD30_14") (pintype "passive"))
      (node (ref "U8") (pin "15") (pinfunction "DVDD11_15") (pintype "passive"))
      (node (ref "U8") (pin "16") (pinfunction "DVDD12_16") (pintype "passive"))
      (node (ref "U8") (pin "19") (pinfunction "DVDD1_19") (pintype "passive"))
      (node (ref "U8") (pin "21") (pinfunction "DVDD14_21") (pintype "passive"))
      (node (ref "U8") (pin "22") (pinfunction "DVDD33_22") (pintype "passive"))
      (node (ref "U8") (pin "25") (pinfunction "DVDD15_25") (pintype "passive"))
      (node (ref "U8") (pin "26") (pinfunction "DVDD34_26") (pintype "passive"))
      (node (ref "U8") (pin "27") (pinfunction "DVDD17_27") (pintype "passive"))
      (node (ref "U8") (pin "28") (pinfunction "DVDD19_28") (pintype "passive"))
      (node (ref "U8") (pin "3") (pinfunction "DVDD26_3") (pintype "passive"))
      (node (ref "U8") (pin "31") (pinfunction "DVDD2_31") (pintype "passive"))
      (node (ref "U8") (pin "33") (pinfunction "DVDD36_33") (pintype "passive"))
      (node (ref "U8") (pin "34") (pinfunction "DVDD37_34") (pintype "passive"))
      (node (ref "U8") (pin "39") (pinfunction "DVDD38_39") (pintype "passive"))
      (node (ref "U8") (pin "4") (pinfunction "DVDD0_4") (pintype "passive"))
      (node (ref "U8") (pin "40") (pinfunction "DVDD20_40") (pintype "passive"))
      (node (ref "U8") (pin "41") (pinfunction "DVDD3_41") (pintype "passive"))
      (node (ref "U8") (pin "43") (pinfunction "DVDD23_43") (pintype "passive"))
      (node (ref "U8") (pin "46") (pinfunction "DVDD40_46") (pintype "passive"))
      (node (ref "U8") (pin "47") (pinfunction "DVDD41_47") (pintype "passive"))
      (node (ref "U8") (pin "48") (pinfunction "DVDD25_48") (pintype "passive"))
      (node (ref "U8") (pin "6") (pinfunction "DVDD5_6") (pintype "passive"))
      (node (ref "U8") (pin "7") (pinfunction "VDDA_PLL_7") (pintype "passive"))
      (node (ref "U9") (pin "11") (pinfunction "DVDD29_11") (pintype "passive"))
      (node (ref "U9") (pin "12") (pinfunction "DVDD8_12") (pintype "passive"))
      (node (ref "U9") (pin "13") (pinfunction "DVDD9_13") (pintype "passive"))
      (node (ref "U9") (pin "14") (pinfunction "DVDD30_14") (pintype "passive"))
      (node (ref "U9") (pin "15") (pinfunction "DVDD11_15") (pintype "passive"))
      (node (ref "U9") (pin "16") (pinfunction "DVDD12_16") (pintype "passive"))
      (node (ref "U9") (pin "19") (pinfunction "DVDD1_19") (pintype "passive"))
      (node (ref "U9") (pin "21") (pinfunction "DVDD14_21") (pintype "passive"))
      (node (ref "U9") (pin "22") (pinfunction "DVDD33_22") (pintype "passive"))
      (node (ref "U9") (pin "25") (pinfunction "DVDD15_25") (pintype "passive"))
      (node (ref "U9") (pin "26") (pinfunction "DVDD34_26") (pintype "passive"))
      (node (ref "U9") (pin "27") (pinfunction "DVDD17_27") (pintype "passive"))
      (node (ref "U9") (pin "28") (pinfunction "DVDD19_28") (pintype "passive"))
      (node (ref "U9") (pin "3") (pinfunction "DVDD26_3") (pintype "passive"))
      (node (ref "U9") (pin "31") (pinfunction "DVDD2_31") (pintype "passive"))
      (node (ref "U9") (pin "33") (pinfunction "DVDD36_33") (pintype "passive"))
      (node (ref "U9") (pin "34") (pinfunction "DVDD37_34") (pintype "passive"))
      (node (ref "U9") (pin "39") (pinfunction "DVDD38_39") (pintype "passive"))
      (node (ref "U9") (pin "4") (pinfunction "DVDD0_4") (pintype "passive"))
      (node (ref "U9") (pin "40") (pinfunction "DVDD20_40") (pintype "passive"))
      (node (ref "U9") (pin "41") (pinfunction "DVDD3_41") (pintype "passive"))
      (node (ref "U9") (pin "43") (pinfunction "DVDD23_43") (pintype "passive"))
      (node (ref "U9") (pin "46") (pinfunction "DVDD40_46") (pintype "passive"))
      (node (ref "U9") (pin "47") (pinfunction "DVDD41_47") (pintype "passive"))
      (node (ref "U9") (pin "48") (pinfunction "DVDD25_48") (pintype "passive"))
      (node (ref "U9") (pin "6") (pinfunction "DVDD5_6") (pintype "passive"))
      (node (ref "U9") (pin "7") (pinfunction "VDDA_PLL_7") (pintype "passive"))
    )
    (net (code "2") (name "/3.3V") (class "Default")
      (node (ref "C111") (pin "1") (pinfunction "1_1") (pintype "passive"))
      (node (ref "C112") (pin "1") (pinfunction "1_1") (pintype "passive"))
      (node (ref "C113") (pin "1") (pinfunction "1_1") (pintype "passive"))
      (node (ref "C114") (pin "1") (pinfunction "1_1") (pintype "passive"))
      (node (ref "C13") (pin "1") (pinfunction "1_1") (pintype "passive"))
      (node (ref "C133") (pin "2") (pinfunction "2_2") (pintype "passive"))
      (node (ref "C136") (pin "2") (pinfunction "2_2") (pintype "passive"))
      (node (ref "C139") (pin "2") (pinfunction "2_2") (pintype "passive"))
      (node (ref "C14") (pin "1") (pinfunction "1_1") (pintype "passive"))
      (node (ref "C142") (pin "2") (pinfunction "2_2") (pintype "passive"))
      (node (ref "C15") (pin "1") (pinfunction "1_1") (pintype "passive"))
      (node (ref "C155") (pin "1") (pinfunction "1_1") (pintype "passive"))
      (node (ref "C156") (pin "1") (pinfunction "1_1") (pintype "passive"))
      (node (ref "C157") (pin "1") (pinfunction "1_1") (pintype "passive"))
      (node (ref "C158") (pin "1") (pinfunction "1_1") (pintype "passive"))
      (node (ref "C16") (pin "1") (pinfunction "1_1") (pintype "passive"))
      (node (ref "C177") (pin "2") (pinfunction "2_2") (pintype "passive"))
      (node (ref "C180") (pin "2") (pinfunction "2_2") (pintype "passive"))
      (node (ref "C183") (pin "2") (pinfunction "2_2") (pintype "passive"))
      (node (ref "C186") (pin "2") (pinfunction "2_2") (pintype "passive"))
      (node (ref "C211") (pin "1") (pinfunction "1_1") (pintype "passive"))
      (node (ref "C229") (pin "1") (pinfunction "1_1") (pintype "passive"))
      (node (ref "C233") (pin "1") (pinfunction "1_1") (pintype "passive"))
      (node (ref "C234") (pin "1") (pinfunction "1_1") (pintype "passive"))
      (node (ref "C235") (pin "1") (pinfunction "1_1") (pintype "passive"))
      (node (ref "C236") (pin "1") (pinfunction "1_1") (pintype "passive"))
      (node (ref "C237") (pin "1") (pinfunction "1_1") (pintype "passive"))
      (node (ref "C248") (pin "1") (pinfunction "1_1") (pintype "passive"))
      (node (ref "C249") (pin "1") (pinfunction "1_1") (pintype "passive"))
      (node (ref "C250") (pin "1") (pinfunction "1_1") (pintype "passive"))
      (node (ref "C252") (pin "1") (pinfunction "1_1") (pintype "passive"))
      (node (ref "C311") (pin "1") (pinfunction "1_1") (pintype "passive"))
      (node (ref "C34") (pin "1") (pinfunction "1_1") (pintype "passive"))
      (node (ref "C37") (pin "2") (pinfunction "2_2") (pintype "passive"))
      (node (ref "C40") (pin "2") (pinfunction "2_2") (pintype "passive"))
      (node (ref "C43") (pin "2") (pinfunction "2_2") (pintype "passive"))
      (node (ref "C46") (pin "2") (pinfunction "2_2") (pintype "passive"))
      (node (ref "C59") (pin "1") (pinfunction "1_1") (pintype "passive"))
      (node (ref "C60") (pin "1") (pinfunction "1_1") (pintype "passive"))
      (node (ref "C61") (pin "1") (pinfunction "1_1") (pintype "passive"))
      (node (ref "C62") (pin "1") (pinfunction "1_1") (pintype "passive"))
      (node (ref "C63") (pin "1") (pinfunction "1_1") (pintype "passive"))
      (node (ref "C73") (pin "1") (pinfunction "1_1") (pintype "passive"))
      (node (ref "C74") (pin "1") (pinfunction "1_1") (pintype "passive"))
      (node (ref "C75") (pin "1") (pinfunction "1_1") (pintype "passive"))
      (node (ref "C76") (pin "1") (pinfunction "1_1") (pintype "passive"))
      (node (ref "C89") (pin "2") (pinfunction "2_2") (pintype "passive"))
      (node (ref "C92") (pin "2") (pinfunction "2_2") (pintype "passive"))
      (node (ref "C95") (pin "2") (pinfunction "2_2") (pintype "passive"))
      (node (ref "C98") (pin "2") (pinfunction "2_2") (pintype "passive"))
      (node (ref "J1") (pin "2") (pinfunction "2_2") (pintype "passive"))
      (node (ref "R1") (pin "1") (pinfunction "1_1") (pintype "passive"))
      (node (ref "R10") (pin "1") (pinfunction "1_1") (pintype "passive"))
      (node (ref "R11") (pin "1") (pinfunction "1_1") (pintype "passive"))
      (node (ref "R12") (pin "1") (pinfunction "1_1") (pintype "passive"))
      (node (ref "R13") (pin "1") (pinfunction "1_1") (pintype "passive"))
      (node (ref "R14") (pin "1") (pinfunction "1_1") (pintype "passive"))
      (node (ref "R15") (pin "1") (pinfunction "1_1") (pintype "passive"))
      (node (ref "R16") (pin "1") (pinfunction "1_1") (pintype "passive"))
      (node (ref "R17") (pin "1") (pinfunction "1_1") (pintype "passive"))
      (node (ref "R2") (pin "1") (pinfunction "1_1") (pintype "passive"))
      (node (ref "R3") (pin "1") (pinfunction "1_1") (pintype "passive"))
      (node (ref "R4") (pin "1") (pinfunction "1_1") (pintype "passive"))
      (node (ref "R48") (pin "1") (pinfunction "1_1") (pintype "passive"))
      (node (ref "R49") (pin "1") (pinfunction "1_1") (pintype "passive"))
      (node (ref "R5") (pin "1") (pinfunction "1_1") (pintype "passive"))
      (node (ref "R50") (pin "1") (pinfunction "1_1") (pintype "passive"))
      (node (ref "R51") (pin "1") (pinfunction "1_1") (pintype "passive"))
      (node (ref "R52") (pin "2") (pinfunction "2_2") (pintype "passive"))
      (node (ref "R53") (pin "2") (pinfunction "2_2") (pintype "passive"))
      (node (ref "R54") (pin "2") (pinfunction "2_2") (pintype "passive"))
      (node (ref "R55") (pin "2") (pinfunction "2_2") (pintype "passive"))
      (node (ref "R6") (pin "1") (pinfunction "1_1") (pintype "passive"))
      (node (ref "R7") (pin "1") (pinfunction "1_1") (pintype "passive"))
      (node (ref "R8") (pin "1") (pinfunction "1_1") (pintype "passive"))
      (node (ref "R9") (pin "2") (pinfunction "2_2") (pintype "passive"))
      (node (ref "U1") (pin "10") (pinfunction "VDD_10") (pintype "passive"))
      (node (ref "U1") (pin "19") (pinfunction "AVDD_19") (pintype "passive"))
      (node (ref "U1") (pin "26") (pinfunction "VDD_26") (pintype "passive"))
      (node (ref "U1") (pin "35") (pinfunction "VUSB3V3_35") (pintype "passive"))
      (node (ref "U1") (pin "38") (pinfunction "VDD_38") (pintype "passive"))
      (node (ref "U1") (pin "57") (pinfunction "VDD_57") (pintype "passive"))
      (node (ref "U10") (pin "24") (pinfunction "OVDD1_24") (pintype "passive"))
      (node (ref "U10") (pin "37") (pinfunction "OVDD0_37") (pintype "passive"))
      (node (ref "U11") (pin "24") (pinfunction "OVDD1_24") (pintype "passive"))
      (node (ref "U11") (pin "37") (pinfunction "OVDD0_37") (pintype "passive"))
      (node (ref "U12") (pin "24") (pinfunction "OVDD1_24") (pintype "passive"))
      (node (ref "U12") (pin "37") (pinfunction "OVDD0_37") (pintype "passive"))
      (node (ref "U13") (pin "24") (pinfunction "OVDD1_24") (pintype "passive"))
      (node (ref "U13") (pin "37") (pinfunction "OVDD0_37") (pintype "passive"))
      (node (ref "U14") (pin "24") (pinfunction "OVDD1_24") (pintype "passive"))
      (node (ref "U14") (pin "37") (pinfunction "OVDD0_37") (pintype "passive"))
      (node (ref "U15") (pin "24") (pinfunction "OVDD1_24") (pintype "passive"))
      (node (ref "U15") (pin "37") (pinfunction "OVDD0_37") (pintype "passive"))
      (node (ref "U16") (pin "24") (pinfunction "OVDD1_24") (pintype "passive"))
      (node (ref "U16") (pin "37") (pinfunction "OVDD0_37") (pintype "passive"))
      (node (ref "U17") (pin "24") (pinfunction "OVDD1_24") (pintype "passive"))
      (node (ref "U17") (pin "37") (pinfunction "OVDD0_37") (pintype "passive"))
      (node (ref "U18") (pin "24") (pinfunction "OVDD1_24") (pintype "passive"))
      (node (ref "U18") (pin "37") (pinfunction "OVDD0_37") (pintype "passive"))
      (node (ref "U19") (pin "1") (pinfunction "OUTPUT_1") (pintype "passive"))
      (node (ref "U2") (pin "24") (pinfunction "OVDD1_24") (pintype "passive"))
      (node (ref "U2") (pin "37") (pinfunction "OVDD0_37") (pintype "passive"))
      (node (ref "U25") (pin "6") (pinfunction "Vlogic_6") (pintype "passive"))
      (node (ref "U3") (pin "24") (pinfunction "OVDD1_24") (pintype "passive"))
      (node (ref "U3") (pin "37") (pinfunction "OVDD0_37") (pintype "passive"))
      (node (ref "U30") (pin "6") (pinfunction "Vlogic_6") (pintype "passive"))
      (node (ref "U4") (pin "24") (pinfunction "OVDD1_24") (pintype "passive"))
      (node (ref "U4") (pin "37") (pinfunction "OVDD0_37") (pintype "passive"))
      (node (ref "U5") (pin "24") (pinfunction "OVDD1_24") (pintype "passive"))
      (node (ref "U5") (pin "37") (pinfunction "OVDD0_37") (pintype "passive"))
      (node (ref "U6") (pin "5") (pinfunction "Vout_5") (pintype "passive"))
      (node (ref "U7") (pin "24") (pinfunction "OVDD1_24") (pintype "passive"))
      (node (ref "U7") (pin "37") (pinfunction "OVDD0_37") (pintype "passive"))
      (node (ref "U8") (pin "24") (pinfunction "OVDD1_24") (pintype "passive"))
      (node (ref "U8") (pin "37") (pinfunction "OVDD0_37") (pintype "passive"))
      (node (ref "U9") (pin "24") (pinfunction "OVDD1_24") (pintype "passive"))
      (node (ref "U9") (pin "37") (pinfunction "OVDD0_37") (pintype "passive"))
    )
    (net (code "3") (name "/5.0V") (class "Default")
      (node (ref "C188") (pin "2") (pinfunction "2_2") (pintype "passive"))
      (node (ref "C231") (pin "1") (pinfunction "1_1") (pintype "passive"))
      (node (ref "C308") (pin "2") (pinfunction "2_2") (pintype "passive"))
      (node (ref "D1") (pin "1") (pinfunction "A1_1") (pintype "passive"))
      (node (ref "D1") (pin "2") (pinfunction "A2_2") (pintype "passive"))
      (node (ref "D2") (pin "1") (pinfunction "A1_1") (pintype "passive"))
      (node (ref "D2") (pin "2") (pinfunction "A2_2") (pintype "passive"))
      (node (ref "R42") (pin "1") (pinfunction "1_1") (pintype "passive"))
      (node (ref "R63") (pin "1") (pinfunction "1_1") (pintype "passive"))
      (node (ref "U20") (pin "3") (pinfunction "Vin_3") (pintype "passive"))
      (node (ref "U22") (pin "1") (pinfunction "OUTPUT_1") (pintype "passive"))
      (node (ref "U23") (pin "3") (pinfunction "Vin_3") (pintype "passive"))
      (node (ref "U25") (pin "7") (pinfunction "VCC_7") (pintype "passive"))
      (node (ref "U30") (pin "7") (pinfunction "VCC_7") (pintype "passive"))
    )
    (net (code "4") (name "/5.0V PS") (class "Default")
      (node (ref "J2") (pin "4") (pinfunction "4_4") (pintype "passive"))
      (node (ref "R42") (pin "2") (pinfunction "2_2") (pintype "passive"))
    )
    (net (code "5") (name "/12V") (class "Default")
      (node (ref "C190") (pin "1") (pinfunction "1_1") (pintype "passive"))
      (node (ref "C191") (pin "1") (pinfunction "1_1") (pintype "passive"))
      (node (ref "C192") (pin "1") (pinfunction "1_1") (pintype "passive"))
      (node (ref "C193") (pin "1") (pinfunction "1_1") (pintype "passive"))
      (node (ref "C194") (pin "1") (pinfunction "1_1") (pintype "passive"))
      (node (ref "C195") (pin "1") (pinfunction "1_1") (pintype "passive"))
      (node (ref "C196") (pin "1") (pinfunction "1_1") (pintype "passive"))
      (node (ref "C197") (pin "1") (pinfunction "1_1") (pintype "passive"))
      (node (ref "C207") (pin "1") (pinfunction "1_1") (pintype "passive"))
      (node (ref "C208") (pin "1") (pinfunction "1_1") (pintype "passive"))
      (node (ref "C210") (pin "1") (pinfunction "1_1") (pintype "passive"))
      (node (ref "C213") (pin "1") (pinfunction "1_1") (pintype "passive"))
      (node (ref "C214") (pin "1") (pinfunction "1_1") (pintype "passive"))
      (node (ref "C215") (pin "1") (pinfunction "1_1") (pintype "passive"))
      (node (ref "C216") (pin "1") (pinfunction "1_1") (pintype "passive"))
      (node (ref "C217") (pin "1") (pinfunction "1_1") (pintype "passive"))
      (node (ref "C218") (pin "1") (pinfunction "1_1") (pintype "passive"))
      (node (ref "C219") (pin "1") (pinfunction "1_1") (pintype "passive"))
      (node (ref "C230") (pin "1") (pinfunction "1_1") (pintype "passive"))
      (node (ref "C263") (pin "1") (pinfunction "1_1") (pintype "passive"))
      (node (ref "C264") (pin "1") (pinfunction "1_1") (pintype "passive"))
      (node (ref "C265") (pin "1") (pinfunction "1_1") (pintype "passive"))
      (node (ref "C266") (pin "1") (pinfunction "1_1") (pintype "passive"))
      (node (ref "C267") (pin "1") (pinfunction "1_1") (pintype "passive"))
      (node (ref "C268") (pin "1") (pinfunction "1_1") (pintype "passive"))
      (node (ref "C269") (pin "1") (pinfunction "1_1") (pintype "passive"))
      (node (ref "C270") (pin "1") (pinfunction "1_1") (pintype "passive"))
      (node (ref "C272") (pin "1") (pinfunction "1_1") (pintype "passive"))
      (node (ref "C273") (pin "1") (pinfunction "1_1") (pintype "passive"))
      (node (ref "C274") (pin "1") (pinfunction "1_1") (pintype "passive"))
      (node (ref "C275") (pin "1") (pinfunction "1_1") (pintype "passive"))
      (node (ref "C276") (pin "1") (pinfunction "1_1") (pintype "passive"))
      (node (ref "C277") (pin "1") (pinfunction "1_1") (pintype "passive"))
      (node (ref "C278") (pin "1") (pinfunction "1_1") (pintype "passive"))
      (node (ref "C279") (pin "1") (pinfunction "1_1") (pintype "passive"))
      (node (ref "C280") (pin "1") (pinfunction "1_1") (pintype "passive"))
      (node (ref "C281") (pin "1") (pinfunction "1_1") (pintype "passive"))
      (node (ref "J2") (pin "1") (pinfunction "1_1") (pintype "passive"))
      (node (ref "J6") (pin "2") (pinfunction "2_2") (pintype "passive"))
      (node (ref "Q1") (pin "5") (pinfunction "D_5") (pintype "passive"))
      (node (ref "Q1") (pin "6") (pinfunction "D_6") (pintype "passive"))
      (node (ref "Q1") (pin "7") (pinfunction "D_7") (pintype "passive"))
      (node (ref "Q1") (pin "8") (pinfunction "D_8") (pintype "passive"))
      (node (ref "Q4") (pin "5") (pinfunction "D_5") (pintype "passive"))
      (node (ref "Q4") (pin "6") (pinfunction "D_6") (pintype "passive"))
      (node (ref "Q4") (pin "7") (pinfunction "D_7") (pintype "passive"))
      (node (ref "Q4") (pin "8") (pinfunction "D_8") (pintype "passive"))
      (node (ref "R57") (pin "1") (pinfunction "1_1") (pintype "passive"))
      (node (ref "U20") (pin "1") (pinfunction "Vout_1") (pintype "passive"))
      (node (ref "U22") (pin "8") (pinfunction "INPUT_8") (pintype "passive"))
      (node (ref "U23") (pin "1") (pinfunction "Vout_1") (pintype "passive"))
    )
    (net (code "6") (name "/BOOT3") (class "Default")
      (node (ref "C312") (pin "1") (pinfunction "1_1") (pintype "passive"))
      (node (ref "D2") (pin "3") (pinfunction "CC_3") (pintype "passive"))
      (node (ref "U30") (pin "8") (pinfunction "BOOT_8") (pintype "passive"))
    )
    (net (code "7") (name "/BOOT4") (class "Default")
      (node (ref "C189") (pin "1") (pinfunction "1_1") (pintype "passive"))
      (node (ref "D1") (pin "3") (pinfunction "CC_3") (pintype "passive"))
      (node (ref "U25") (pin "8") (pinfunction "BOOT_8") (pintype "passive"))
    )
    (net (code "8") (name "/C1Rx") (class "Default")
      (node (ref "U1") (pin "58") (pinfunction "VCMPST1/RP96/RF0_58") (pintype "passive"))
      (node (ref "U21") (pin "4") (pinfunction "Rx_4") (pintype "passive"))
    )
    (net (code "9") (name "/C1Tx") (class "Default")
      (node (ref "U1") (pin "59") (pinfunction "VCMPST2/RP97/RF1_59") (pintype "passive"))
      (node (ref "U21") (pin "1") (pinfunction "Tx_1") (pintype "passive"))
    )
    (net (code "10") (name "/CAN5.0V") (class "Default")
      (node (ref "C255") (pin "1") (pinfunction "1_1") (pintype "passive"))
      (node (ref "R47") (pin "1") (pinfunction "1_1") (pintype "passive"))
      (node (ref "R64") (pin "1") (pinfunction "1_1") (pintype "passive"))
      (node (ref "U21") (pin "2") (pinfunction "GND_2") (pintype "passive"))
    )
    (net (code "11") (name "/CANH") (class "Default")
      (node (ref "J4") (pin "1") (pinfunction "1_1") (pintype "passive"))
      (node (ref "J5") (pin "2") (pinfunction "2_2") (pintype "passive"))
      (node (ref "U21") (pin "7") (pinfunction "CANH_7") (pintype "passive"))
    )
    (net (code "12") (name "/CANL") (class "Default")
      (node (ref "J5") (pin "1") (pinfunction "1_1") (pintype "passive"))
      (node (ref "R41") (pin "2") (pinfunction "2_2") (pintype "passive"))
      (node (ref "U21") (pin "6") (pinfunction "CANL_6") (pintype "passive"))
    )
    (net (code "13") (name "/CONFIG_N1") (class "Default")
      (node (ref "U1") (pin "42") (pinfunction "RTCC/DMLN/RPI72/RD8_42") (pintype "passive"))
      (node (ref "U2") (pin "2") (pinfunction "CONFIG_NI_2") (pintype "passive"))
    )
    (net (code "14") (name "/CONFIG_N2") (class "Default")
      (node (ref "U2") (pin "35") (pinfunction "CONFIG_NO_35") (pintype "passive"))
      (node (ref "U3") (pin "2") (pinfunction "CONFIG_NI_2") (pintype "passive"))
    )
    (net (code "15") (name "/CONFIG_N3") (class "Default")
      (node (ref "U3") (pin "35") (pinfunction "CONFIG_NO_35") (pintype "passive"))
      (node (ref "U4") (pin "2") (pinfunction "CONFIG_NI_2") (pintype "passive"))
    )
    (net (code "16") (name "/CONFIG_N4") (class "Default")
      (node (ref "U4") (pin "35") (pinfunction "CONFIG_NO_35") (pintype "passive"))
      (node (ref "U5") (pin "2") (pinfunction "CONFIG_NI_2") (pintype "passive"))
    )
    (net (code "17") (name "/CONFIG_N5") (class "Default")
      (node (ref "R21") (pin "1") (pinfunction "1_1") (pintype "passive"))
      (node (ref "R21") (pin "2") (pinfunction "2_2") (pintype "passive"))
      (node (ref "U5") (pin "35") (pinfunction "CONFIG_NO_35") (pintype "passive"))
      (node (ref "U7") (pin "2") (pinfunction "CONFIG_NI_2") (pintype "passive"))
    )
    (net (code "18") (name "/CONFIG_N6") (class "Default")
      (node (ref "U7") (pin "35") (pinfunction "CONFIG_NO_35") (pintype "passive"))
      (node (ref "U8") (pin "2") (pinfunction "CONFIG_NI_2") (pintype "passive"))
    )
    (net (code "19") (name "/CONFIG_N7") (class "Default")
      (node (ref "U8") (pin "35") (pinfunction "CONFIG_NO_35") (pintype "passive"))
      (node (ref "U9") (pin "2") (pinfunction "CONFIG_NI_2") (pintype "passive"))
    )
    (net (code "20") (name "/CONFIG_N8") (class "Default")
      (node (ref "U10") (pin "2") (pinfunction "CONFIG_NI_2") (pintype "passive"))
      (node (ref "U9") (pin "35") (pinfunction "CONFIG_NO_35") (pintype "passive"))
    )
    (net (code "21") (name "/CONFIG_N9") (class "Default")
      (node (ref "R25") (pin "2") (pinfunction "2_2") (pintype "passive"))
      (node (ref "U10") (pin "35") (pinfunction "CONFIG_NO_35") (pintype "passive"))
    )
    (net (code "22") (name "/CONFIG_N9I") (class "Default")
      (node (ref "R25") (pin "1") (pinfunction "1_1") (pintype "passive"))
      (node (ref "U1") (pin "54") (pinfunction "C3IN2-/RP70/RD6_54") (pintype "passive"))
      (node (ref "U11") (pin "2") (pinfunction "CONFIG_NI_2") (pintype "passive"))
    )
    (net (code "23") (name "/CONFIG_N10") (class "Default")
      (node (ref "U11") (pin "35") (pinfunction "CONFIG_NO_35") (pintype "passive"))
      (node (ref "U12") (pin "2") (pinfunction "CONFIG_NI_2") (pintype "passive"))
    )
    (net (code "24") (name "/CONFIG_N11") (class "Default")
      (node (ref "U12") (pin "35") (pinfunction "CONFIG_NO_35") (pintype "passive"))
      (node (ref "U13") (pin "2") (pinfunction "CONFIG_NI_2") (pintype "passive"))
    )
    (net (code "25") (name "/CONFIG_N12") (class "Default")
      (node (ref "U13") (pin "35") (pinfunction "CONFIG_NO_35") (pintype "passive"))
      (node (ref "U14") (pin "2") (pinfunction "CONFIG_NI_2") (pintype "passive"))
    )
    (net (code "26") (name "/CONFIG_N13") (class "Default")
      (node (ref "R29") (pin "1") (pinfunction "1_1") (pintype "passive"))
      (node (ref "R29") (pin "2") (pinfunction "2_2") (pintype "passive"))
      (node (ref "U14") (pin "35") (pinfunction "CONFIG_NO_35") (pintype "passive"))
      (node (ref "U15") (pin "2") (pinfunction "CONFIG_NI_2") (pintype "passive"))
    )
    (net (code "27") (name "/CONFIG_N14") (class "Default")
      (node (ref "U15") (pin "35") (pinfunction "CONFIG_NO_35") (pintype "passive"))
      (node (ref "U16") (pin "2") (pinfunction "CONFIG_NI_2") (pintype "passive"))
    )
    (net (code "28") (name "/CONFIG_N15") (class "Default")
      (node (ref "U16") (pin "35") (pinfunction "CONFIG_NO_35") (pintype "passive"))
      (node (ref "U17") (pin "2") (pinfunction "CONFIG_NI_2") (pintype "passive"))
    )
    (net (code "29") (name "/CONFIG_N16") (class "Default")
      (node (ref "U17") (pin "35") (pinfunction "CONFIG_NO_35") (pintype "passive"))
      (node (ref "U18") (pin "2") (pinfunction "CONFIG_NI_2") (pintype "passive"))
    )
    (net (code "30") (name "/CONFIG_N17") (class "Default")
      (node (ref "U18") (pin "35") (pinfunction "CONFIG_NO_35") (pintype "passive"))
    )
    (net (code "31") (name "/CONFIG_P1") (class "Default")
      (node (ref "U1") (pin "43") (pinfunction "ASDA1/DPLN/RPI73/RD9_43") (pintype "passive"))
      (node (ref "U2") (pin "1") (pinfunction "CONFIG_PI_1") (pintype "passive"))
    )
    (net (code "32") (name "/CONFIG_P2") (class "Default")
      (node (ref "U2") (pin "36") (pinfunction "CONFIG_PO_36") (pintype "passive"))
      (node (ref "U3") (pin "1") (pinfunction "CONFIG_PI_1") (pintype "passive"))
    )
    (net (code "33") (name "/CONFIG_P3") (class "Default")
      (node (ref "U3") (pin "36") (pinfunction "CONFIG_PO_36") (pintype "passive"))
      (node (ref "U4") (pin "1") (pinfunction "CONFIG_PI_1") (pintype "passive"))
    )
    (net (code "34") (name "/CONFIG_P4") (class "Default")
      (node (ref "U4") (pin "36") (pinfunction "CONFIG_PO_36") (pintype "passive"))
      (node (ref "U5") (pin "1") (pinfunction "CONFIG_PI_1") (pintype "passive"))
    )
    (net (code "35") (name "/CONFIG_P5") (class "Default")
      (node (ref "R20") (pin "1") (pinfunction "1_1") (pintype "passive"))
      (node (ref "R20") (pin "2") (pinfunction "2_2") (pintype "passive"))
      (node (ref "U5") (pin "36") (pinfunction "CONFIG_PO_36") (pintype "passive"))
      (node (ref "U7") (pin "1") (pinfunction "CONFIG_PI_1") (pintype "passive"))
    )
    (net (code "36") (name "/CONFIG_P6") (class "Default")
      (node (ref "U7") (pin "36") (pinfunction "CONFIG_PO_36") (pintype "passive"))
      (node (ref "U8") (pin "1") (pinfunction "CONFIG_PI_1") (pintype "passive"))
    )
    (net (code "37") (name "/CONFIG_P7") (class "Default")
      (node (ref "U8") (pin "36") (pinfunction "CONFIG_PO_36") (pintype "passive"))
      (node (ref "U9") (pin "1") (pinfunction "CONFIG_PI_1") (pintype "passive"))
    )
    (net (code "38") (name "/CONFIG_P8") (class "Default")
      (node (ref "U10") (pin "1") (pinfunction "CONFIG_PI_1") (pintype "passive"))
      (node (ref "U9") (pin "36") (pinfunction "CONFIG_PO_36") (pintype "passive"))
    )
    (net (code "39") (name "/CONFIG_P9") (class "Default")
      (node (ref "R24") (pin "2") (pinfunction "2_2") (pintype "passive"))
      (node (ref "U10") (pin "36") (pinfunction "CONFIG_PO_36") (pintype "passive"))
    )
    (net (code "40") (name "/CONFIG_P9I") (class "Default")
      (node (ref "R24") (pin "1") (pinfunction "1_1") (pintype "passive"))
      (node (ref "U1") (pin "55") (pinfunction "C3IN1+/VCMPST3/RP71/RD7_55") (pintype "passive"))
      (node (ref "U11") (pin "1") (pinfunction "CONFIG_PI_1") (pintype "passive"))
    )
    (net (code "41") (name "/CONFIG_P10") (class "Default")
      (node (ref "U11") (pin "36") (pinfunction "CONFIG_PO_36") (pintype "passive"))
      (node (ref "U12") (pin "1") (pinfunction "CONFIG_PI_1") (pintype "passive"))
    )
    (net (code "42") (name "/CONFIG_P11") (class "Default")
      (node (ref "U12") (pin "36") (pinfunction "CONFIG_PO_36") (pintype "passive"))
      (node (ref "U13") (pin "1") (pinfunction "CONFIG_PI_1") (pintype "passive"))
    )
    (net (code "43") (name "/CONFIG_P12") (class "Default")
      (node (ref "U13") (pin "36") (pinfunction "CONFIG_PO_36") (pintype "passive"))
      (node (ref "U14") (pin "1") (pinfunction "CONFIG_PI_1") (pintype "passive"))
    )
    (net (code "44") (name "/CONFIG_P13") (class "Default")
      (node (ref "R28") (pin "1") (pinfunction "1_1") (pintype "passive"))
      (node (ref "R28") (pin "2") (pinfunction "2_2") (pintype "passive"))
      (node (ref "U14") (pin "36") (pinfunction "CONFIG_PO_36") (pintype "passive"))
      (node (ref "U15") (pin "1") (pinfunction "CONFIG_PI_1") (pintype "passive"))
    )
    (net (code "45") (name "/CONFIG_P14") (class "Default")
      (node (ref "U15") (pin "36") (pinfunction "CONFIG_PO_36") (pintype "passive"))
      (node (ref "U16") (pin "1") (pinfunction "CONFIG_PI_1") (pintype "passive"))
    )
    (net (code "46") (name "/CONFIG_P15") (class "Default")
      (node (ref "U16") (pin "36") (pinfunction "CONFIG_PO_36") (pintype "passive"))
      (node (ref "U17") (pin "1") (pinfunction "CONFIG_PI_1") (pintype "passive"))
    )
    (net (code "47") (name "/CONFIG_P16") (class "Default")
      (node (ref "U17") (pin "36") (pinfunction "CONFIG_PO_36") (pintype "passive"))
      (node (ref "U18") (pin "1") (pinfunction "CONFIG_PI_1") (pintype "passive"))
    )
    (net (code "48") (name "/CONFIG_P17") (class "Default")
      (node (ref "U18") (pin "36") (pinfunction "CONFIG_PO_36") (pintype "passive"))
    )
    (net (code "49") (name "/CSN4") (class "Default")
      (node (ref "R38") (pin "1") (pinfunction "1_1") (pintype "passive"))
      (node (ref "U1") (pin "14") (pinfunction "AN2/C2IN2-/VMIO/RPI34/RB2_14") (pintype "passive"))
    )
    (net (code "50") (name "/CSP4") (class "Default")
      (node (ref "R37") (pin "1") (pinfunction "1_1") (pintype "passive"))
      (node (ref "U1") (pin "13") (pinfunction "AN3/C2IN1+/VPIO/RPI35/RB3_13") (pintype "passive"))
    )
    (net (code "51") (name "/C_CLK_OUT1") (class "Default")
      (node (ref "U2") (pin "44") (pinfunction "CORE_CLKOUT_44") (pintype "passive"))
    )
    (net (code "52") (name "/C_CLK_OUT2") (class "Default")
      (node (ref "U3") (pin "44") (pinfunction "CORE_CLKOUT_44") (pintype "passive"))
    )
    (net (code "53") (name "/C_CLK_OUT3") (class "Default")
      (node (ref "U4") (pin "44") (pinfunction "CORE_CLKOUT_44") (pintype "passive"))
    )
    (net (code "54") (name "/C_CLK_OUT4") (class "Default")
      (node (ref "U5") (pin "44") (pinfunction "CORE_CLKOUT_44") (pintype "passive"))
    )
    (net (code "55") (name "/C_CLK_OUT5") (class "Default")
      (node (ref "U7") (pin "44") (pinfunction "CORE_CLKOUT_44") (pintype "passive"))
    )
    (net (code "56") (name "/C_CLK_OUT6") (class "Default")
      (node (ref "U8") (pin "44") (pinfunction "CORE_CLKOUT_44") (pintype "passive"))
    )
    (net (code "57") (name "/C_CLK_OUT7") (class "Default")
      (node (ref "U9") (pin "44") (pinfunction "CORE_CLKOUT_44") (pintype "passive"))
    )
    (net (code "58") (name "/C_CLK_OUT8") (class "Default")
      (node (ref "U10") (pin "44") (pinfunction "CORE_CLKOUT_44") (pintype "passive"))
    )
    (net (code "59") (name "/C_CLK_OUT9") (class "Default")
      (node (ref "U11") (pin "44") (pinfunction "CORE_CLKOUT_44") (pintype "passive"))
    )
    (net (code "60") (name "/C_CLK_OUT10") (class "Default")
      (node (ref "U12") (pin "44") (pinfunction "CORE_CLKOUT_44") (pintype "passive"))
    )
    (net (code "61") (name "/C_CLK_OUT11") (class "Default")
      (node (ref "U13") (pin "44") (pinfunction "CORE_CLKOUT_44") (pintype "passive"))
    )
    (net (code "62") (name "/C_CLK_OUT12") (class "Default")
      (node (ref "U14") (pin "44") (pinfunction "CORE_CLKOUT_44") (pintype "passive"))
    )
    (net (code "63") (name "/C_CLK_OUT13") (class "Default")
      (node (ref "U15") (pin "44") (pinfunction "CORE_CLKOUT_44") (pintype "passive"))
    )
    (net (code "64") (name "/C_CLK_OUT14") (class "Default")
      (node (ref "U16") (pin "44") (pinfunction "CORE_CLKOUT_44") (pintype "passive"))
    )
    (net (code "65") (name "/C_CLK_OUT15") (class "Default")
      (node (ref "U17") (pin "44") (pinfunction "CORE_CLKOUT_44") (pintype "passive"))
    )
    (net (code "66") (name "/C_CLK_OUT16") (class "Default")
      (node (ref "U18") (pin "44") (pinfunction "CORE_CLKOUT_44") (pintype "passive"))
    )
    (net (code "67") (name "/D+") (class "Default")
      (node (ref "C254") (pin "2") (pinfunction "2_2") (pintype "passive"))
      (node (ref "R35") (pin "2") (pinfunction "2_2") (pintype "passive"))
      (node (ref "U1") (pin "37") (pinfunction "D+/RG2_37") (pintype "passive"))
    )
    (net (code "68") (name "/D-") (class "Default")
      (node (ref "C253") (pin "2") (pinfunction "2_2") (pintype "passive"))
      (node (ref "R34") (pin "2") (pinfunction "2_2") (pintype "passive"))
      (node (ref "U1") (pin "36") (pinfunction "D-/RG3_36") (pintype "passive"))
    )
    (net (code "69") (name "/DBG_N1") (class "Default")
      (node (ref "U2") (pin "30") (pinfunction "DBG0_30") (pintype "passive"))
    )
    (net (code "70") (name "/DBG_N2") (class "Default")
      (node (ref "U3") (pin "30") (pinfunction "DBG0_30") (pintype "passive"))
    )
    (net (code "71") (name "/DBG_N3") (class "Default")
      (node (ref "U4") (pin "30") (pinfunction "DBG0_30") (pintype "passive"))
    )
    (net (code "72") (name "/DBG_N4") (class "Default")
      (node (ref "U5") (pin "30") (pinfunction "DBG0_30") (pintype "passive"))
    )
    (net (code "73") (name "/DBG_N5") (class "Default")
      (node (ref "U7") (pin "30") (pinfunction "DBG0_30") (pintype "passive"))
    )
    (net (code "74") (name "/DBG_N6") (class "Default")
      (node (ref "U8") (pin "30") (pinfunction "DBG0_30") (pintype "passive"))
    )
    (net (code "75") (name "/DBG_N7") (class "Default")
      (node (ref "U9") (pin "30") (pinfunction "DBG0_30") (pintype "passive"))
    )
    (net (code "76") (name "/DBG_N8") (class "Default")
      (node (ref "U10") (pin "30") (pinfunction "DBG0_30") (pintype "passive"))
    )
    (net (code "77") (name "/DBG_N9") (class "Default")
      (node (ref "U11") (pin "30") (pinfunction "DBG0_30") (pintype "passive"))
    )
    (net (code "78") (name "/DBG_N10") (class "Default")
      (node (ref "U12") (pin "30") (pinfunction "DBG0_30") (pintype "passive"))
    )
    (net (code "79") (name "/DBG_N11") (class "Default")
      (node (ref "U13") (pin "30") (pinfunction "DBG0_30") (pintype "passive"))
    )
    (net (code "80") (name "/DBG_N12") (class "Default")
      (node (ref "U14") (pin "30") (pinfunction "DBG0_30") (pintype "passive"))
    )
    (net (code "81") (name "/DBG_N13") (class "Default")
      (node (ref "U15") (pin "30") (pinfunction "DBG0_30") (pintype "passive"))
    )
    (net (code "82") (name "/DBG_N14") (class "Default")
      (node (ref "U16") (pin "30") (pinfunction "DBG0_30") (pintype "passive"))
    )
    (net (code "83") (name "/DBG_N15") (class "Default")
      (node (ref "U17") (pin "30") (pinfunction "DBG0_30") (pintype "passive"))
    )
    (net (code "84") (name "/DBG_N16") (class "Default")
      (node (ref "U18") (pin "30") (pinfunction "DBG0_30") (pintype "passive"))
    )
    (net (code "85") (name "/DBG_P1") (class "Default")
      (node (ref "U2") (pin "29") (pinfunction "DBG1_29") (pintype "passive"))
    )
    (net (code "86") (name "/DBG_P2") (class "Default")
      (node (ref "U3") (pin "29") (pinfunction "DBG1_29") (pintype "passive"))
    )
    (net (code "87") (name "/DBG_P3") (class "Default")
      (node (ref "U4") (pin "29") (pinfunction "DBG1_29") (pintype "passive"))
    )
    (net (code "88") (name "/DBG_P4") (class "Default")
      (node (ref "U5") (pin "29") (pinfunction "DBG1_29") (pintype "passive"))
    )
    (net (code "89") (name "/DBG_P5") (class "Default")
      (node (ref "U7") (pin "29") (pinfunction "DBG1_29") (pintype "passive"))
    )
    (net (code "90") (name "/DBG_P6") (class "Default")
      (node (ref "U8") (pin "29") (pinfunction "DBG1_29") (pintype "passive"))
    )
    (net (code "91") (name "/DBG_P7") (class "Default")
      (node (ref "U9") (pin "29") (pinfunction "DBG1_29") (pintype "passive"))
    )
    (net (code "92") (name "/DBG_P8") (class "Default")
      (node (ref "U10") (pin "29") (pinfunction "DBG1_29") (pintype "passive"))
    )
    (net (code "93") (name "/DBG_P9") (class "Default")
      (node (ref "U11") (pin "29") (pinfunction "DBG1_29") (pintype "passive"))
    )
    (net (code "94") (name "/DBG_P10") (class "Default")
      (node (ref "U12") (pin "29") (pinfunction "DBG1_29") (pintype "passive"))
    )
    (net (code "95") (name "/DBG_P11") (class "Default")
      (node (ref "U13") (pin "29") (pinfunction "DBG1_29") (pintype "passive"))
    )
    (net (code "96") (name "/DBG_P12") (class "Default")
      (node (ref "U14") (pin "29") (pinfunction "DBG1_29") (pintype "passive"))
    )
    (net (code "97") (name "/DBG_P13") (class "Default")
      (node (ref "U15") (pin "29") (pinfunction "DBG1_29") (pintype "passive"))
    )
    (net (code "98") (name "/DBG_P14") (class "Default")
      (node (ref "U16") (pin "29") (pinfunction "DBG1_29") (pintype "passive"))
    )
    (net (code "99") (name "/DBG_P15") (class "Default")
      (node (ref "U17") (pin "29") (pinfunction "DBG1_29") (pintype "passive"))
    )
    (net (code "100") (name "/DBG_P16") (class "Default")
      (node (ref "U18") (pin "29") (pinfunction "DBG1_29") (pintype "passive"))
    )
    (net (code "101") (name "/FAN5.0V") (class "Default")
      (node (ref "R63") (pin "2") (pinfunction "2_2") (pintype "passive"))
      (node (ref "R64") (pin "2") (pinfunction "2_2") (pintype "passive"))
    )
    (net (code "102") (name "/FB") (class "Default")
      (node (ref "C251") (pin "1") (pinfunction "1_1") (pintype "passive"))
      (node (ref "R43") (pin "1") (pinfunction "1_1") (pintype "passive"))
      (node (ref "U1") (pin "17") (pinfunction "PGEC1/AN6/RPI38/RB6_17") (pintype "passive"))
    )
    (net (code "103") (name "/GREEN") (class "Default")
      (node (ref "D5") (pin "2") (pinfunction "A_2") (pintype "passive"))
      (node (ref "U1") (pin "62") (pinfunction "AN26/PWM2L/PMD2/RP82/RE2_62") (pintype "passive"))
    )
    (net (code "104") (name "/HO3") (class "Default")
      (node (ref "Q4") (pin "4") (pinfunction "G_4") (pintype "passive"))
      (node (ref "U30") (pin "1") (pinfunction "HO_1") (pintype "passive"))
    )
    (net (code "105") (name "/HO4") (class "Default")
      (node (ref "Q1") (pin "4") (pinfunction "G_4") (pintype "passive"))
      (node (ref "U25") (pin "1") (pinfunction "HO_1") (pintype "passive"))
    )
    (net (code "106") (name "/LDO5.0V") (class "Default")
      (node (ref "C187") (pin "1") (pinfunction "1_1") (pintype "passive"))
      (node (ref "R46") (pin "1") (pinfunction "1_1") (pintype "passive"))
      (node (ref "R47") (pin "2") (pinfunction "2_2") (pintype "passive"))
      (node (ref "R62") (pin "2") (pinfunction "2_2") (pintype "passive"))
      (node (ref "U19") (pin "5") (pinfunction "N.C._5") (pintype "passive"))
      (node (ref "U19") (pin "8") (pinfunction "INPUT_8") (pintype "passive"))
      (node (ref "U6") (pin "1") (pinfunction "Vin_1") (pintype "passive"))
      (node (ref "U6") (pin "3") (pinfunction "STBY_3") (pintype "passive"))
    )
    (net (code "107") (name "/LMGND") (class "Default")
      (node (ref "D3") (pin "3") (pinfunction "CC_3") (pintype "passive"))
      (node (ref "R60") (pin "2") (pinfunction "2_2") (pintype "passive"))
      (node (ref "U20") (pin "2") (pinfunction "GND_2") (pintype "passive"))
      (node (ref "U22") (pin "2") (pinfunction "GND_2") (pintype "passive"))
      (node (ref "U22") (pin "3") (pinfunction "GND_3") (pintype "passive"))
      (node (ref "U22") (pin "4") (pinfunction "N.C._4") (pintype "passive"))
      (node (ref "U22") (pin "5") (pinfunction "N.C._5") (pintype "passive"))
      (node (ref "U22") (pin "6") (pinfunction "GND_6") (pintype "passive"))
      (node (ref "U22") (pin "7") (pinfunction "GND_7") (pintype "passive"))
      (node (ref "U23") (pin "2") (pinfunction "GND_2") (pintype "passive"))
    )
    (net (code "108") (name "/LO3") (class "Default")
      (node (ref "Q5") (pin "4") (pinfunction "G_4") (pintype "passive"))
      (node (ref "Q6") (pin "4") (pinfunction "G_4") (pintype "passive"))
      (node (ref "U30") (pin "3") (pinfunction "LO_3") (pintype "passive"))
    )
    (net (code "109") (name "/LO4") (class "Default")
      (node (ref "Q2") (pin "4") (pinfunction "G_4") (pintype "passive"))
      (node (ref "Q3") (pin "4") (pinfunction "G_4") (pintype "passive"))
      (node (ref "U25") (pin "3") (pinfunction "LO_3") (pintype "passive"))
    )
    (net (code "110") (name "/MCLR") (class "Default")
      (node (ref "C72") (pin "1") (pinfunction "1_1") (pintype "passive"))
      (node (ref "J1") (pin "1") (pinfunction "1_1") (pintype "passive"))
      (node (ref "R9") (pin "1") (pinfunction "1_1") (pintype "passive"))
      (node (ref "U1") (pin "7") (pinfunction "MCLR_7") (pintype "passive"))
    )
    (net (code "111") (name "/MEAS12") (class "Default")
      (node (ref "C325") (pin "1") (pinfunction "1_1") (pintype "passive"))
      (node (ref "R57") (pin "2") (pinfunction "2_2") (pintype "passive"))
      (node (ref "R61") (pin "2") (pinfunction "2_2") (pintype "passive"))
      (node (ref "U1") (pin "18") (pinfunction "PGED1/AN7/RCV/RPI39/RB7_18") (pintype "passive"))
    )
    (net (code "112") (name "/Main OSC In") (class "Default")
      (node (ref "C85") (pin "1") (pinfunction "1_1") (pintype "passive"))
      (node (ref "U1") (pin "39") (pinfunction "OSC1/RPI60/RC12_39") (pintype "passive"))
      (node (ref "Y1") (pin "1") (pinfunction "1_1") (pintype "passive"))
    )
    (net (code "113") (name "/Main OSC Out") (class "Default")
      (node (ref "C86") (pin "1") (pinfunction "1_1") (pintype "passive"))
      (node (ref "U1") (pin "40") (pinfunction "OSC2/CLKO/RC15_40") (pintype "passive"))
      (node (ref "Y1") (pin "2") (pinfunction "2_2") (pintype "passive"))
    )
    (net (code "114") (name "/ORANGE") (class "Default")
      (node (ref "D7") (pin "2") (pinfunction "A_2") (pintype "passive"))
      (node (ref "U1") (pin "45") (pinfunction "PMCS1/RPI75/RD11_45") (pintype "passive"))
    )
    (net (code "115") (name "/PGC") (class "Default")
      (node (ref "J1") (pin "5") (pinfunction "5_5") (pintype "passive"))
      (node (ref "U1") (pin "15") (pinfunction "PGEC3/AN1/VREF-/RPI33/RB1_15") (pintype "passive"))
    )
    (net (code "116") (name "/PGD") (class "Default")
      (node (ref "J1") (pin "4") (pinfunction "4_4") (pintype "passive"))
      (node (ref "U1") (pin "16") (pinfunction "PGED3/AN0/VREF+/RPI32/RB0_16") (pintype "passive"))
    )
    (net (code "117") (name "/PWM") (class "Default")
      (node (ref "J6") (pin "4") (pinfunction "4_4") (pintype "passive"))
      (node (ref "U1") (pin "61") (pinfunction "AN25/PWM1H/PMD1/RPI81/RE1_61") (pintype "passive"))
    )
    (net (code "118") (name "/PWM3H") (class "Default")
      (node (ref "R59") (pin "2") (pinfunction "2_2") (pintype "passive"))
      (node (ref "U1") (pin "1") (pinfunction "AN29/PWM3H/PMD5/RP85/RE5_1") (pintype "passive"))
      (node (ref "U30") (pin "5") (pinfunction "IN_5") (pintype "passive"))
    )
    (net (code "119") (name "/PWM3L") (class "Default")
      (node (ref "U1") (pin "64") (pinfunction "AN28/PWM3L/PMD4/RP84/RE4_64") (pintype "passive"))
    )
    (net (code "120") (name "/PWM4H") (class "Default")
      (node (ref "R40") (pin "2") (pinfunction "2_2") (pintype "passive"))
      (node (ref "U1") (pin "3") (pinfunction "AN31/PWM4H/PMD7/RP87/RE7_3") (pintype "passive"))
      (node (ref "U25") (pin "5") (pinfunction "IN_5") (pintype "passive"))
    )
    (net (code "121") (name "/PWM4L") (class "Default")
      (node (ref "U1") (pin "2") (pinfunction "AN30/PWM4L/PMD6/RPI86/RE6_2") (pintype "passive"))
    )
    (net (code "122") (name "/RED") (class "Default")
      (node (ref "D4") (pin "2") (pinfunction "A_2") (pintype "passive"))
      (node (ref "U1") (pin "63") (pinfunction "AN27/PWM2H/PMD3/RPI83/RE3_63") (pintype "passive"))
    )
    (net (code "123") (name "/REPORT_N1-4") (class "Default")
      (node (ref "R18") (pin "2") (pinfunction "2_2") (pintype "passive"))
      (node (ref "R22") (pin "2") (pinfunction "2_2") (pintype "passive"))
      (node (ref "R50") (pin "2") (pinfunction "2_2") (pintype "passive"))
      (node (ref "U1") (pin "48") (pinfunction "PGEC2/SOSCO/C3IN1-/T1CK/RPI62/RC14_48") (pintype "passive"))
      (node (ref "U2") (pin "17") (pinfunction "REPORT_N_17") (pintype "passive"))
      (node (ref "U3") (pin "17") (pinfunction "REPORT_N_17") (pintype "passive"))
      (node (ref "U4") (pin "17") (pinfunction "REPORT_N_17") (pintype "passive"))
      (node (ref "U5") (pin "17") (pinfunction "REPORT_N_17") (pintype "passive"))
    )
    (net (code "124") (name "/REPORT_N5-8") (class "Default")
      (node (ref "R18") (pin "1") (pinfunction "1_1") (pintype "passive"))
      (node (ref "R49") (pin "2") (pinfunction "2_2") (pintype "passive"))
      (node (ref "U1") (pin "50") (pinfunction "DPH/RP66/RD2_50") (pintype "passive"))
      (node (ref "U10") (pin "17") (pinfunction "REPORT_N_17") (pintype "passive"))
      (node (ref "U7") (pin "17") (pinfunction "REPORT_N_17") (pintype "passive"))
      (node (ref "U8") (pin "17") (pinfunction "REPORT_N_17") (pintype "passive"))
      (node (ref "U9") (pin "17") (pinfunction "REPORT_N_17") (pintype "passive"))
    )
    (net (code "125") (name "/REPORT_N9-12") (class "Default")
      (node (ref "R26") (pin "2") (pinfunction "2_2") (pintype "passive"))
      (node (ref "R55") (pin "1") (pinfunction "1_1") (pintype "passive"))
      (node (ref "U1") (pin "30") (pinfunction "AN15/PMA0/RPI47/RB15_30") (pintype "passive"))
      (node (ref "U11") (pin "17") (pinfunction "REPORT_N_17") (pintype "passive"))
      (node (ref "U12") (pin "17") (pinfunction "REPORT_N_17") (pintype "passive"))
      (node (ref "U13") (pin "17") (pinfunction "REPORT_N_17") (pintype "passive"))
      (node (ref "U14") (pin "17") (pinfunction "REPORT_N_17") (pintype "passive"))
    )
    (net (code "126") (name "/REPORT_N13-16") (class "Default")
      (node (ref "R22") (pin "1") (pinfunction "1_1") (pintype "passive"))
      (node (ref "R26") (pin "1") (pinfunction "1_1") (pintype "passive"))
      (node (ref "R54") (pin "1") (pinfunction "1_1") (pintype "passive"))
      (node (ref "U1") (pin "29") (pinfunction "AN14/PMA1/RPI46/RB14_29") (pintype "passive"))
      (node (ref "U15") (pin "17") (pinfunction "REPORT_N_17") (pintype "passive"))
      (node (ref "U16") (pin "17") (pinfunction "REPORT_N_17") (pintype "passive"))
      (node (ref "U17") (pin "17") (pinfunction "REPORT_N_17") (pintype "passive"))
      (node (ref "U18") (pin "17") (pinfunction "REPORT_N_17") (pintype "passive"))
    )
    (net (code "127") (name "/REPORT_P1-4") (class "Default")
      (node (ref "R19") (pin "2") (pinfunction "2_2") (pintype "passive"))
      (node (ref "R23") (pin "2") (pinfunction "2_2") (pintype "passive"))
      (node (ref "R51") (pin "2") (pinfunction "2_2") (pintype "passive"))
      (node (ref "U1") (pin "47") (pinfunction "PGED2/SOSCI/C3IN3-/RPI61/RC13_47") (pintype "passive"))
      (node (ref "U2") (pin "18") (pinfunction "REPORT_P_18") (pintype "passive"))
      (node (ref "U3") (pin "18") (pinfunction "REPORT_P_18") (pintype "passive"))
      (node (ref "U4") (pin "18") (pinfunction "REPORT_P_18") (pintype "passive"))
      (node (ref "U5") (pin "18") (pinfunction "REPORT_P_18") (pintype "passive"))
    )
    (net (code "128") (name "/REPORT_P5-8") (class "Default")
      (node (ref "R19") (pin "1") (pinfunction "1_1") (pintype "passive"))
      (node (ref "R48") (pin "2") (pinfunction "2_2") (pintype "passive"))
      (node (ref "U1") (pin "51") (pinfunction "PMBE/RP67/RD3_51") (pintype "passive"))
      (node (ref "U10") (pin "18") (pinfunction "REPORT_P_18") (pintype "passive"))
      (node (ref "U7") (pin "18") (pinfunction "REPORT_P_18") (pintype "passive"))
      (node (ref "U8") (pin "18") (pinfunction "REPORT_P_18") (pintype "passive"))
      (node (ref "U9") (pin "18") (pinfunction "REPORT_P_18") (pintype "passive"))
    )
    (net (code "129") (name "/REPORT_P9-12") (class "Default")
      (node (ref "R27") (pin "2") (pinfunction "2_2") (pintype "passive"))
      (node (ref "R53") (pin "1") (pinfunction "1_1") (pintype "passive"))
      (node (ref "U1") (pin "28") (pinfunction "TDI/AN13/PMA10/RPI45/RB13_28") (pintype "passive"))
      (node (ref "U11") (pin "18") (pinfunction "REPORT_P_18") (pintype "passive"))
      (node (ref "U12") (pin "18") (pinfunction "REPORT_P_18") (pintype "passive"))
      (node (ref "U13") (pin "18") (pinfunction "REPORT_P_18") (pintype "passive"))
      (node (ref "U14") (pin "18") (pinfunction "REPORT_P_18") (pintype "passive"))
    )
    (net (code "130") (name "/REPORT_P13-16") (class "Default")
      (node (ref "R23") (pin "1") (pinfunction "1_1") (pintype "passive"))
      (node (ref "R27") (pin "1") (pinfunction "1_1") (pintype "passive"))
      (node (ref "R52") (pin "1") (pinfunction "1_1") (pintype "passive"))
      (node (ref "U1") (pin "27") (pinfunction "TCK/AN12/PMA11/RPI44/RB12_27") (pintype "passive"))
      (node (ref "U15") (pin "18") (pinfunction "REPORT_P_18") (pintype "passive"))
      (node (ref "U16") (pin "18") (pinfunction "REPORT_P_18") (pintype "passive"))
      (node (ref "U17") (pin "18") (pinfunction "REPORT_P_18") (pintype "passive"))
      (node (ref "U18") (pin "18") (pinfunction "REPORT_P_18") (pintype "passive"))
    )
    (net (code "131") (name "/RESET1") (class "Default")
      (node (ref "C1") (pin "1") (pinfunction "1_1") (pintype "passive"))
      (node (ref "R1") (pin "2") (pinfunction "2_2") (pintype "passive"))
      (node (ref "U2") (pin "45") (pinfunction "RSTN_45") (pintype "passive"))
    )
    (net (code "132") (name "/RESET2") (class "Default")
      (node (ref "C2") (pin "1") (pinfunction "1_1") (pintype "passive"))
      (node (ref "R2") (pin "2") (pinfunction "2_2") (pintype "passive"))
      (node (ref "U3") (pin "45") (pinfunction "RSTN_45") (pintype "passive"))
    )
    (net (code "133") (name "/RESET3") (class "Default")
      (node (ref "C3") (pin "1") (pinfunction "1_1") (pintype "passive"))
      (node (ref "R3") (pin "2") (pinfunction "2_2") (pintype "passive"))
      (node (ref "U4") (pin "45") (pinfunction "RSTN_45") (pintype "passive"))
    )
    (net (code "134") (name "/RESET4") (class "Default")
      (node (ref "C4") (pin "1") (pinfunction "1_1") (pintype "passive"))
      (node (ref "R4") (pin "2") (pinfunction "2_2") (pintype "passive"))
      (node (ref "U5") (pin "45") (pinfunction "RSTN_45") (pintype "passive"))
    )
    (net (code "135") (name "/RESET5") (class "Default")
      (node (ref "C47") (pin "1") (pinfunction "1_1") (pintype "passive"))
      (node (ref "R5") (pin "2") (pinfunction "2_2") (pintype "passive"))
      (node (ref "U7") (pin "45") (pinfunction "RSTN_45") (pintype "passive"))
    )
    (net (code "136") (name "/RESET6") (class "Default")
      (node (ref "C48") (pin "1") (pinfunction "1_1") (pintype "passive"))
      (node (ref "R6") (pin "2") (pinfunction "2_2") (pintype "passive"))
      (node (ref "U8") (pin "45") (pinfunction "RSTN_45") (pintype "passive"))
    )
    (net (code "137") (name "/RESET7") (class "Default")
      (node (ref "C49") (pin "1") (pinfunction "1_1") (pintype "passive"))
      (node (ref "R7") (pin "2") (pinfunction "2_2") (pintype "passive"))
      (node (ref "U9") (pin "45") (pinfunction "RSTN_45") (pintype "passive"))
    )
    (net (code "138") (name "/RESET8") (class "Default")
      (node (ref "C50") (pin "1") (pinfunction "1_1") (pintype "passive"))
      (node (ref "R8") (pin "2") (pinfunction "2_2") (pintype "passive"))
      (node (ref "U10") (pin "45") (pinfunction "RSTN_45") (pintype "passive"))
    )
    (net (code "139") (name "/RESET9") (class "Default")
      (node (ref "C99") (pin "1") (pinfunction "1_1") (pintype "passive"))
      (node (ref "R10") (pin "2") (pinfunction "2_2") (pintype "passive"))
      (node (ref "U11") (pin "45") (pinfunction "RSTN_45") (pintype "passive"))
    )
    (net (code "140") (name "/RESET10") (class "Default")
      (node (ref "C100") (pin "1") (pinfunction "1_1") (pintype "passive"))
      (node (ref "R11") (pin "2") (pinfunction "2_2") (pintype "passive"))
      (node (ref "U12") (pin "45") (pinfunction "RSTN_45") (pintype "passive"))
    )
    (net (code "141") (name "/RESET11") (class "Default")
      (node (ref "C101") (pin "1") (pinfunction "1_1") (pintype "passive"))
      (node (ref "R12") (pin "2") (pinfunction "2_2") (pintype "passive"))
      (node (ref "U13") (pin "45") (pinfunction "RSTN_45") (pintype "passive"))
    )
    (net (code "142") (name "/RESET12") (class "Default")
      (node (ref "C102") (pin "1") (pinfunction "1_1") (pintype "passive"))
      (node (ref "R13") (pin "2") (pinfunction "2_2") (pintype "passive"))
      (node (ref "U14") (pin "45") (pinfunction "RSTN_45") (pintype "passive"))
    )
    (net (code "143") (name "/RESET13") (class "Default")
      (node (ref "C143") (pin "1") (pinfunction "1_1") (pintype "passive"))
      (node (ref "R14") (pin "2") (pinfunction "2_2") (pintype "passive"))
      (node (ref "U15") (pin "45") (pinfunction "RSTN_45") (pintype "passive"))
    )
    (net (code "144") (name "/RESET14") (class "Default")
      (node (ref "C144") (pin "1") (pinfunction "1_1") (pintype "passive"))
      (node (ref "R15") (pin "2") (pinfunction "2_2") (pintype "passive"))
      (node (ref "U16") (pin "45") (pinfunction "RSTN_45") (pintype "passive"))
    )
    (net (code "145") (name "/RESET15") (class "Default")
      (node (ref "C145") (pin "1") (pinfunction "1_1") (pintype "passive"))
      (node (ref "R16") (pin "2") (pinfunction "2_2") (pintype "passive"))
      (node (ref "U17") (pin "45") (pinfunction "RSTN_45") (pintype "passive"))
    )
    (net (code "146") (name "/RESET16") (class "Default")
      (node (ref "C146") (pin "1") (pinfunction "1_1") (pintype "passive"))
      (node (ref "R17") (pin "2") (pinfunction "2_2") (pintype "passive"))
      (node (ref "U18") (pin "45") (pinfunction "RSTN_45") (pintype "passive"))
    )
    (net (code "147") (name "/RPM") (class "Default")
      (node (ref "R44") (pin "1") (pinfunction "1_1") (pintype "passive"))
      (node (ref "R45") (pin "2") (pinfunction "2_2") (pintype "passive"))
      (node (ref "U1") (pin "60") (pinfunction "AN24/PWM1L/PMD0/RP80/RE0_60") (pintype "passive"))
    )
    (net (code "148") (name "/RPMF") (class "Default")
      (node (ref "J6") (pin "3") (pinfunction "3_3") (pintype "passive"))
      (node (ref "R44") (pin "2") (pinfunction "2_2") (pintype "passive"))
    )
    (net (code "149") (name "/SWN3") (class "Default")
      (node (ref "C310") (pin "1") (pinfunction "1_1") (pintype "passive"))
      (node (ref "C312") (pin "2") (pinfunction "2_2") (pintype "passive"))
      (node (ref "L2") (pin "1") (pinfunction "1_1") (pintype "passive"))
      (node (ref "Q4") (pin "1") (pinfunction "S_1") (pintype "passive"))
      (node (ref "Q4") (pin "2") (pinfunction "S_2") (pintype "passive"))
      (node (ref "Q4") (pin "3") (pinfunction "S_3") (pintype "passive"))
      (node (ref "Q5") (pin "5") (pinfunction "D_5") (pintype "passive"))
      (node (ref "Q5") (pin "6") (pinfunction "D_6") (pintype "passive"))
      (node (ref "Q5") (pin "7") (pinfunction "D_7") (pintype "passive"))
      (node (ref "Q5") (pin "8") (pinfunction "D_8") (pintype "passive"))
      (node (ref "Q6") (pin "5") (pinfunction "D_5") (pintype "passive"))
      (node (ref "Q6") (pin "6") (pinfunction "D_6") (pintype "passive"))
      (node (ref "Q6") (pin "7") (pinfunction "D_7") (pintype "passive"))
      (node (ref "Q6") (pin "8") (pinfunction "D_8") (pintype "passive"))
      (node (ref "U30") (pin "2") (pinfunction "SW_2") (pintype "passive"))
    )
    (net (code "150") (name "/SWN4") (class "Default")
      (node (ref "C189") (pin "2") (pinfunction "2_2") (pintype "passive"))
      (node (ref "C206") (pin "1") (pinfunction "1_1") (pintype "passive"))
      (node (ref "L1") (pin "1") (pinfunction "1_1") (pintype "passive"))
      (node (ref "Q1") (pin "1") (pinfunction "S_1") (pintype "passive"))
      (node (ref "Q1") (pin "2") (pinfunction "S_2") (pintype "passive"))
      (node (ref "Q1") (pin "3") (pinfunction "S_3") (pintype "passive"))
      (node (ref "Q2") (pin "5") (pinfunction "D_5") (pintype "passive"))
      (node (ref "Q2") (pin "6") (pinfunction "D_6") (pintype "passive"))
      (node (ref "Q2") (pin "7") (pinfunction "D_7") (pintype "passive"))
      (node (ref "Q2") (pin "8") (pinfunction "D_8") (pintype "passive"))
      (node (ref "Q3") (pin "5") (pinfunction "D_5") (pintype "passive"))
      (node (ref "Q3") (pin "6") (pinfunction "D_6") (pintype "passive"))
      (node (ref "Q3") (pin "7") (pinfunction "D_7") (pintype "passive"))
      (node (ref "Q3") (pin "8") (pinfunction "D_8") (pintype "passive"))
      (node (ref "R36") (pin "2") (pinfunction "2_2") (pintype "passive"))
      (node (ref "U25") (pin "2") (pinfunction "SW_2") (pintype "passive"))
    )
    (net (code "151") (name "/U2Rx") (class "Default")
      (node (ref "U1") (pin "31") (pinfunction "SDA2/PMA9/RP100/RF4_31") (pintype "passive"))
    )
    (net (code "152") (name "/U2Tx") (class "Default")
      (node (ref "U1") (pin "32") (pinfunction "SCL2/PMA8/RP101/RF5_32") (pintype "passive"))
    )
    (net (code "153") (name "/USB5.0V") (class "Default")
      (node (ref "J3") (pin "1") (pinfunction "1_1") (pintype "passive"))
      (node (ref "R46") (pin "2") (pinfunction "2_2") (pintype "passive"))
      (node (ref "R56") (pin "2") (pinfunction "2_2") (pintype "passive"))
    )
    (net (code "154") (name "/USBDM{slash}D-") (class "Default")
      (node (ref "J3") (pin "2") (pinfunction "2_2") (pintype "passive"))
      (node (ref "R34") (pin "1") (pinfunction "1_1") (pintype "passive"))
    )
    (net (code "155") (name "/USBDP{slash}D+") (class "Default")
      (node (ref "J3") (pin "3") (pinfunction "3_3") (pintype "passive"))
      (node (ref "R35") (pin "1") (pinfunction "1_1") (pintype "passive"))
    )
    (net (code "156") (name "/USBMCU5.0V") (class "Default")
      (node (ref "R56") (pin "1") (pinfunction "1_1") (pintype "passive"))
      (node (ref "R62") (pin "1") (pinfunction "1_1") (pintype "passive"))
      (node (ref "U1") (pin "34") (pinfunction "VBUS_34") (pintype "passive"))
    )
    (net (code "157") (name "/VCAP") (class "Default")
      (node (ref "C17") (pin "1") (pinfunction "1_1") (pintype "passive"))
      (node (ref "U1") (pin "56") (pinfunction "VCAP_56") (pintype "passive"))
    )
    (net (code "158") (name "/XCLK1") (class "Default")
      (node (ref "U1") (pin "46") (pinfunction "INT0/DMH/RP64/RD0_46") (pintype "passive"))
      (node (ref "U2") (pin "9") (pinfunction "XCLKIN_9") (pintype "passive"))
    )
    (net (code "159") (name "/XCLK2") (class "Default")
      (node (ref "U2") (pin "10") (pinfunction "CLKOUT_10") (pintype "passive"))
      (node (ref "U3") (pin "9") (pinfunction "XCLKIN_9") (pintype "passive"))
    )
    (net (code "160") (name "/XCLK3") (class "Default")
      (node (ref "U3") (pin "10") (pinfunction "CLKOUT_10") (pintype "passive"))
      (node (ref "U4") (pin "9") (pinfunction "XCLKIN_9") (pintype "passive"))
    )
    (net (code "161") (name "/XCLK4") (class "Default")
      (node (ref "U4") (pin "10") (pinfunction "CLKOUT_10") (pintype "passive"))
      (node (ref "U5") (pin "9") (pinfunction "XCLKIN_9") (pintype "passive"))
    )
    (net (code "162") (name "/XCLK5") (class "Default")
      (node (ref "R30") (pin "1") (pinfunction "1_1") (pintype "passive"))
      (node (ref "R30") (pin "2") (pinfunction "2_2") (pintype "passive"))
      (node (ref "U5") (pin "10") (pinfunction "CLKOUT_10") (pintype "passive"))
      (node (ref "U7") (pin "9") (pinfunction "XCLKIN_9") (pintype "passive"))
    )
    (net (code "163") (name "/XCLK6") (class "Default")
      (node (ref "U7") (pin "10") (pinfunction "CLKOUT_10") (pintype "passive"))
      (node (ref "U8") (pin "9") (pinfunction "XCLKIN_9") (pintype "passive"))
    )
    (net (code "164") (name "/XCLK7") (class "Default")
      (node (ref "U8") (pin "10") (pinfunction "CLKOUT_10") (pintype "passive"))
      (node (ref "U9") (pin "9") (pinfunction "XCLKIN_9") (pintype "passive"))
    )
    (net (code "165") (name "/XCLK8") (class "Default")
      (node (ref "U10") (pin "9") (pinfunction "XCLKIN_9") (pintype "passive"))
      (node (ref "U9") (pin "10") (pinfunction "CLKOUT_10") (pintype "passive"))
    )
    (net (code "166") (name "/XCLK9") (class "Default")
      (node (ref "R31") (pin "2") (pinfunction "2_2") (pintype "passive"))
      (node (ref "U10") (pin "10") (pinfunction "CLKOUT_10") (pintype "passive"))
    )
    (net (code "167") (name "/XCLK9I") (class "Default")
      (node (ref "R31") (pin "1") (pinfunction "1_1") (pintype "passive"))
      (node (ref "U1") (pin "49") (pinfunction "VCPCON/RP65/RD1_49") (pintype "passive"))
      (node (ref "U11") (pin "9") (pinfunction "XCLKIN_9") (pintype "passive"))
    )
    (net (code "168") (name "/XCLK10") (class "Default")
      (node (ref "U11") (pin "10") (pinfunction "CLKOUT_10") (pintype "passive"))
      (node (ref "U12") (pin "9") (pinfunction "XCLKIN_9") (pintype "passive"))
    )
    (net (code "169") (name "/XCLK11") (class "Default")
      (node (ref "U12") (pin "10") (pinfunction "CLKOUT_10") (pintype "passive"))
      (node (ref "U13") (pin "9") (pinfunction "XCLKIN_9") (pintype "passive"))
    )
    (net (code "170") (name "/XCLK12") (class "Default")
      (node (ref "U13") (pin "10") (pinfunction "CLKOUT_10") (pintype "passive"))
      (node (ref "U14") (pin "9") (pinfunction "XCLKIN_9") (pintype "passive"))
    )
    (net (code "171") (name "/XCLK13") (class "Default")
      (node (ref "R32") (pin "1") (pinfunction "1_1") (pintype "passive"))
      (node (ref "R32") (pin "2") (pinfunction "2_2") (pintype "passive"))
      (node (ref "U14") (pin "10") (pinfunction "CLKOUT_10") (pintype "passive"))
      (node (ref "U15") (pin "9") (pinfunction "XCLKIN_9") (pintype "passive"))
    )
    (net (code "172") (name "/XCLK14") (class "Default")
      (node (ref "U15") (pin "10") (pinfunction "CLKOUT_10") (pintype "passive"))
      (node (ref "U16") (pin "9") (pinfunction "XCLKIN_9") (pintype "passive"))
    )
    (net (code "173") (name "/XCLK15") (class "Default")
      (node (ref "U16") (pin "10") (pinfunction "CLKOUT_10") (pintype "passive"))
      (node (ref "U17") (pin "9") (pinfunction "XCLKIN_9") (pintype "passive"))
    )
    (net (code "174") (name "/XCLK16") (class "Default")
      (node (ref "U17") (pin "10") (pinfunction "CLKOUT_10") (pintype "passive"))
      (node (ref "U18") (pin "9") (pinfunction "XCLKIN_9") (pintype "passive"))
    )
    (net (code "175") (name "/XCLK17") (class "Default")
      (node (ref "U18") (pin "10") (pinfunction "CLKOUT_10") (pintype "passive"))
    )
    (net (code "176") (name "/YELLOW") (class "Default")
      (node (ref "D6") (pin "2") (pinfunction "A_2") (pintype "passive"))
      (node (ref "U1") (pin "44") (pinfunction "ASCL1/PMCS2/RPI74/RD10_44") (pintype "passive"))
    )
    (net (code "177") (name "GND") (class "Default")
      (node (ref "C1") (pin "2") (pinfunction "2_2") (pintype "passive"))
      (node (ref "C10") (pin "2") (pinfunction "2_2") (pintype "passive"))
      (node (ref "C100") (pin "2") (pinfunction "2_2") (pintype "passive"))
      (node (ref "C101") (pin "2") (pinfunction "2_2") (pintype "passive"))
      (node (ref "C102") (pin "2") (pinfunction "2_2") (pintype "passive"))
      (node (ref "C103") (pin "2") (pinfunction "2_2") (pintype "passive"))
      (node (ref "C104") (pin "2") (pinfunction "2_2") (pintype "passive"))
      (node (ref "C105") (pin "2") (pinfunction "2_2") (pintype "passive"))
      (node (ref "C106") (pin "2") (pinfunction "2_2") (pintype "passive"))
      (node (ref "C107") (pin "2") (pinfunction "2_2") (pintype "passive"))
      (node (ref "C108") (pin "2") (pinfunction "2_2") (pintype "passive"))
      (node (ref "C109") (pin "2") (pinfunction "2_2") (pintype "passive"))
      (node (ref "C11") (pin "2") (pinfunction "2_2") (pintype "passive"))
      (node (ref "C110") (pin "2") (pinfunction "2_2") (pintype "passive"))
      (node (ref "C111") (pin "2") (pinfunction "2_2") (pintype "passive"))
      (node (ref "C112") (pin "2") (pinfunction "2_2") (pintype "passive"))
      (node (ref "C113") (pin "2") (pinfunction "2_2") (pintype "passive"))
      (node (ref "C114") (pin "2") (pinfunction "2_2") (pintype "passive"))
      (node (ref "C115") (pin "2") (pinfunction "2_2") (pintype "passive"))
      (node (ref "C116") (pin "2") (pinfunction "2_2") (pintype "passive"))
      (node (ref "C117") (pin "2") (pinfunction "2_2") (pintype "passive"))
      (node (ref "C118") (pin "2") (pinfunction "2_2") (pintype "passive"))
      (node (ref "C119") (pin "2") (pinfunction "2_2") (pintype "passive"))
      (node (ref "C12") (pin "2") (pinfunction "2_2") (pintype "passive"))
      (node (ref "C120") (pin "2") (pinfunction "2_2") (pintype "passive"))
      (node (ref "C121") (pin "2") (pinfunction "2_2") (pintype "passive"))
      (node (ref "C122") (pin "2") (pinfunction "2_2") (pintype "passive"))
      (node (ref "C123") (pin "2") (pinfunction "2_2") (pintype "passive"))
      (node (ref "C124") (pin "2") (pinfunction "2_2") (pintype "passive"))
      (node (ref "C125") (pin "2") (pinfunction "2_2") (pintype "passive"))
      (node (ref "C126") (pin "2") (pinfunction "2_2") (pintype "passive"))
      (node (ref "C127") (pin "2") (pinfunction "2_2") (pintype "passive"))
      (node (ref "C128") (pin "2") (pinfunction "2_2") (pintype "passive"))
      (node (ref "C129") (pin "2") (pinfunction "2_2") (pintype "passive"))
      (node (ref "C13") (pin "2") (pinfunction "2_2") (pintype "passive"))
      (node (ref "C130") (pin "2") (pinfunction "2_2") (pintype "passive"))
      (node (ref "C131") (pin "2") (pinfunction "2_2") (pintype "passive"))
      (node (ref "C132") (pin "2") (pinfunction "2_2") (pintype "passive"))
      (node (ref "C133") (pin "1") (pinfunction "1_1") (pintype "passive"))
      (node (ref "C134") (pin "2") (pinfunction "2_2") (pintype "passive"))
      (node (ref "C135") (pin "2") (pinfunction "2_2") (pintype "passive"))
      (node (ref "C136") (pin "1") (pinfunction "1_1") (pintype "passive"))
      (node (ref "C137") (pin "2") (pinfunction "2_2") (pintype "passive"))
      (node (ref "C138") (pin "2") (pinfunction "2_2") (pintype "passive"))
      (node (ref "C139") (pin "1") (pinfunction "1_1") (pintype "passive"))
      (node (ref "C14") (pin "2") (pinfunction "2_2") (pintype "passive"))
      (node (ref "C140") (pin "2") (pinfunction "2_2") (pintype "passive"))
      (node (ref "C141") (pin "2") (pinfunction "2_2") (pintype "passive"))
      (node (ref "C142") (pin "1") (pinfunction "1_1") (pintype "passive"))
      (node (ref "C143") (pin "2") (pinfunction "2_2") (pintype "passive"))
      (node (ref "C144") (pin "2") (pinfunction "2_2") (pintype "passive"))
      (node (ref "C145") (pin "2") (pinfunction "2_2") (pintype "passive"))
      (node (ref "C146") (pin "2") (pinfunction "2_2") (pintype "passive"))
      (node (ref "C147") (pin "2") (pinfunction "2_2") (pintype "passive"))
      (node (ref "C148") (pin "2") (pinfunction "2_2") (pintype "passive"))
      (node (ref "C149") (pin "2") (pinfunction "2_2") (pintype "passive"))
      (node (ref "C15") (pin "2") (pinfunction "2_2") (pintype "passive"))
      (node (ref "C150") (pin "2") (pinfunction "2_2") (pintype "passive"))
      (node (ref "C151") (pin "2") (pinfunction "2_2") (pintype "passive"))
      (node (ref "C152") (pin "2") (pinfunction "2_2") (pintype "passive"))
      (node (ref "C153") (pin "2") (pinfunction "2_2") (pintype "passive"))
      (node (ref "C154") (pin "2") (pinfunction "2_2") (pintype "passive"))
      (node (ref "C155") (pin "2") (pinfunction "2_2") (pintype "passive"))
      (node (ref "C156") (pin "2") (pinfunction "2_2") (pintype "passive"))
      (node (ref "C157") (pin "2") (pinfunction "2_2") (pintype "passive"))
      (node (ref "C158") (pin "2") (pinfunction "2_2") (pintype "passive"))
      (node (ref "C159") (pin "2") (pinfunction "2_2") (pintype "passive"))
      (node (ref "C16") (pin "2") (pinfunction "2_2") (pintype "passive"))
      (node (ref "C160") (pin "2") (pinfunction "2_2") (pintype "passive"))
      (node (ref "C161") (pin "2") (pinfunction "2_2") (pintype "passive"))
      (node (ref "C162") (pin "2") (pinfunction "2_2") (pintype "passive"))
      (node (ref "C163") (pin "2") (pinfunction "2_2") (pintype "passive"))
      (node (ref "C164") (pin "2") (pinfunction "2_2") (pintype "passive"))
      (node (ref "C165") (pin "2") (pinfunction "2_2") (pintype "passive"))
      (node (ref "C166") (pin "2") (pinfunction "2_2") (pintype "passive"))
      (node (ref "C167") (pin "2") (pinfunction "2_2") (pintype "passive"))
      (node (ref "C168") (pin "2") (pinfunction "2_2") (pintype "passive"))
      (node (ref "C169") (pin "2") (pinfunction "2_2") (pintype "passive"))
      (node (ref "C17") (pin "2") (pinfunction "2_2") (pintype "passive"))
      (node (ref "C170") (pin "2") (pinfunction "2_2") (pintype "passive"))
      (node (ref "C171") (pin "2") (pinfunction "2_2") (pintype "passive"))
      (node (ref "C172") (pin "2") (pinfunction "2_2") (pintype "passive"))
      (node (ref "C173") (pin "2") (pinfunction "2_2") (pintype "passive"))
      (node (ref "C174") (pin "2") (pinfunction "2_2") (pintype "passive"))
      (node (ref "C175") (pin "2") (pinfunction "2_2") (pintype "passive"))
      (node (ref "C176") (pin "2") (pinfunction "2_2") (pintype "passive"))
      (node (ref "C177") (pin "1") (pinfunction "1_1") (pintype "passive"))
      (node (ref "C178") (pin "2") (pinfunction "2_2") (pintype "passive"))
      (node (ref "C179") (pin "2") (pinfunction "2_2") (pintype "passive"))
      (node (ref "C18") (pin "2") (pinfunction "2_2") (pintype "passive"))
      (node (ref "C180") (pin "1") (pinfunction "1_1") (pintype "passive"))
      (node (ref "C181") (pin "2") (pinfunction "2_2") (pintype "passive"))
      (node (ref "C182") (pin "2") (pinfunction "2_2") (pintype "passive"))
      (node (ref "C183") (pin "1") (pinfunction "1_1") (pintype "passive"))
      (node (ref "C184") (pin "2") (pinfunction "2_2") (pintype "passive"))
      (node (ref "C185") (pin "2") (pinfunction "2_2") (pintype "passive"))
      (node (ref "C186") (pin "1") (pinfunction "1_1") (pintype "passive"))
      (node (ref "C187") (pin "2") (pinfunction "2_2") (pintype "passive"))
      (node (ref "C188") (pin "1") (pinfunction "1_1") (pintype "passive"))
      (node (ref "C19") (pin "2") (pinfunction "2_2") (pintype "passive"))
      (node (ref "C190") (pin "2") (pinfunction "2_2") (pintype "passive"))
      (node (ref "C191") (pin "2") (pinfunction "2_2") (pintype "passive"))
      (node (ref "C192") (pin "2") (pinfunction "2_2") (pintype "passive"))
      (node (ref "C193") (pin "2") (pinfunction "2_2") (pintype "passive"))
      (node (ref "C194") (pin "2") (pinfunction "2_2") (pintype "passive"))
      (node (ref "C195") (pin "2") (pinfunction "2_2") (pintype "passive"))
      (node (ref "C196") (pin "2") (pinfunction "2_2") (pintype "passive"))
      (node (ref "C197") (pin "2") (pinfunction "2_2") (pintype "passive"))
      (node (ref "C198") (pin "2") (pinfunction "2_2") (pintype "passive"))
      (node (ref "C199") (pin "2") (pinfunction "2_2") (pintype "passive"))
      (node (ref "C2") (pin "2") (pinfunction "2_2") (pintype "passive"))
      (node (ref "C20") (pin "2") (pinfunction "2_2") (pintype "passive"))
      (node (ref "C200") (pin "2") (pinfunction "2_2") (pintype "passive"))
      (node (ref "C201") (pin "2") (pinfunction "2_2") (pintype "passive"))
      (node (ref "C202") (pin "2") (pinfunction "2_2") (pintype "passive"))
      (node (ref "C203") (pin "2") (pinfunction "2_2") (pintype "passive"))
      (node (ref "C204") (pin "2") (pinfunction "2_2") (pintype "passive"))
      (node (ref "C205") (pin "2") (pinfunction "2_2") (pintype "passive"))
      (node (ref "C207") (pin "2") (pinfunction "2_2") (pintype "passive"))
      (node (ref "C208") (pin "2") (pinfunction "2_2") (pintype "passive"))
      (node (ref "C21") (pin "2") (pinfunction "2_2") (pintype "passive"))
      (node (ref "C210") (pin "2") (pinfunction "2_2") (pintype "passive"))
      (node (ref "C211") (pin "2") (pinfunction "2_2") (pintype "passive"))
      (node (ref "C212") (pin "2") (pinfunction "2_2") (pintype "passive"))
      (node (ref "C213") (pin "2") (pinfunction "2_2") (pintype "passive"))
      (node (ref "C214") (pin "2") (pinfunction "2_2") (pintype "passive"))
      (node (ref "C215") (pin "2") (pinfunction "2_2") (pintype "passive"))
      (node (ref "C216") (pin "2") (pinfunction "2_2") (pintype "passive"))
      (node (ref "C217") (pin "2") (pinfunction "2_2") (pintype "passive"))
      (node (ref "C218") (pin "2") (pinfunction "2_2") (pintype "passive"))
      (node (ref "C219") (pin "2") (pinfunction "2_2") (pintype "passive"))
      (node (ref "C22") (pin "2") (pinfunction "2_2") (pintype "passive"))
      (node (ref "C220") (pin "2") (pinfunction "2_2") (pintype "passive"))
      (node (ref "C221") (pin "2") (pinfunction "2_2") (pintype "passive"))
      (node (ref "C222") (pin "2") (pinfunction "2_2") (pintype "passive"))
      (node (ref "C223") (pin "2") (pinfunction "2_2") (pintype "passive"))
      (node (ref "C224") (pin "2") (pinfunction "2_2") (pintype "passive"))
      (node (ref "C225") (pin "2") (pinfunction "2_2") (pintype "passive"))
      (node (ref "C226") (pin "2") (pinfunction "2_2") (pintype "passive"))
      (node (ref "C227") (pin "2") (pinfunction "2_2") (pintype "passive"))
      (node (ref "C228") (pin "2") (pinfunction "2_2") (pintype "passive"))
      (node (ref "C229") (pin "2") (pinfunction "2_2") (pintype "passive"))
      (node (ref "C23") (pin "2") (pinfunction "2_2") (pintype "passive"))
      (node (ref "C230") (pin "2") (pinfunction "2_2") (pintype "passive"))
      (node (ref "C231") (pin "2") (pinfunction "2_2") (pintype "passive"))
      (node (ref "C232") (pin "2") (pinfunction "2_2") (pintype "passive"))
      (node (ref "C233") (pin "2") (pinfunction "2_2") (pintype "passive"))
      (node (ref "C234") (pin "2") (pinfunction "2_2") (pintype "passive"))
      (node (ref "C235") (pin "2") (pinfunction "2_2") (pintype "passive"))
      (node (ref "C236") (pin "2") (pinfunction "2_2") (pintype "passive"))
      (node (ref "C237") (pin "2") (pinfunction "2_2") (pintype "passive"))
      (node (ref "C238") (pin "2") (pinfunction "2_2") (pintype "passive"))
      (node (ref "C239") (pin "2") (pinfunction "2_2") (pintype "passive"))
      (node (ref "C24") (pin "2") (pinfunction "2_2") (pintype "passive"))
      (node (ref "C240") (pin "2") (pinfunction "2_2") (pintype "passive"))
      (node (ref "C241") (pin "2") (pinfunction "2_2") (pintype "passive"))
      (node (ref "C242") (pin "2") (pinfunction "2_2") (pintype "passive"))
      (node (ref "C243") (pin "2") (pinfunction "2_2") (pintype "passive"))
      (node (ref "C244") (pin "2") (pinfunction "2_2") (pintype "passive"))
      (node (ref "C245") (pin "2") (pinfunction "2_2") (pintype "passive"))
      (node (ref "C246") (pin "2") (pinfunction "2_2") (pintype "passive"))
      (node (ref "C247") (pin "2") (pinfunction "2_2") (pintype "passive"))
      (node (ref "C248") (pin "2") (pinfunction "2_2") (pintype "passive"))
      (node (ref "C249") (pin "2") (pinfunction "2_2") (pintype "passive"))
      (node (ref "C25") (pin "2") (pinfunction "2_2") (pintype "passive"))
      (node (ref "C250") (pin "2") (pinfunction "2_2") (pintype "passive"))
      (node (ref "C251") (pin "2") (pinfunction "2_2") (pintype "passive"))
      (node (ref "C252") (pin "2") (pinfunction "2_2") (pintype "passive"))
      (node (ref "C253") (pin "1") (pinfunction "1_1") (pintype "passive"))
      (node (ref "C254") (pin "1") (pinfunction "1_1") (pintype "passive"))
      (node (ref "C255") (pin "2") (pinfunction "2_2") (pintype "passive"))
      (node (ref "C256") (pin "2") (pinfunction "2_2") (pintype "passive"))
      (node (ref "C257") (pin "2") (pinfunction "2_2") (pintype "passive"))
      (node (ref "C258") (pin "2") (pinfunction "2_2") (pintype "passive"))
      (node (ref "C259") (pin "2") (pinfunction "2_2") (pintype "passive"))
      (node (ref "C26") (pin "2") (pinfunction "2_2") (pintype "passive"))
      (node (ref "C260") (pin "2") (pinfunction "2_2") (pintype "passive"))
      (node (ref "C261") (pin "2") (pinfunction "2_2") (pintype "passive"))
      (node (ref "C262") (pin "2") (pinfunction "2_2") (pintype "passive"))
      (node (ref "C263") (pin "2") (pinfunction "2_2") (pintype "passive"))
      (node (ref "C264") (pin "2") (pinfunction "2_2") (pintype "passive"))
      (node (ref "C265") (pin "2") (pinfunction "2_2") (pintype "passive"))
      (node (ref "C266") (pin "2") (pinfunction "2_2") (pintype "passive"))
      (node (ref "C267") (pin "2") (pinfunction "2_2") (pintype "passive"))
      (node (ref "C268") (pin "2") (pinfunction "2_2") (pintype "passive"))
      (node (ref "C269") (pin "2") (pinfunction "2_2") (pintype "passive"))
      (node (ref "C27") (pin "2") (pinfunction "2_2") (pintype "passive"))
      (node (ref "C270") (pin "2") (pinfunction "2_2") (pintype "passive"))
      (node (ref "C271") (pin "2") (pinfunction "2_2") (pintype "passive"))
      (node (ref "C272") (pin "2") (pinfunction "2_2") (pintype "passive"))
      (node (ref "C273") (pin "2") (pinfunction "2_2") (pintype "passive"))
      (node (ref "C274") (pin "2") (pinfunction "2_2") (pintype "passive"))
      (node (ref "C275") (pin "2") (pinfunction "2_2") (pintype "passive"))
      (node (ref "C276") (pin "2") (pinfunction "2_2") (pintype "passive"))
      (node (ref "C277") (pin "2") (pinfunction "2_2") (pintype "passive"))
      (node (ref "C278") (pin "2") (pinfunction "2_2") (pintype "passive"))
      (node (ref "C279") (pin "2") (pinfunction "2_2") (pintype "passive"))
      (node (ref "C28") (pin "2") (pinfunction "2_2") (pintype "passive"))
      (node (ref "C280") (pin "2") (pinfunction "2_2") (pintype "passive"))
      (node (ref "C281") (pin "2") (pinfunction "2_2") (pintype "passive"))
      (node (ref "C282") (pin "2") (pinfunction "2_2") (pintype "passive"))
      (node (ref "C283") (pin "2") (pinfunction "2_2") (pintype "passive"))
      (node (ref "C284") (pin "2") (pinfunction "2_2") (pintype "passive"))
      (node (ref "C285") (pin "2") (pinfunction "2_2") (pintype "passive"))
      (node (ref "C286") (pin "2") (pinfunction "2_2") (pintype "passive"))
      (node (ref "C287") (pin "2") (pinfunction "2_2") (pintype "passive"))
      (node (ref "C288") (pin "2") (pinfunction "2_2") (pintype "passive"))
      (node (ref "C289") (pin "2") (pinfunction "2_2") (pintype "passive"))
      (node (ref "C29") (pin "2") (pinfunction "2_2") (pintype "passive"))
      (node (ref "C290") (pin "2") (pinfunction "2_2") (pintype "passive"))
      (node (ref "C291") (pin "2") (pinfunction "2_2") (pintype "passive"))
      (node (ref "C292") (pin "2") (pinfunction "2_2") (pintype "passive"))
      (node (ref "C293") (pin "2") (pinfunction "2_2") (pintype "passive"))
      (node (ref "C294") (pin "2") (pinfunction "2_2") (pintype "passive"))
      (node (ref "C295") (pin "2") (pinfunction "2_2") (pintype "passive"))
      (node (ref "C296") (pin "2") (pinfunction "2_2") (pintype "passive"))
      (node (ref "C297") (pin "2") (pinfunction "2_2") (pintype "passive"))
      (node (ref "C298") (pin "2") (pinfunction "2_2") (pintype "passive"))
      (node (ref "C299") (pin "2") (pinfunction "2_2") (pintype "passive"))
      (node (ref "C3") (pin "2") (pinfunction "2_2") (pintype "passive"))
      (node (ref "C30") (pin "2") (pinfunction "2_2") (pintype "passive"))
      (node (ref "C300") (pin "2") (pinfunction "2_2") (pintype "passive"))
      (node (ref "C301") (pin "2") (pinfunction "2_2") (pintype "passive"))
      (node (ref "C302") (pin "2") (pinfunction "2_2") (pintype "passive"))
      (node (ref "C303") (pin "2") (pinfunction "2_2") (pintype "passive"))
      (node (ref "C304") (pin "2") (pinfunction "2_2") (pintype "passive"))
      (node (ref "C305") (pin "2") (pinfunction "2_2") (pintype "passive"))
      (node (ref "C306") (pin "2") (pinfunction "2_2") (pintype "passive"))
      (node (ref "C307") (pin "2") (pinfunction "2_2") (pintype "passive"))
      (node (ref "C308") (pin "1") (pinfunction "1_1") (pintype "passive"))
      (node (ref "C309") (pin "2") (pinfunction "2_2") (pintype "passive"))
      (node (ref "C31") (pin "2") (pinfunction "2_2") (pintype "passive"))
      (node (ref "C311") (pin "2") (pinfunction "2_2") (pintype "passive"))
      (node (ref "C313") (pin "2") (pinfunction "2_2") (pintype "passive"))
      (node (ref "C314") (pin "2") (pinfunction "2_2") (pintype "passive"))
      (node (ref "C315") (pin "2") (pinfunction "2_2") (pintype "passive"))
      (node (ref "C316") (pin "2") (pinfunction "2_2") (pintype "passive"))
      (node (ref "C317") (pin "2") (pinfunction "2_2") (pintype "passive"))
      (node (ref "C318") (pin "2") (pinfunction "2_2") (pintype "passive"))
      (node (ref "C319") (pin "2") (pinfunction "2_2") (pintype "passive"))
      (node (ref "C32") (pin "2") (pinfunction "2_2") (pintype "passive"))
      (node (ref "C320") (pin "2") (pinfunction "2_2") (pintype "passive"))
      (node (ref "C321") (pin "2") (pinfunction "2_2") (pintype "passive"))
      (node (ref "C322") (pin "2") (pinfunction "2_2") (pintype "passive"))
      (node (ref "C323") (pin "2") (pinfunction "2_2") (pintype "passive"))
      (node (ref "C324") (pin "2") (pinfunction "2_2") (pintype "passive"))
      (node (ref "C325") (pin "2") (pinfunction "2_2") (pintype "passive"))
      (node (ref "C33") (pin "2") (pinfunction "2_2") (pintype "passive"))
      (node (ref "C34") (pin "2") (pinfunction "2_2") (pintype "passive"))
      (node (ref "C35") (pin "2") (pinfunction "2_2") (pintype "passive"))
      (node (ref "C36") (pin "2") (pinfunction "2_2") (pintype "passive"))
      (node (ref "C37") (pin "1") (pinfunction "1_1") (pintype "passive"))
      (node (ref "C38") (pin "2") (pinfunction "2_2") (pintype "passive"))
      (node (ref "C39") (pin "2") (pinfunction "2_2") (pintype "passive"))
      (node (ref "C4") (pin "2") (pinfunction "2_2") (pintype "passive"))
      (node (ref "C40") (pin "1") (pinfunction "1_1") (pintype "passive"))
      (node (ref "C41") (pin "2") (pinfunction "2_2") (pintype "passive"))
      (node (ref "C42") (pin "2") (pinfunction "2_2") (pintype "passive"))
      (node (ref "C43") (pin "1") (pinfunction "1_1") (pintype "passive"))
      (node (ref "C44") (pin "2") (pinfunction "2_2") (pintype "passive"))
      (node (ref "C45") (pin "2") (pinfunction "2_2") (pintype "passive"))
      (node (ref "C46") (pin "1") (pinfunction "1_1") (pintype "passive"))
      (node (ref "C47") (pin "2") (pinfunction "2_2") (pintype "passive"))
      (node (ref "C48") (pin "2") (pinfunction "2_2") (pintype "passive"))
      (node (ref "C49") (pin "2") (pinfunction "2_2") (pintype "passive"))
      (node (ref "C5") (pin "2") (pinfunction "2_2") (pintype "passive"))
      (node (ref "C50") (pin "2") (pinfunction "2_2") (pintype "passive"))
      (node (ref "C51") (pin "2") (pinfunction "2_2") (pintype "passive"))
      (node (ref "C52") (pin "2") (pinfunction "2_2") (pintype "passive"))
      (node (ref "C53") (pin "2") (pinfunction "2_2") (pintype "passive"))
      (node (ref "C54") (pin "2") (pinfunction "2_2") (pintype "passive"))
      (node (ref "C55") (pin "2") (pinfunction "2_2") (pintype "passive"))
      (node (ref "C56") (pin "2") (pinfunction "2_2") (pintype "passive"))
      (node (ref "C57") (pin "2") (pinfunction "2_2") (pintype "passive"))
      (node (ref "C58") (pin "2") (pinfunction "2_2") (pintype "passive"))
      (node (ref "C59") (pin "2") (pinfunction "2_2") (pintype "passive"))
      (node (ref "C6") (pin "2") (pinfunction "2_2") (pintype "passive"))
      (node (ref "C60") (pin "2") (pinfunction "2_2") (pintype "passive"))
      (node (ref "C61") (pin "2") (pinfunction "2_2") (pintype "passive"))
      (node (ref "C62") (pin "2") (pinfunction "2_2") (pintype "passive"))
      (node (ref "C63") (pin "2") (pinfunction "2_2") (pintype "passive"))
      (node (ref "C64") (pin "2") (pinfunction "2_2") (pintype "passive"))
      (node (ref "C65") (pin "2") (pinfunction "2_2") (pintype "passive"))
      (node (ref "C66") (pin "2") (pinfunction "2_2") (pintype "passive"))
      (node (ref "C67") (pin "2") (pinfunction "2_2") (pintype "passive"))
      (node (ref "C68") (pin "2") (pinfunction "2_2") (pintype "passive"))
      (node (ref "C69") (pin "2") (pinfunction "2_2") (pintype "passive"))
      (node (ref "C7") (pin "2") (pinfunction "2_2") (pintype "passive"))
      (node (ref "C70") (pin "2") (pinfunction "2_2") (pintype "passive"))
      (node (ref "C71") (pin "2") (pinfunction "2_2") (pintype "passive"))
      (node (ref "C72") (pin "2") (pinfunction "2_2") (pintype "passive"))
      (node (ref "C73") (pin "2") (pinfunction "2_2") (pintype "passive"))
      (node (ref "C74") (pin "2") (pinfunction "2_2") (pintype "passive"))
      (node (ref "C75") (pin "2") (pinfunction "2_2") (pintype "passive"))
      (node (ref "C76") (pin "2") (pinfunction "2_2") (pintype "passive"))
      (node (ref "C77") (pin "2") (pinfunction "2_2") (pintype "passive"))
      (node (ref "C78") (pin "2") (pinfunction "2_2") (pintype "passive"))
      (node (ref "C79") (pin "2") (pinfunction "2_2") (pintype "passive"))
      (node (ref "C8") (pin "2") (pinfunction "2_2") (pintype "passive"))
      (node (ref "C80") (pin "2") (pinfunction "2_2") (pintype "passive"))
      (node (ref "C81") (pin "2") (pinfunction "2_2") (pintype "passive"))
      (node (ref "C82") (pin "2") (pinfunction "2_2") (pintype "passive"))
      (node (ref "C83") (pin "2") (pinfunction "2_2") (pintype "passive"))
      (node (ref "C84") (pin "2") (pinfunction "2_2") (pintype "passive"))
      (node (ref "C85") (pin "2") (pinfunction "2_2") (pintype "passive"))
      (node (ref "C86") (pin "2") (pinfunction "2_2") (pintype "passive"))
      (node (ref "C87") (pin "2") (pinfunction "2_2") (pintype "passive"))
      (node (ref "C88") (pin "2") (pinfunction "2_2") (pintype "passive"))
      (node (ref "C89") (pin "1") (pinfunction "1_1") (pintype "passive"))
      (node (ref "C9") (pin "2") (pinfunction "2_2") (pintype "passive"))
      (node (ref "C90") (pin "2") (pinfunction "2_2") (pintype "passive"))
      (node (ref "C91") (pin "2") (pinfunction "2_2") (pintype "passive"))
      (node (ref "C92") (pin "1") (pinfunction "1_1") (pintype "passive"))
      (node (ref "C93") (pin "2") (pinfunction "2_2") (pintype "passive"))
      (node (ref "C94") (pin "2") (pinfunction "2_2") (pintype "passive"))
      (node (ref "C95") (pin "1") (pinfunction "1_1") (pintype "passive"))
      (node (ref "C96") (pin "2") (pinfunction "2_2") (pintype "passive"))
      (node (ref "C97") (pin "2") (pinfunction "2_2") (pintype "passive"))
      (node (ref "C98") (pin "1") (pinfunction "1_1") (pintype "passive"))
      (node (ref "C99") (pin "2") (pinfunction "2_2") (pintype "passive"))
      (node (ref "D3") (pin "1") (pinfunction "A1_1") (pintype "passive"))
      (node (ref "D3") (pin "2") (pinfunction "A2_2") (pintype "passive"))
      (node (ref "D4") (pin "1") (pinfunction "C_1") (pintype "passive"))
      (node (ref "D5") (pin "1") (pinfunction "C_1") (pintype "passive"))
      (node (ref "D6") (pin "1") (pinfunction "C_1") (pintype "passive"))
      (node (ref "D7") (pin "1") (pinfunction "C_1") (pintype "passive"))
      (node (ref "J1") (pin "3") (pinfunction "3_3") (pintype "passive"))
      (node (ref "J2") (pin "2") (pinfunction "2_2") (pintype "passive"))
      (node (ref "J2") (pin "3") (pinfunction "3_3") (pintype "passive"))
      (node (ref "J3") (pin "5") (pinfunction "5_5") (pintype "passive"))
      (node (ref "J3") (pin "6") (pinfunction "6_6") (pintype "passive"))
      (node (ref "J3") (pin "7") (pinfunction "7_7") (pintype "passive"))
      (node (ref "J3") (pin "8") (pinfunction "8_8") (pintype "passive"))
      (node (ref "J3") (pin "9") (pinfunction "9_9") (pintype "passive"))
      (node (ref "J6") (pin "1") (pinfunction "1_1") (pintype "passive"))
      (node (ref "Q2") (pin "1") (pinfunction "S_1") (pintype "passive"))
      (node (ref "Q2") (pin "2") (pinfunction "S_2") (pintype "passive"))
      (node (ref "Q2") (pin "3") (pinfunction "S_3") (pintype "passive"))
      (node (ref "Q3") (pin "1") (pinfunction "S_1") (pintype "passive"))
      (node (ref "Q3") (pin "2") (pinfunction "S_2") (pintype "passive"))
      (node (ref "Q3") (pin "3") (pinfunction "S_3") (pintype "passive"))
      (node (ref "Q5") (pin "1") (pinfunction "S_1") (pintype "passive"))
      (node (ref "Q5") (pin "2") (pinfunction "S_2") (pintype "passive"))
      (node (ref "Q5") (pin "3") (pinfunction "S_3") (pintype "passive"))
      (node (ref "Q6") (pin "1") (pinfunction "S_1") (pintype "passive"))
      (node (ref "Q6") (pin "2") (pinfunction "S_2") (pintype "passive"))
      (node (ref "Q6") (pin "3") (pinfunction "S_3") (pintype "passive"))
      (node (ref "R33") (pin "1") (pinfunction "1_1") (pintype "passive"))
      (node (ref "R40") (pin "1") (pinfunction "1_1") (pintype "passive"))
      (node (ref "R45") (pin "1") (pinfunction "1_1") (pintype "passive"))
      (node (ref "R59") (pin "1") (pinfunction "1_1") (pintype "passive"))
      (node (ref "R60") (pin "1") (pinfunction "1_1") (pintype "passive"))
      (node (ref "R61") (pin "1") (pinfunction "1_1") (pintype "passive"))
      (node (ref "R67") (pin "1") (pinfunction "1_1") (pintype "passive"))
      (node (ref "U1") (pin "20") (pinfunction "AVSS_20") (pintype "passive"))
      (node (ref "U1") (pin "25") (pinfunction "VSS_25") (pintype "passive"))
      (node (ref "U1") (pin "41") (pinfunction "VSS_41") (pintype "passive"))
      (node (ref "U1") (pin "9") (pinfunction "VSS_9") (pintype "passive"))
      (node (ref "U10") (pin "20") (pinfunction "DVSS1_20") (pintype "passive"))
      (node (ref "U10") (pin "23") (pinfunction "OVSS1_23") (pintype "passive"))
      (node (ref "U10") (pin "32") (pinfunction "DVSS2_32") (pintype "passive"))
      (node (ref "U10") (pin "38") (pinfunction "OVSS0_38") (pintype "passive"))
      (node (ref "U10") (pin "42") (pinfunction "DVSS3_42") (pintype "passive"))
      (node (ref "U10") (pin "49") (pinfunction "EP_49") (pintype "passive"))
      (node (ref "U10") (pin "5") (pinfunction "DVSS0_5") (pintype "passive"))
      (node (ref "U10") (pin "8") (pinfunction "VSSA_PLL_8") (pintype "passive"))
      (node (ref "U11") (pin "20") (pinfunction "DVSS1_20") (pintype "passive"))
      (node (ref "U11") (pin "23") (pinfunction "OVSS1_23") (pintype "passive"))
      (node (ref "U11") (pin "32") (pinfunction "DVSS2_32") (pintype "passive"))
      (node (ref "U11") (pin "38") (pinfunction "OVSS0_38") (pintype "passive"))
      (node (ref "U11") (pin "42") (pinfunction "DVSS3_42") (pintype "passive"))
      (node (ref "U11") (pin "49") (pinfunction "EP_49") (pintype "passive"))
      (node (ref "U11") (pin "5") (pinfunction "DVSS0_5") (pintype "passive"))
      (node (ref "U11") (pin "8") (pinfunction "VSSA_PLL_8") (pintype "passive"))
      (node (ref "U12") (pin "20") (pinfunction "DVSS1_20") (pintype "passive"))
      (node (ref "U12") (pin "23") (pinfunction "OVSS1_23") (pintype "passive"))
      (node (ref "U12") (pin "32") (pinfunction "DVSS2_32") (pintype "passive"))
      (node (ref "U12") (pin "38") (pinfunction "OVSS0_38") (pintype "passive"))
      (node (ref "U12") (pin "42") (pinfunction "DVSS3_42") (pintype "passive"))
      (node (ref "U12") (pin "49") (pinfunction "EP_49") (pintype "passive"))
      (node (ref "U12") (pin "5") (pinfunction "DVSS0_5") (pintype "passive"))
      (node (ref "U12") (pin "8") (pinfunction "VSSA_PLL_8") (pintype "passive"))
      (node (ref "U13") (pin "20") (pinfunction "DVSS1_20") (pintype "passive"))
      (node (ref "U13") (pin "23") (pinfunction "OVSS1_23") (pintype "passive"))
      (node (ref "U13") (pin "32") (pinfunction "DVSS2_32") (pintype "passive"))
      (node (ref "U13") (pin "38") (pinfunction "OVSS0_38") (pintype "passive"))
      (node (ref "U13") (pin "42") (pinfunction "DVSS3_42") (pintype "passive"))
      (node (ref "U13") (pin "49") (pinfunction "EP_49") (pintype "passive"))
      (node (ref "U13") (pin "5") (pinfunction "DVSS0_5") (pintype "passive"))
      (node (ref "U13") (pin "8") (pinfunction "VSSA_PLL_8") (pintype "passive"))
      (node (ref "U14") (pin "20") (pinfunction "DVSS1_20") (pintype "passive"))
      (node (ref "U14") (pin "23") (pinfunction "OVSS1_23") (pintype "passive"))
      (node (ref "U14") (pin "32") (pinfunction "DVSS2_32") (pintype "passive"))
      (node (ref "U14") (pin "38") (pinfunction "OVSS0_38") (pintype "passive"))
      (node (ref "U14") (pin "42") (pinfunction "DVSS3_42") (pintype "passive"))
      (node (ref "U14") (pin "49") (pinfunction "EP_49") (pintype "passive"))
      (node (ref "U14") (pin "5") (pinfunction "DVSS0_5") (pintype "passive"))
      (node (ref "U14") (pin "8") (pinfunction "VSSA_PLL_8") (pintype "passive"))
      (node (ref "U15") (pin "20") (pinfunction "DVSS1_20") (pintype "passive"))
      (node (ref "U15") (pin "23") (pinfunction "OVSS1_23") (pintype "passive"))
      (node (ref "U15") (pin "32") (pinfunction "DVSS2_32") (pintype "passive"))
      (node (ref "U15") (pin "38") (pinfunction "OVSS0_38") (pintype "passive"))
      (node (ref "U15") (pin "42") (pinfunction "DVSS3_42") (pintype "passive"))
      (node (ref "U15") (pin "49") (pinfunction "EP_49") (pintype "passive"))
      (node (ref "U15") (pin "5") (pinfunction "DVSS0_5") (pintype "passive"))
      (node (ref "U15") (pin "8") (pinfunction "VSSA_PLL_8") (pintype "passive"))
      (node (ref "U16") (pin "20") (pinfunction "DVSS1_20") (pintype "passive"))
      (node (ref "U16") (pin "23") (pinfunction "OVSS1_23") (pintype "passive"))
      (node (ref "U16") (pin "32") (pinfunction "DVSS2_32") (pintype "passive"))
      (node (ref "U16") (pin "38") (pinfunction "OVSS0_38") (pintype "passive"))
      (node (ref "U16") (pin "42") (pinfunction "DVSS3_42") (pintype "passive"))
      (node (ref "U16") (pin "49") (pinfunction "EP_49") (pintype "passive"))
      (node (ref "U16") (pin "5") (pinfunction "DVSS0_5") (pintype "passive"))
      (node (ref "U16") (pin "8") (pinfunction "VSSA_PLL_8") (pintype "passive"))
      (node (ref "U17") (pin "20") (pinfunction "DVSS1_20") (pintype "passive"))
      (node (ref "U17") (pin "23") (pinfunction "OVSS1_23") (pintype "passive"))
      (node (ref "U17") (pin "32") (pinfunction "DVSS2_32") (pintype "passive"))
      (node (ref "U17") (pin "38") (pinfunction "OVSS0_38") (pintype "passive"))
      (node (ref "U17") (pin "42") (pinfunction "DVSS3_42") (pintype "passive"))
      (node (ref "U17") (pin "49") (pinfunction "EP_49") (pintype "passive"))
      (node (ref "U17") (pin "5") (pinfunction "DVSS0_5") (pintype "passive"))
      (node (ref "U17") (pin "8") (pinfunction "VSSA_PLL_8") (pintype "passive"))
      (node (ref "U18") (pin "20") (pinfunction "DVSS1_20") (pintype "passive"))
      (node (ref "U18") (pin "23") (pinfunction "OVSS1_23") (pintype "passive"))
      (node (ref "U18") (pin "32") (pinfunction "DVSS2_32") (pintype "passive"))
      (node (ref "U18") (pin "38") (pinfunction "OVSS0_38") (pintype "passive"))
      (node (ref "U18") (pin "42") (pinfunction "DVSS3_42") (pintype "passive"))
      (node (ref "U18") (pin "49") (pinfunction "EP_49") (pintype "passive"))
      (node (ref "U18") (pin "5") (pinfunction "DVSS0_5") (pintype "passive"))
      (node (ref "U18") (pin "8") (pinfunction "VSSA_PLL_8") (pintype "passive"))
      (node (ref "U19") (pin "6") (pinfunction "GND_6") (pintype "passive"))
      (node (ref "U19") (pin "7") (pinfunction "GND_7") (pintype "passive"))
      (node (ref "U2") (pin "20") (pinfunction "DVSS1_20") (pintype "passive"))
      (node (ref "U2") (pin "23") (pinfunction "OVSS1_23") (pintype "passive"))
      (node (ref "U2") (pin "32") (pinfunction "DVSS2_32") (pintype "passive"))
      (node (ref "U2") (pin "38") (pinfunction "OVSS0_38") (pintype "passive"))
      (node (ref "U2") (pin "42") (pinfunction "DVSS3_42") (pintype "passive"))
      (node (ref "U2") (pin "49") (pinfunction "EP_49") (pintype "passive"))
      (node (ref "U2") (pin "5") (pinfunction "DVSS0_5") (pintype "passive"))
      (node (ref "U2") (pin "8") (pinfunction "VSSA_PLL_8") (pintype "passive"))
      (node (ref "U21") (pin "3") (pinfunction "Vdd_3") (pintype "passive"))
      (node (ref "U21") (pin "8") (pinfunction "Rs_8") (pintype "passive"))
      (node (ref "U25") (pin "4") (pinfunction "GND_4") (pintype "passive"))
      (node (ref "U25") (pin "9") (pinfunction "EP_9") (pintype "passive"))
      (node (ref "U3") (pin "20") (pinfunction "DVSS1_20") (pintype "passive"))
      (node (ref "U3") (pin "23") (pinfunction "OVSS1_23") (pintype "passive"))
      (node (ref "U3") (pin "32") (pinfunction "DVSS2_32") (pintype "passive"))
      (node (ref "U3") (pin "38") (pinfunction "OVSS0_38") (pintype "passive"))
      (node (ref "U3") (pin "42") (pinfunction "DVSS3_42") (pintype "passive"))
      (node (ref "U3") (pin "49") (pinfunction "EP_49") (pintype "passive"))
      (node (ref "U3") (pin "5") (pinfunction "DVSS0_5") (pintype "passive"))
      (node (ref "U3") (pin "8") (pinfunction "VSSA_PLL_8") (pintype "passive"))
      (node (ref "U30") (pin "4") (pinfunction "GND_4") (pintype "passive"))
      (node (ref "U30") (pin "9") (pinfunction "EP_9") (pintype "passive"))
      (node (ref "U4") (pin "20") (pinfunction "DVSS1_20") (pintype "passive"))
      (node (ref "U4") (pin "23") (pinfunction "OVSS1_23") (pintype "passive"))
      (node (ref "U4") (pin "32") (pinfunction "DVSS2_32") (pintype "passive"))
      (node (ref "U4") (pin "38") (pinfunction "OVSS0_38") (pintype "passive"))
      (node (ref "U4") (pin "42") (pinfunction "DVSS3_42") (pintype "passive"))
      (node (ref "U4") (pin "49") (pinfunction "EP_49") (pintype "passive"))
      (node (ref "U4") (pin "5") (pinfunction "DVSS0_5") (pintype "passive"))
      (node (ref "U4") (pin "8") (pinfunction "VSSA_PLL_8") (pintype "passive"))
      (node (ref "U5") (pin "20") (pinfunction "DVSS1_20") (pintype "passive"))
      (node (ref "U5") (pin "23") (pinfunction "OVSS1_23") (pintype "passive"))
      (node (ref "U5") (pin "32") (pinfunction "DVSS2_32") (pintype "passive"))
      (node (ref "U5") (pin "38") (pinfunction "OVSS0_38") (pintype "passive"))
      (node (ref "U5") (pin "42") (pinfunction "DVSS3_42") (pintype "passive"))
      (node (ref "U5") (pin "49") (pinfunction "EP_49") (pintype "passive"))
      (node (ref "U5") (pin "5") (pinfunction "DVSS0_5") (pintype "passive"))
      (node (ref "U5") (pin "8") (pinfunction "VSSA_PLL_8") (pintype "passive"))
      (node (ref "U6") (pin "2") (pinfunction "GND_2") (pintype "passive"))
      (node (ref "U7") (pin "20") (pinfunction "DVSS1_20") (pintype "passive"))
      (node (ref "U7") (pin "23") (pinfunction "OVSS1_23") (pintype "passive"))
      (node (ref "U7") (pin "32") (pinfunction "DVSS2_32") (pintype "passive"))
      (node (ref "U7") (pin "38") (pinfunction "OVSS0_38") (pintype "passive"))
      (node (ref "U7") (pin "42") (pinfunction "DVSS3_42") (pintype "passive"))
      (node (ref "U7") (pin "49") (pinfunction "EP_49") (pintype "passive"))
      (node (ref "U7") (pin "5") (pinfunction "DVSS0_5") (pintype "passive"))
      (node (ref "U7") (pin "8") (pinfunction "VSSA_PLL_8") (pintype "passive"))
      (node (ref "U8") (pin "20") (pinfunction "DVSS1_20") (pintype "passive"))
      (node (ref "U8") (pin "23") (pinfunction "OVSS1_23") (pintype "passive"))
      (node (ref "U8") (pin "32") (pinfunction "DVSS2_32") (pintype "passive"))
      (node (ref "U8") (pin "38") (pinfunction "OVSS0_38") (pintype "passive"))
      (node (ref "U8") (pin "42") (pinfunction "DVSS3_42") (pintype "passive"))
      (node (ref "U8") (pin "49") (pinfunction "EP_49") (pintype "passive"))
      (node (ref "U8") (pin "5") (pinfunction "DVSS0_5") (pintype "passive"))
      (node (ref "U8") (pin "8") (pinfunction "VSSA_PLL_8") (pintype "passive"))
      (node (ref "U9") (pin "20") (pinfunction "DVSS1_20") (pintype "passive"))
      (node (ref "U9") (pin "23") (pinfunction "OVSS1_23") (pintype "passive"))
      (node (ref "U9") (pin "32") (pinfunction "DVSS2_32") (pintype "passive"))
      (node (ref "U9") (pin "38") (pinfunction "OVSS0_38") (pintype "passive"))
      (node (ref "U9") (pin "42") (pinfunction "DVSS3_42") (pintype "passive"))
      (node (ref "U9") (pin "49") (pinfunction "EP_49") (pintype "passive"))
      (node (ref "U9") (pin "5") (pinfunction "DVSS0_5") (pintype "passive"))
      (node (ref "U9") (pin "8") (pinfunction "VSSA_PLL_8") (pintype "passive"))
    )
    (net (code "178") (name "Net-(C206-Pad2)") (class "Default")
      (node (ref "C206") (pin "2") (pinfunction "2_2") (pintype "passive"))
      (node (ref "R33") (pin "2") (pinfunction "2_2") (pintype "passive"))
    )
    (net (code "179") (name "Net-(C209-Pad1)") (class "Default")
      (node (ref "C209") (pin "1") (pinfunction "1_1") (pintype "passive"))
      (node (ref "R36") (pin "1") (pinfunction "1_1") (pintype "passive"))
      (node (ref "R37") (pin "2") (pinfunction "2_2") (pintype "passive"))
    )
    (net (code "180") (name "Net-(C310-Pad2)") (class "Default")
      (node (ref "C310") (pin "2") (pinfunction "2_2") (pintype "passive"))
      (node (ref "R67") (pin "2") (pinfunction "2_2") (pintype "passive"))
    )
    (net (code "181") (name "Net-(J4-Pad2)") (class "Default")
      (node (ref "J4") (pin "2") (pinfunction "2_2") (pintype "passive"))
      (node (ref "R41") (pin "1") (pinfunction "1_1") (pintype "passive"))
    )
    (net (code "182") (name "unconnected-(J3-Pad4)") (class "Default")
      (node (ref "J3") (pin "4") (pinfunction "4_4") (pintype "passive"))
    )
    (net (code "183") (name "unconnected-(U1-AN4{slash}C1IN2-{slash}USBOEN{slash}RPI36{slash}RB4-Pad12)") (class "Default")
      (node (ref "U1") (pin "12") (pinfunction "AN4/C1IN2-/USBOEN/RPI36/RB4_12") (pintype "passive"))
    )
    (net (code "184") (name "unconnected-(U1-AN5{slash}C1IN1+{slash}VBUSON{slash}VBUSST{slash}RPI37{slash}RB5-Pad11)") (class "Default")
      (node (ref "U1") (pin "11") (pinfunction "AN5/C1IN1+/VBUSON/VBUSST/RPI37/RB5_11") (pintype "passive"))
    )
    (net (code "185") (name "unconnected-(U1-AN8{slash}PMA6{slash}RPI40{slash}RB8-Pad21)") (class "Default")
      (node (ref "U1") (pin "21") (pinfunction "AN8/PMA6/RPI40/RB8_21") (pintype "passive"))
    )
    (net (code "186") (name "unconnected-(U1-AN9{slash}PMA7{slash}{slash}RPI41{slash}RB9-Pad22)") (class "Default")
      (node (ref "U1") (pin "22") (pinfunction "AN9/PMA7//RPI41/RB9_22") (pintype "passive"))
    )
    (net (code "187") (name "unconnected-(U1-C1IN1-{slash}SDI2{slash}PMA4{slash}RPI119{slash}RG7-Pad5)") (class "Default")
      (node (ref "U1") (pin "5") (pinfunction "C1IN1-/SDI2/PMA4/RPI119/RG7_5") (pintype "passive"))
    )
    (net (code "188") (name "unconnected-(U1-C1IN3-{slash}SCK2{slash}PMA5{slash}RP118{slash}RG6-Pad4)") (class "Default")
      (node (ref "U1") (pin "4") (pinfunction "C1IN3-/SCK2/PMA5/RP118/RG6_4") (pintype "passive"))
    )
    (net (code "189") (name "unconnected-(U1-C2IN1-{slash}PMA2{slash}RPI121{slash}RG9-Pad8)") (class "Default")
      (node (ref "U1") (pin "8") (pinfunction "C2IN1-/PMA2/RPI121/RG9_8") (pintype "passive"))
    )
    (net (code "190") (name "unconnected-(U1-C2IN3-{slash}SDO2{slash}PMA3{slash}RP120{slash}RG8-Pad6)") (class "Default")
      (node (ref "U1") (pin "6") (pinfunction "C2IN3-/SDO2/PMA3/RP120/RG8_6") (pintype "passive"))
    )
    (net (code "191") (name "unconnected-(U1-PMRD{slash}RP69{slash}RD5-Pad53)") (class "Default")
      (node (ref "U1") (pin "53") (pinfunction "PMRD/RP69/RD5_53") (pintype "passive"))
    )
    (net (code "192") (name "unconnected-(U1-PMWR{slash}RP68{slash}RD4-Pad52)") (class "Default")
      (node (ref "U1") (pin "52") (pinfunction "PMWR/RP68/RD4_52") (pintype "passive"))
    )
    (net (code "193") (name "unconnected-(U1-TDO{slash}AN11{slash}PMA12{slash}RPI43{slash}RB11-Pad24)") (class "Default")
      (node (ref "U1") (pin "24") (pinfunction "TDO/AN11/PMA12/RPI43/RB11_24") (pintype "passive"))
    )
    (net (code "194") (name "unconnected-(U1-TMS{slash}AN10{slash}CVREF{slash}PMA13{slash}RPI42{slash}RB10-Pad23)") (class "Default")
      (node (ref "U1") (pin "23") (pinfunction "TMS/AN10/CVREF/PMA13/RPI42/RB10_23") (pintype "passive"))
    )
    (net (code "195") (name "unconnected-(U1-USBID{slash}RP99{slash}RF3-Pad33)") (class "Default")
      (node (ref "U1") (pin "33") (pinfunction "USBID/RP99/RF3_33") (pintype "passive"))
    )
    (net (code "196") (name "unconnected-(U6-NC-Pad4)") (class "Default")
      (node (ref "U6") (pin "4") (pinfunction "NC_4") (pintype "passive"))
    )
    (net (code "197") (name "unconnected-(U19-GND-Pad2)") (class "Default")
      (node (ref "U19") (pin "2") (pinfunction "GND_2") (pintype "passive"))
    )
    (net (code "198") (name "unconnected-(U19-GND-Pad3)") (class "Default")
      (node (ref "U19") (pin "3") (pinfunction "GND_3") (pintype "passive"))
    )
    (net (code "199") (name "unconnected-(U19-N.C.-Pad4)") (class "Default")
      (node (ref "U19") (pin "4") (pinfunction "N.C._4") (pintype "passive"))
    )
    (net (code "200") (name "unconnected-(U21-Vref-Pad5)") (class "Default")
      (node (ref "U21") (pin "5") (pinfunction "Vref_5") (pintype "passive"))
    )
  )
)
